# WiFi_Pi.net
KiCad netlist of a schematic drawn in EAGLE
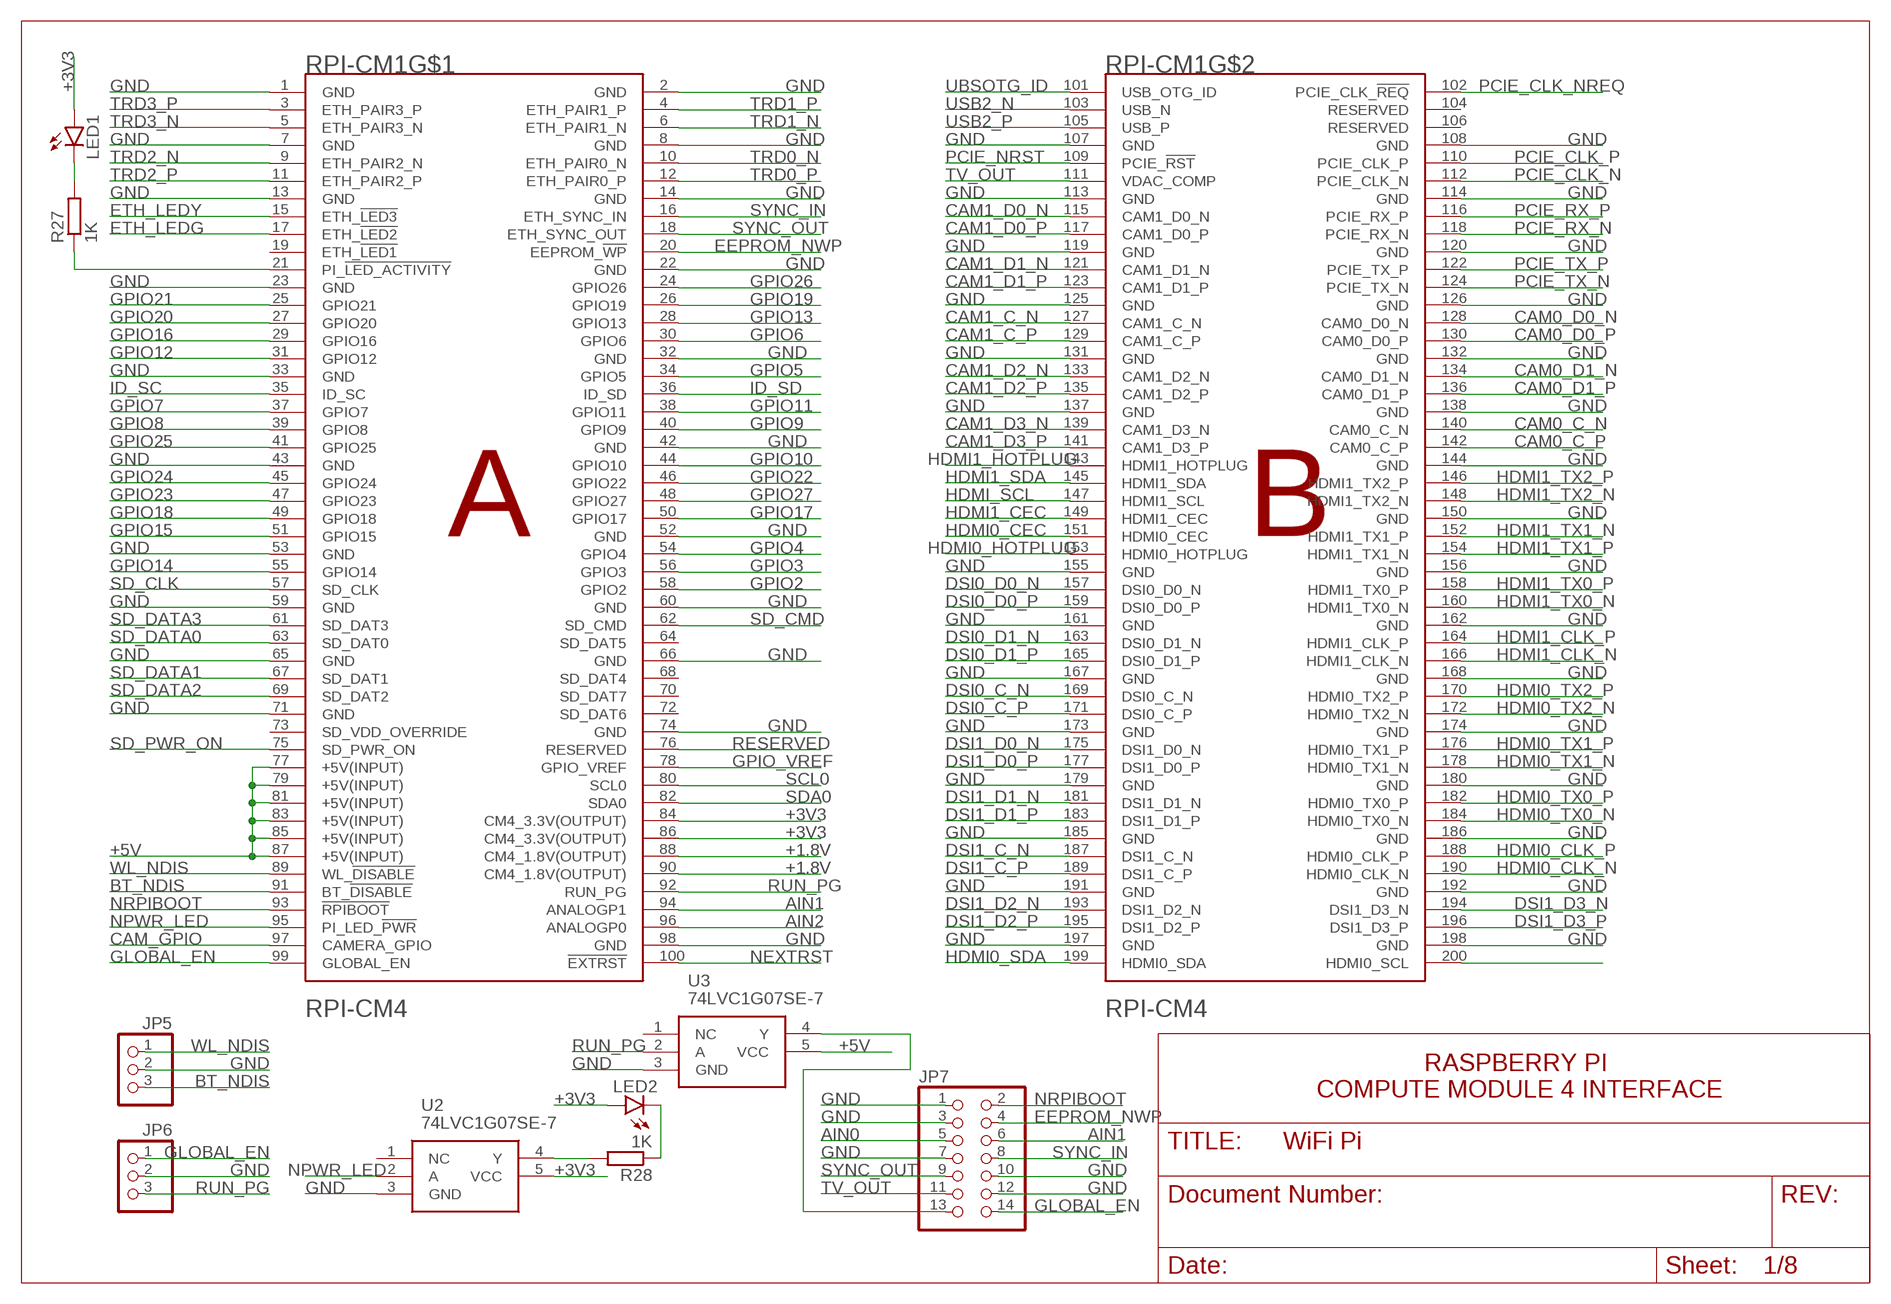
[diagram p0: schematic, sheet 1]
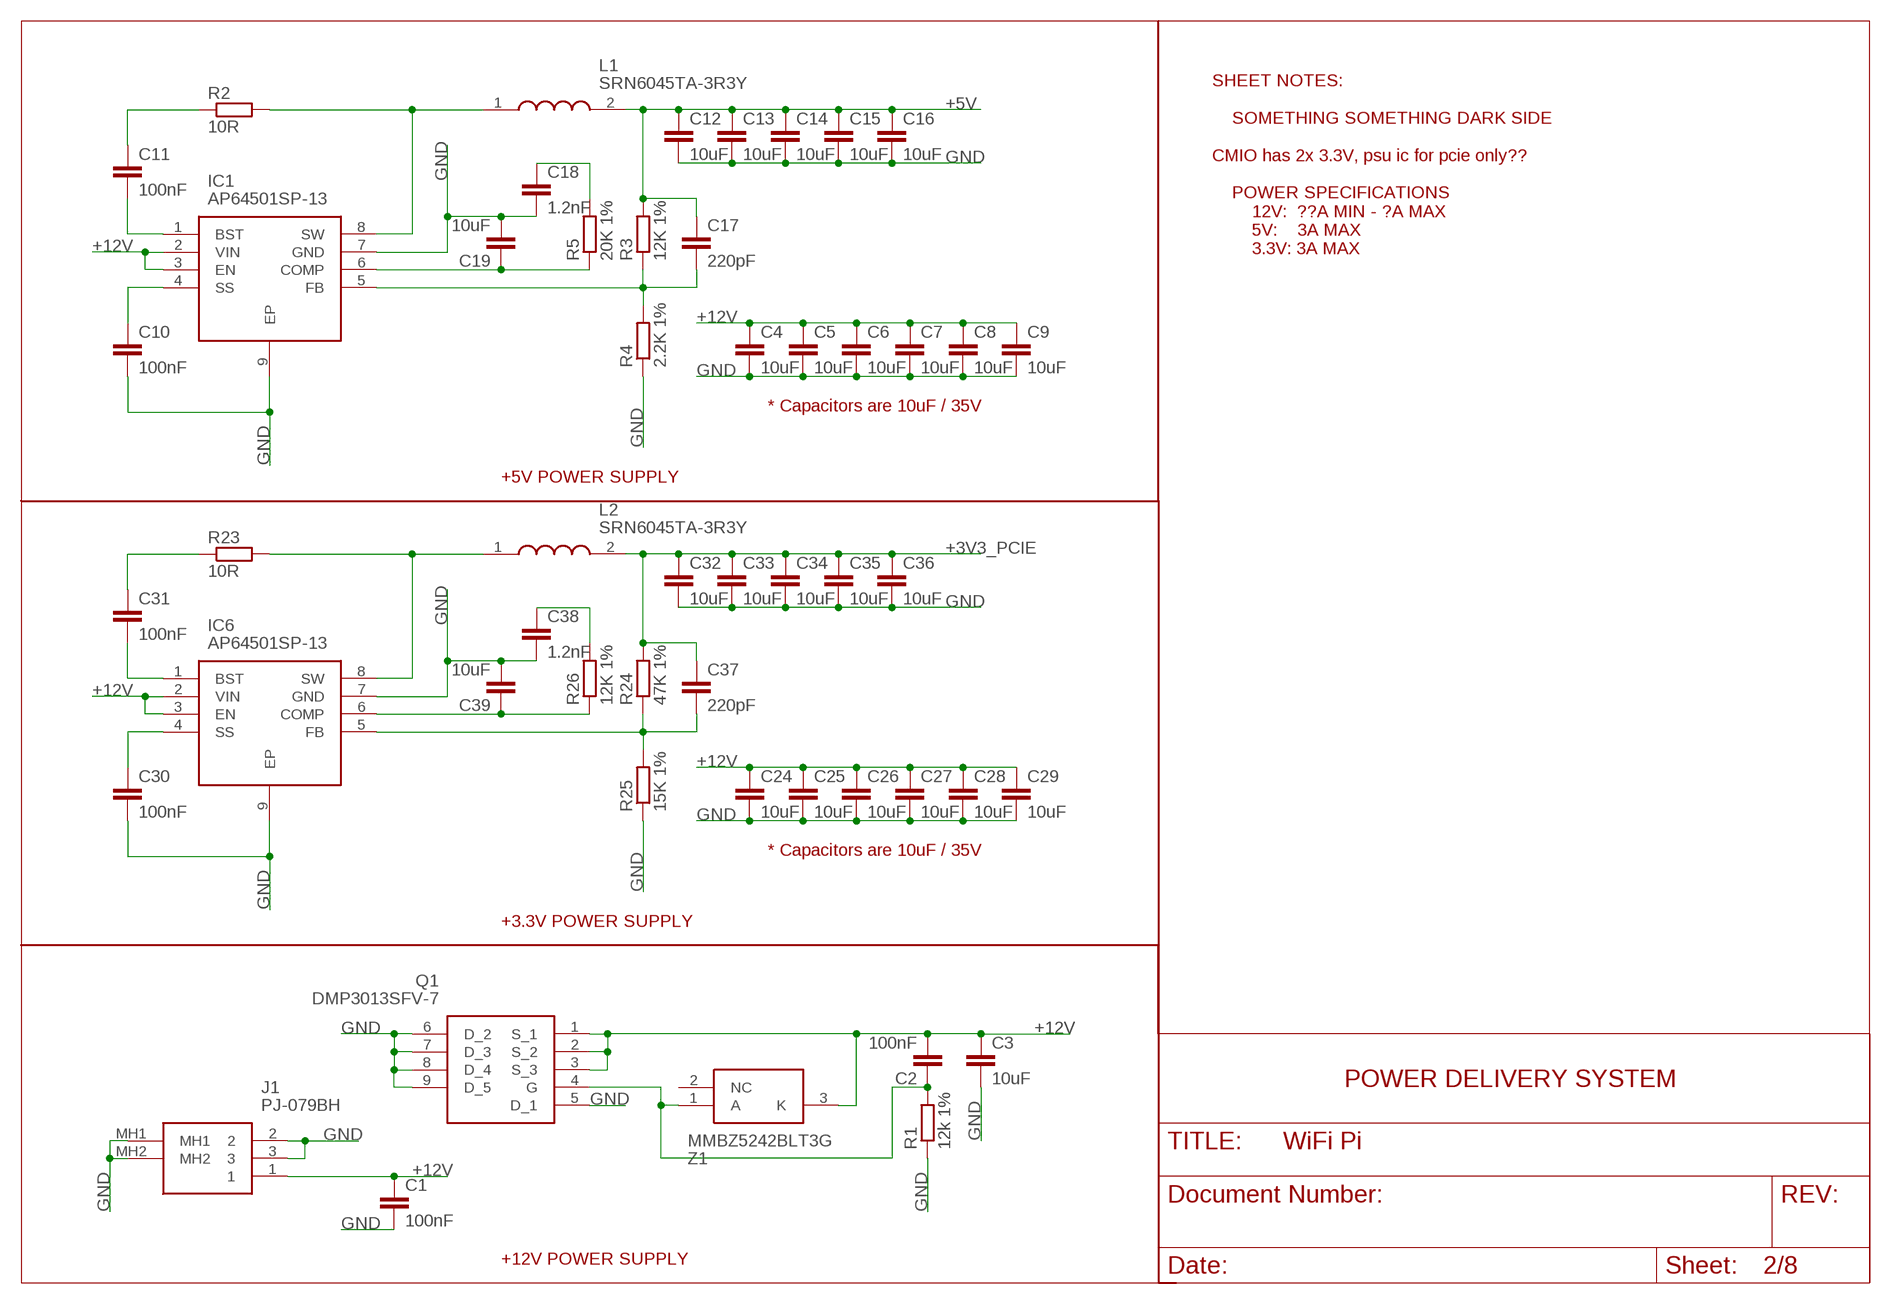
[diagram p1: schematic, sheet 2]
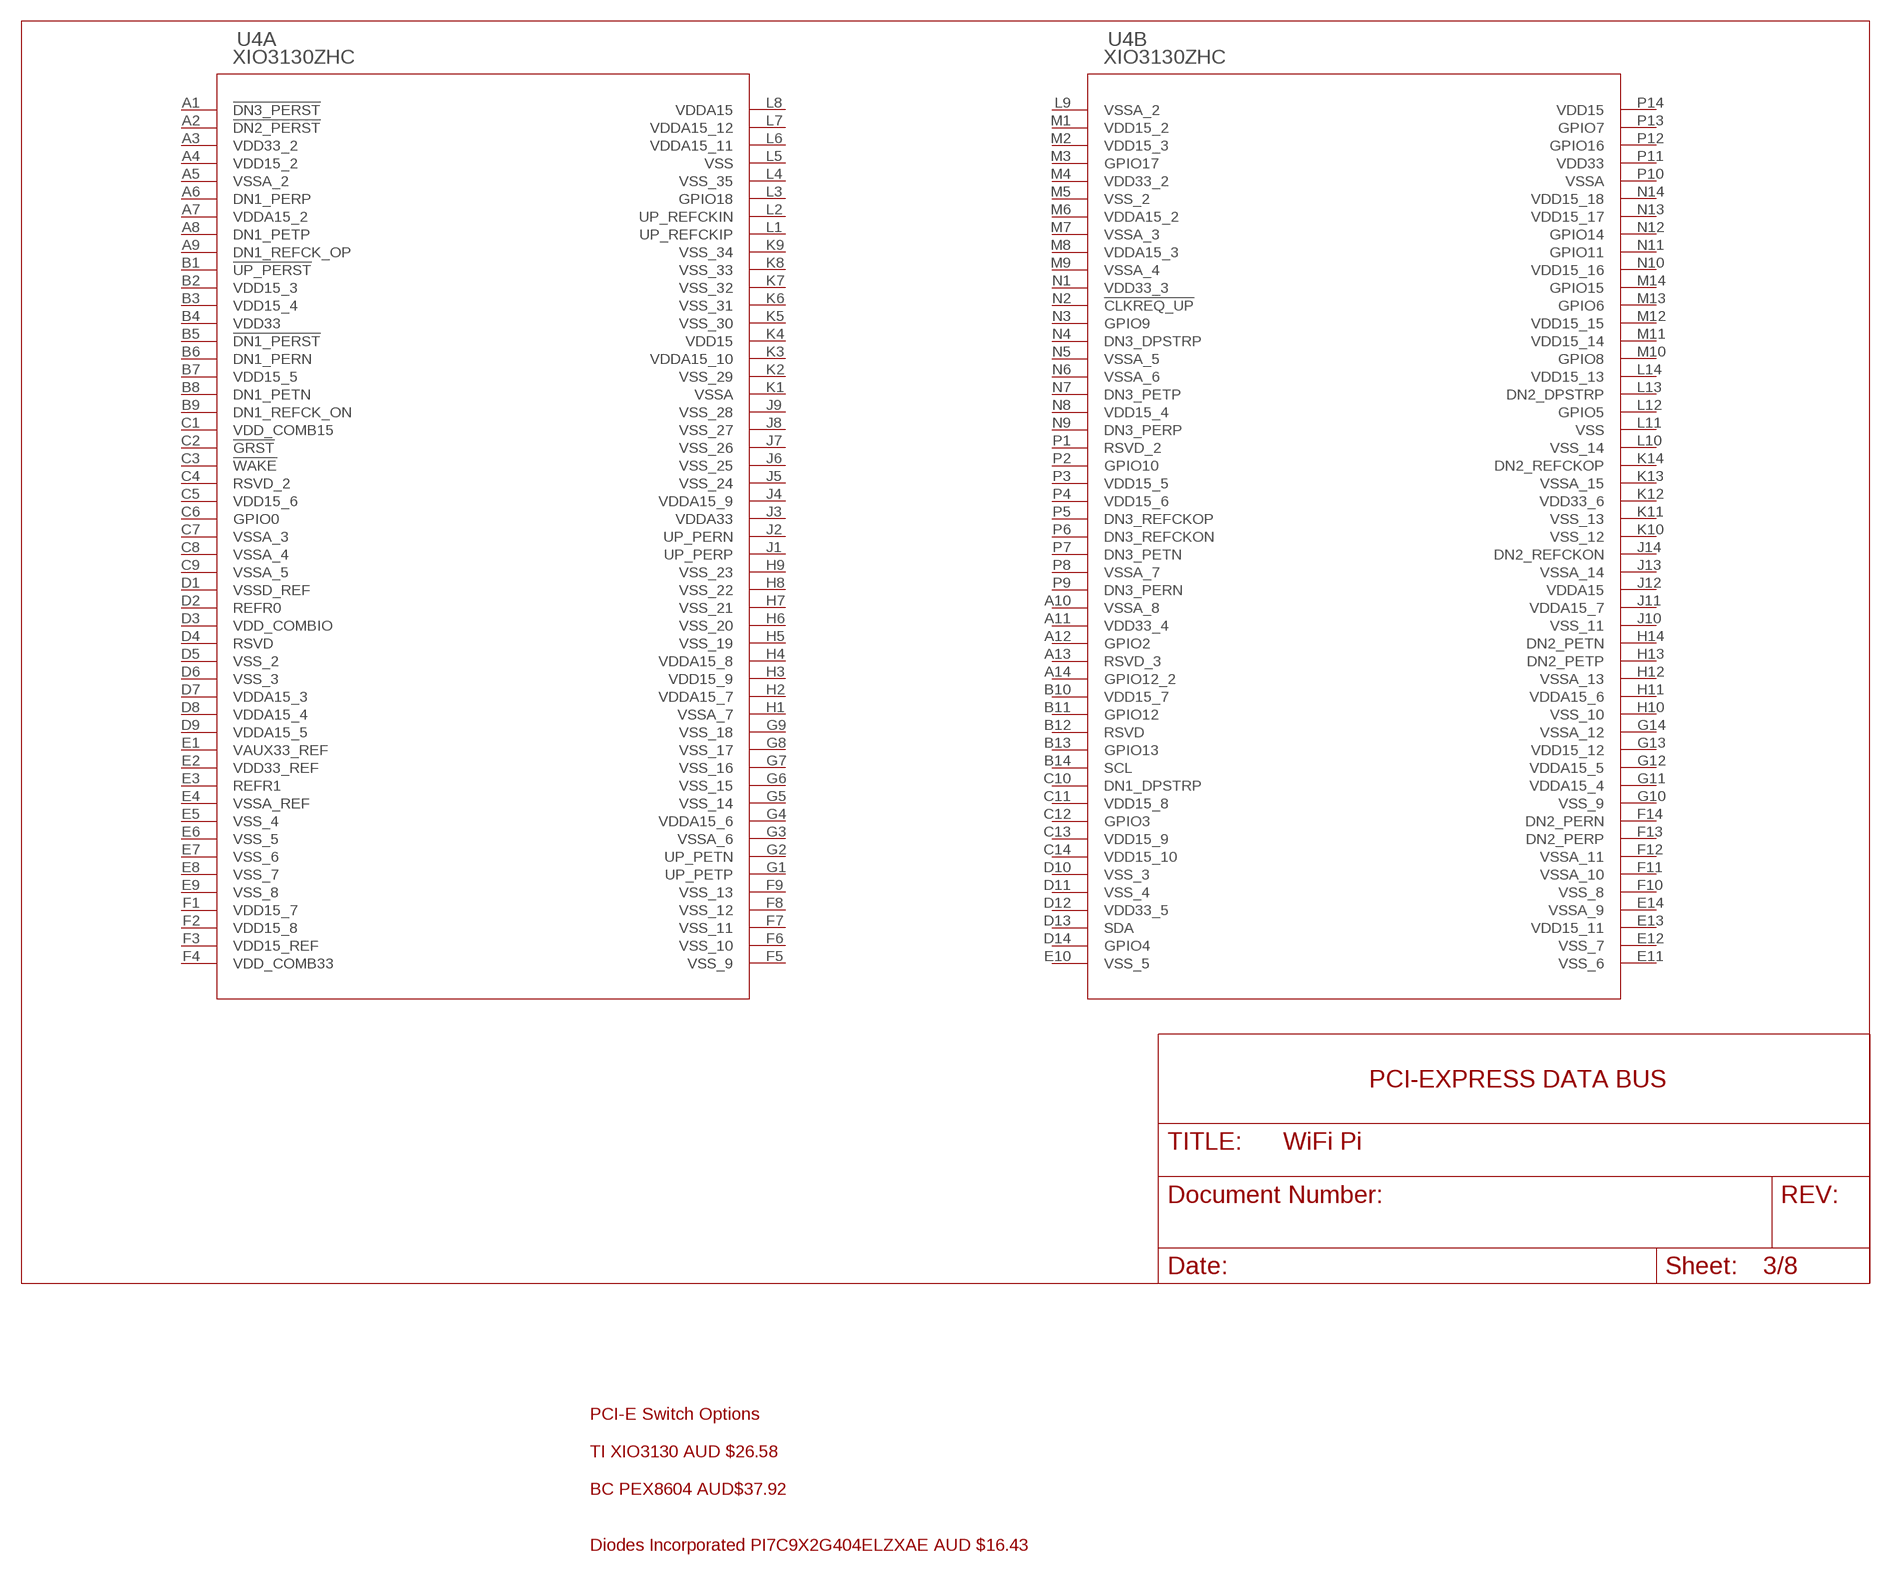
[diagram p2: schematic, sheet 3]
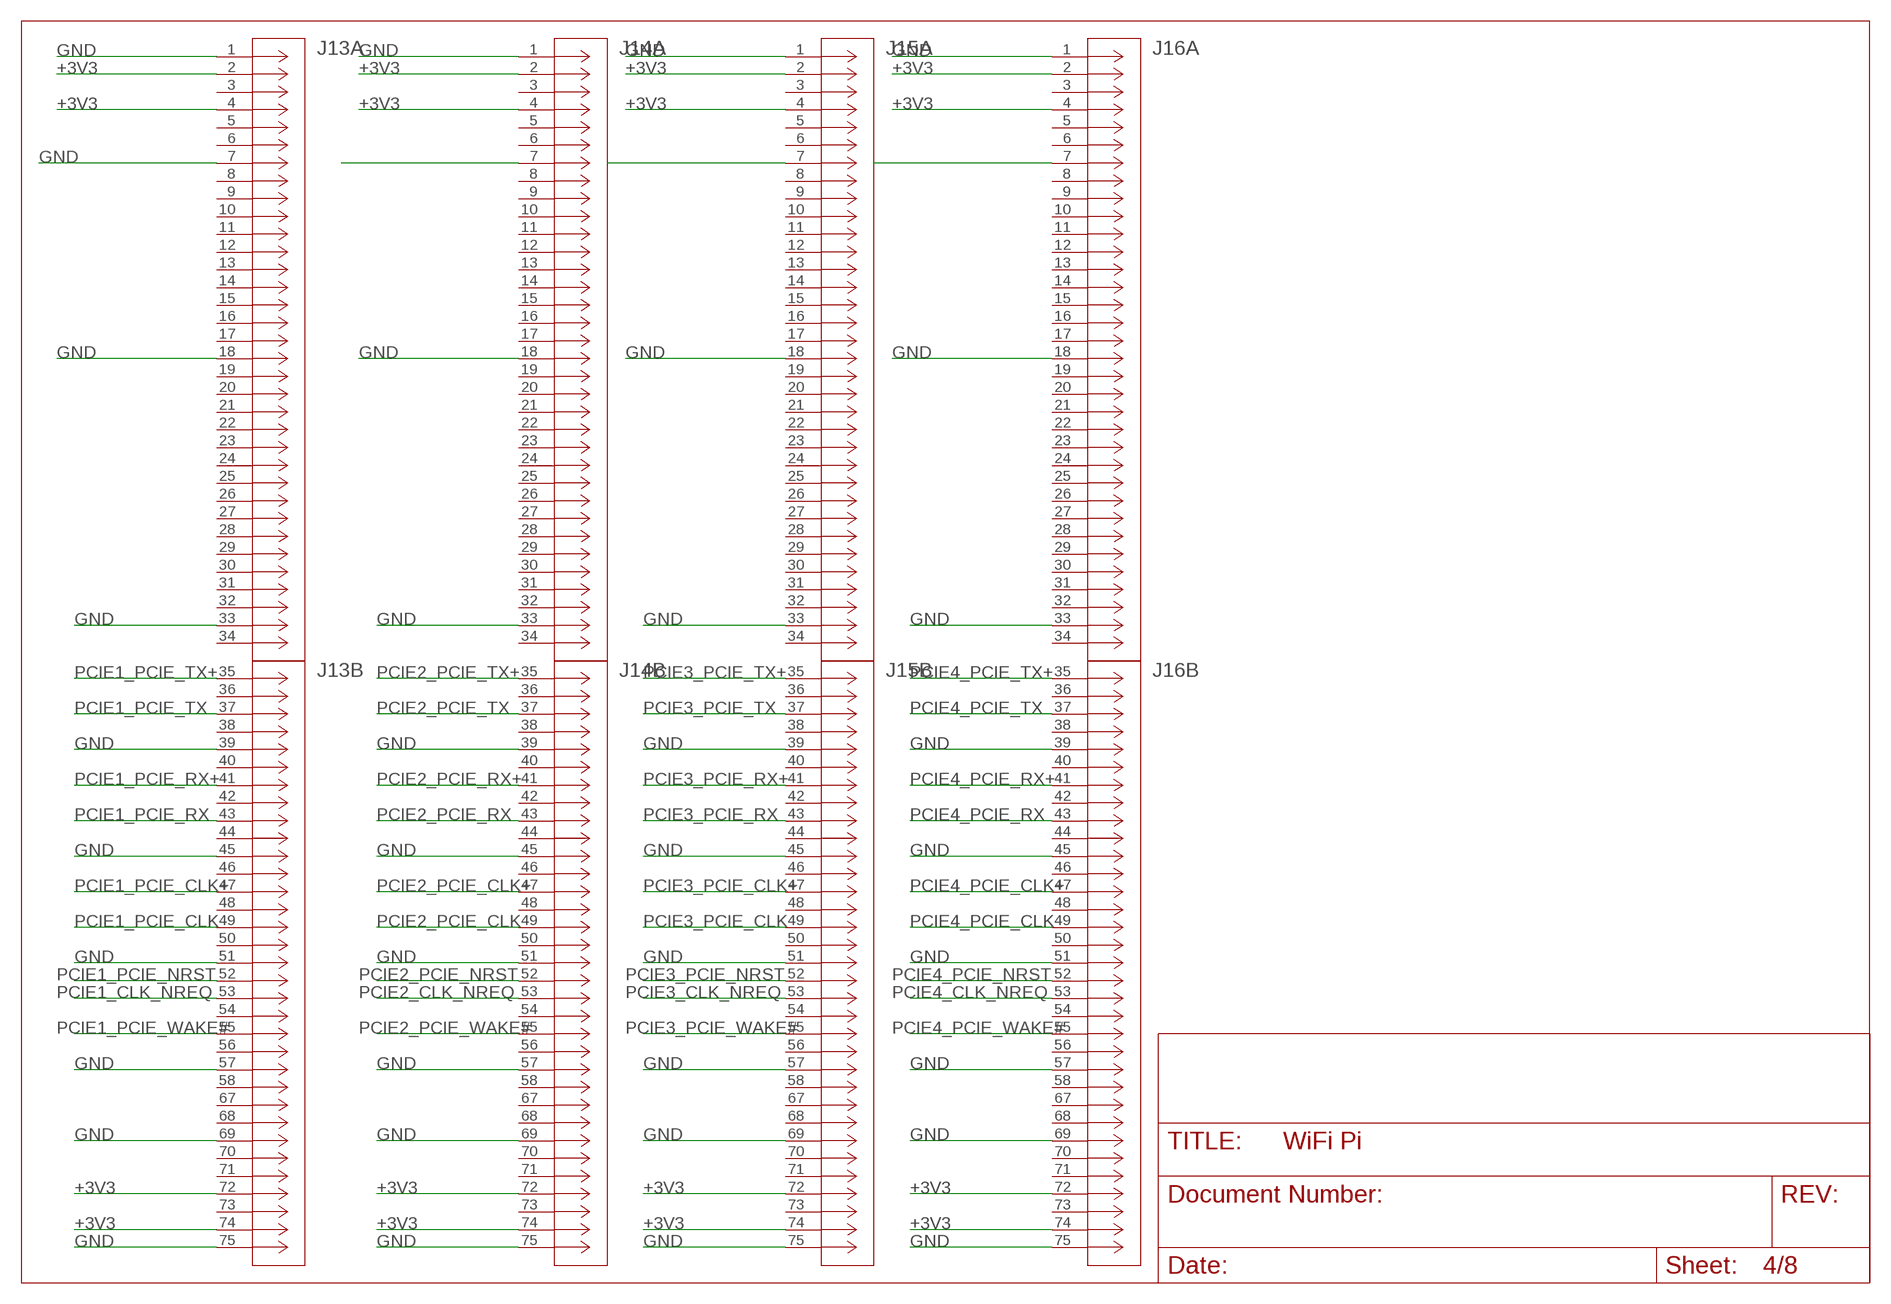
[diagram p3: schematic, sheet 4]
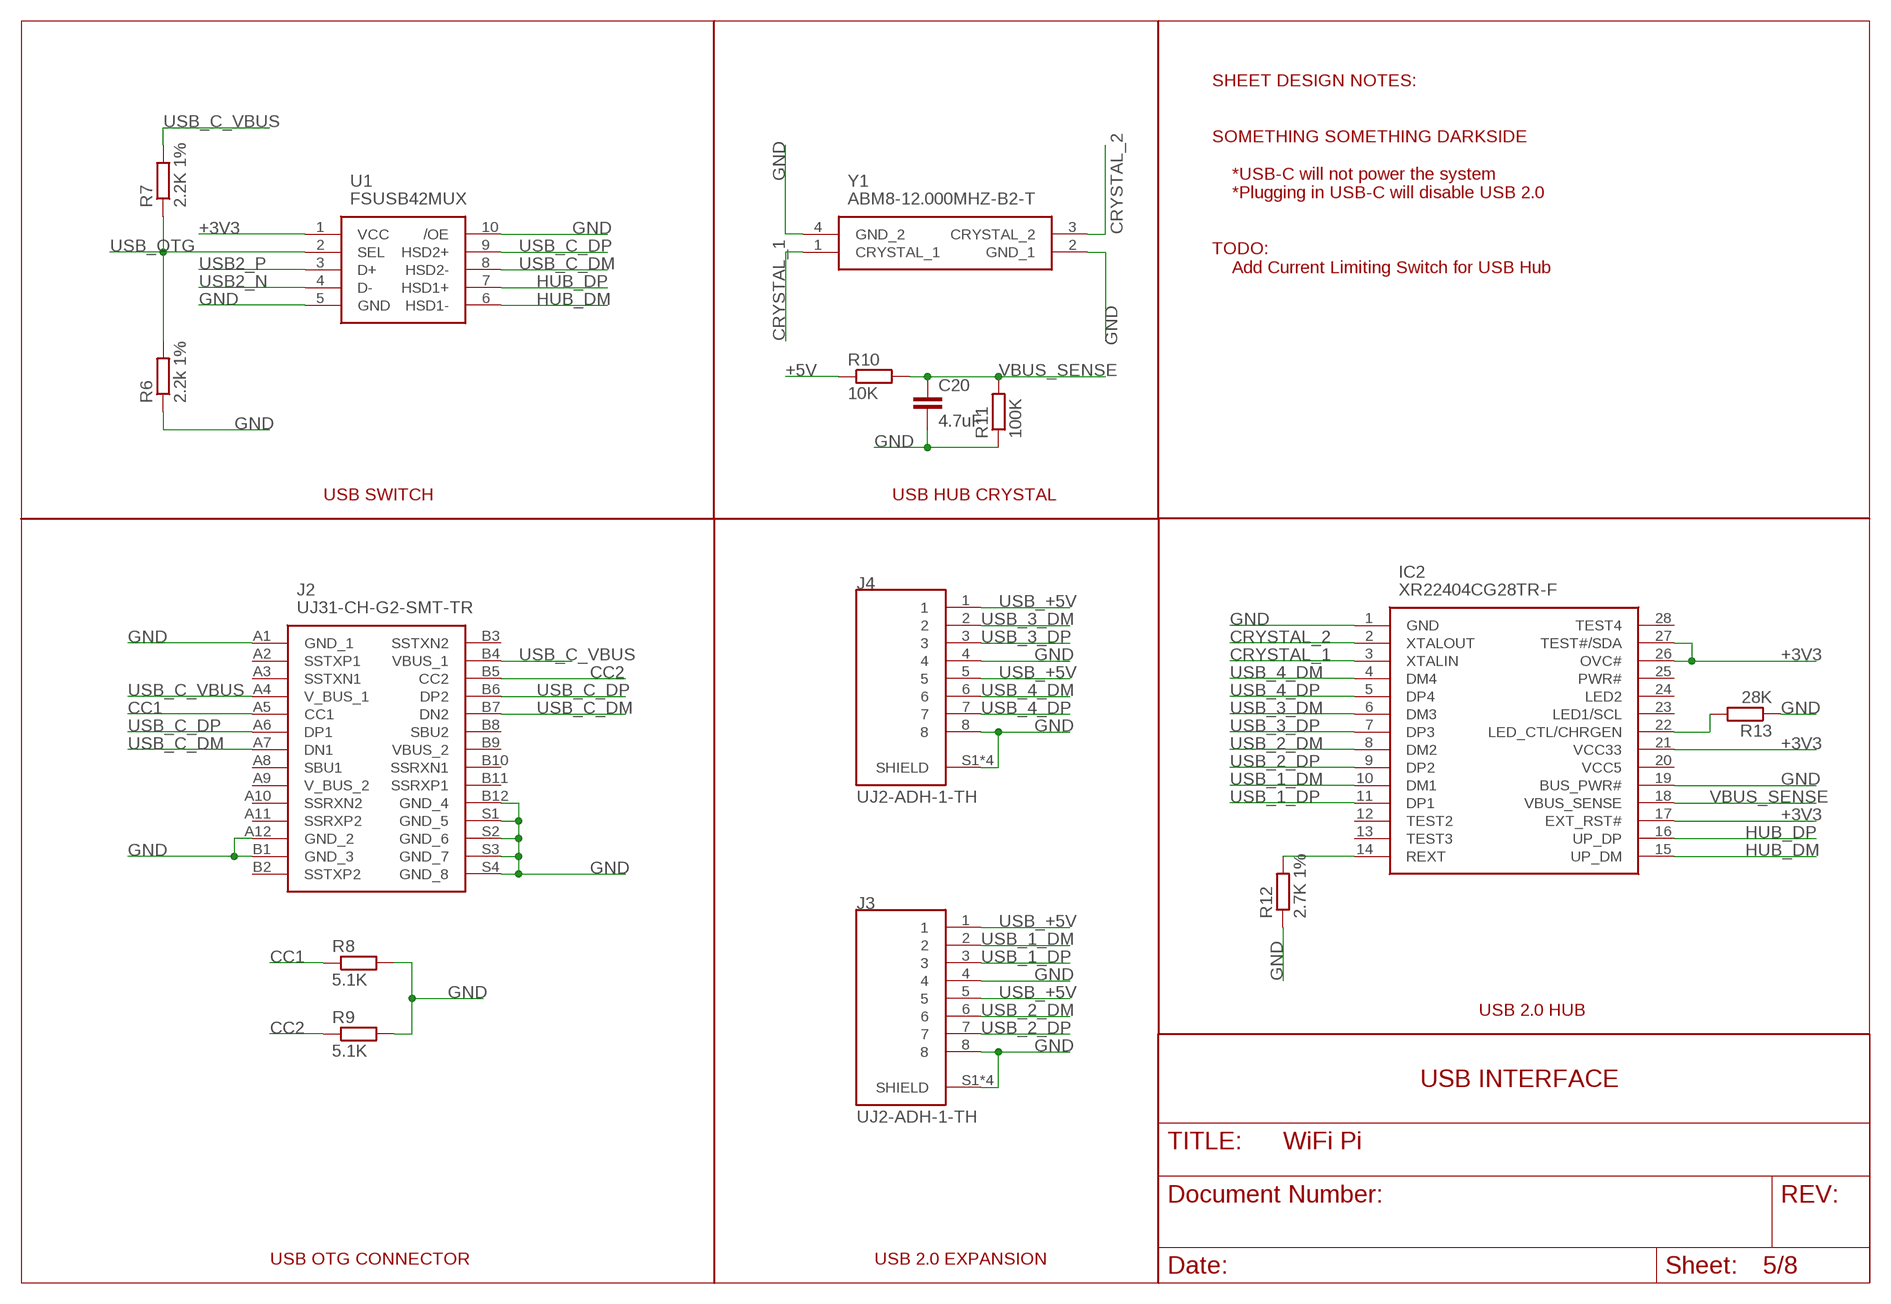
[diagram p4: schematic, sheet 5]
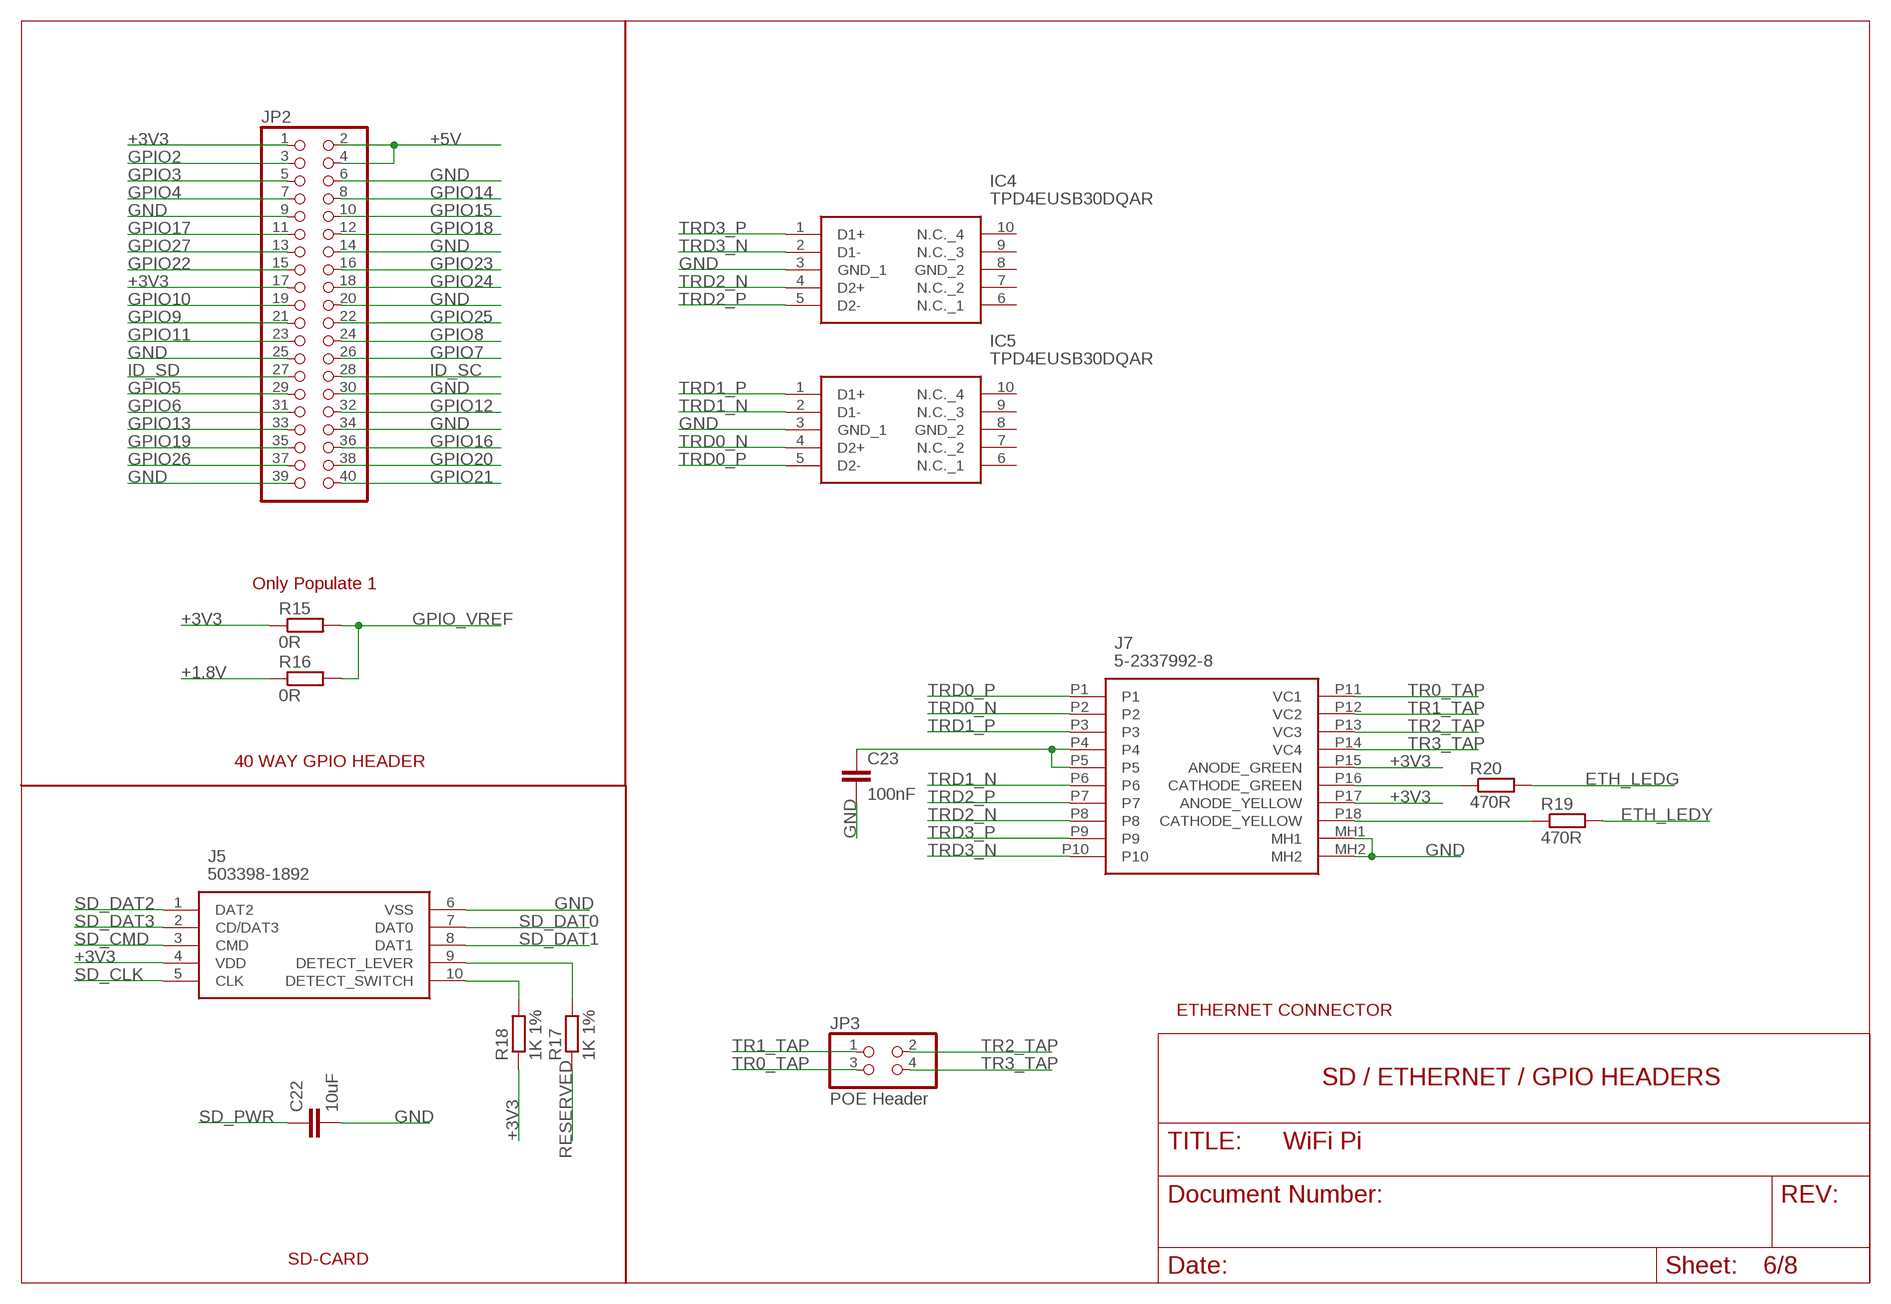
[diagram p5: schematic, sheet 6]
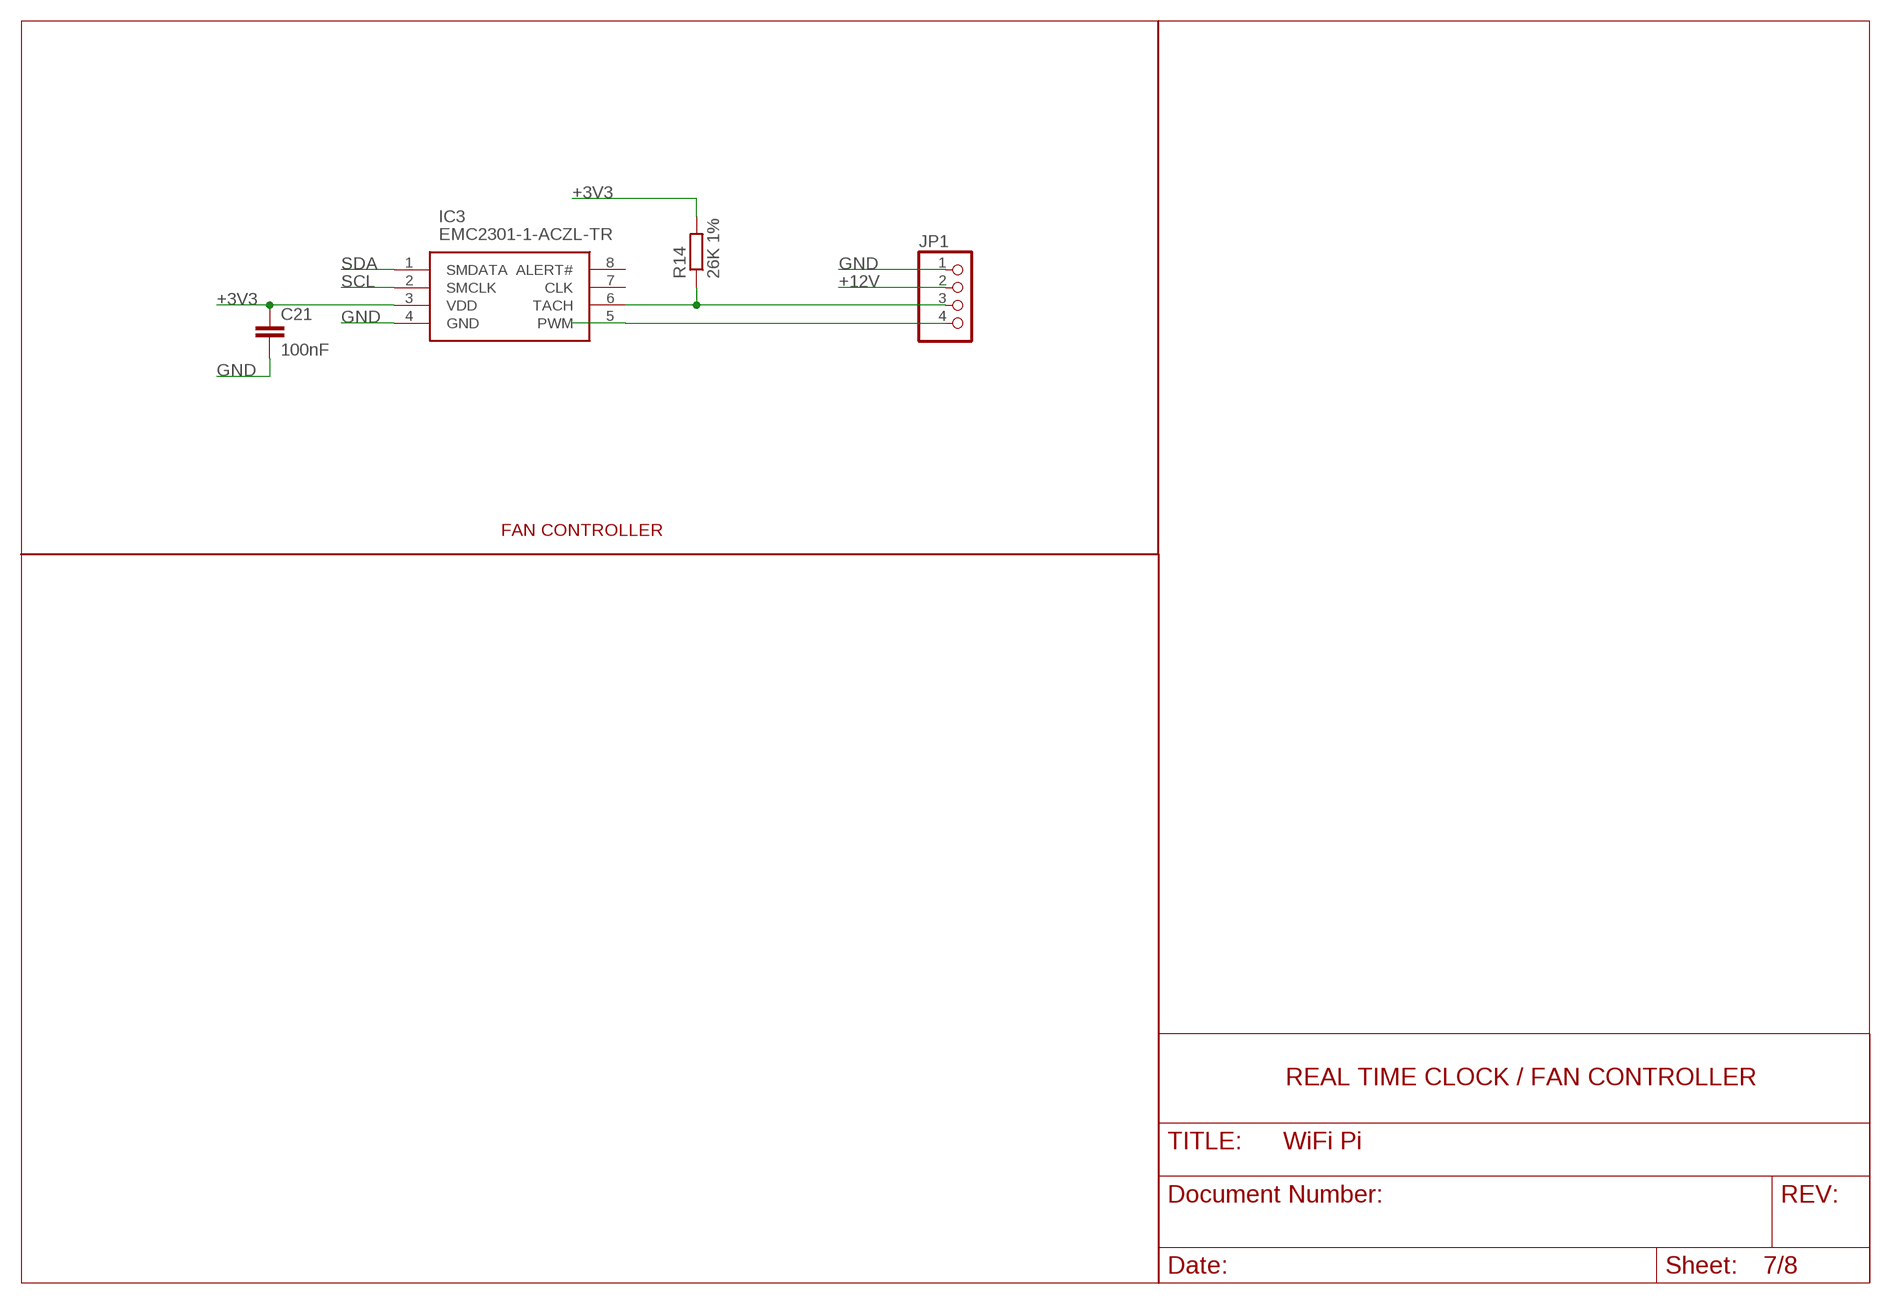
[diagram p6: schematic, sheet 7]
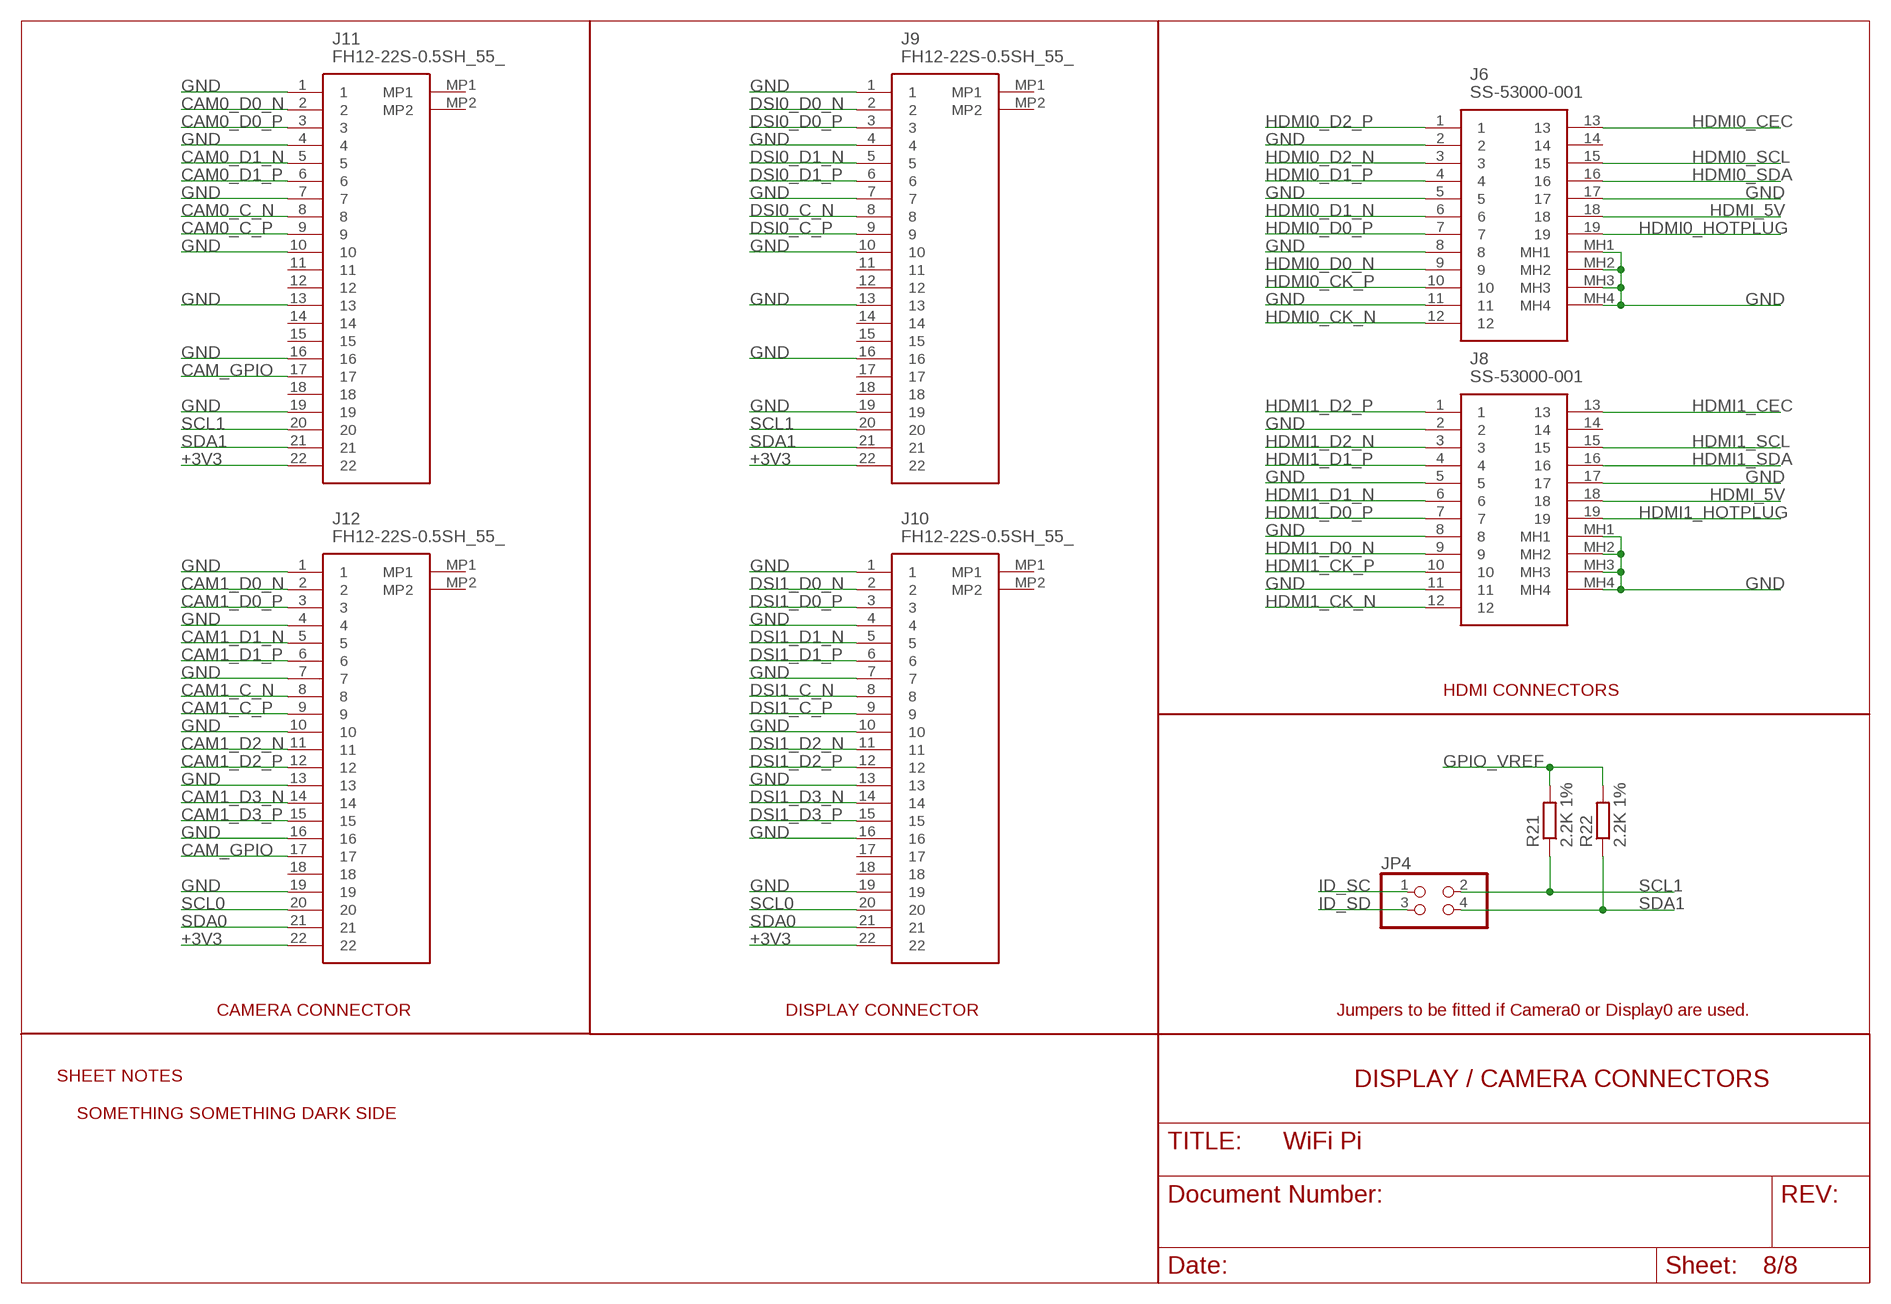
[diagram p7: schematic, sheet 8]

(export (version "E")
  (design (tool "Eeschema 10.0.6"))
  (components
    (comp (ref "JP5")
      (value "PINHD-1X3")
      (footprint "eagle-import:1X03")
      (libsource (lib "eagle-import") (part "PINHD-1X3"))
    )
    (comp (ref "JP6")
      (value "PINHD-1X3")
      (footprint "eagle-import:1X03")
      (libsource (lib "eagle-import") (part "PINHD-1X3"))
    )
    (comp (ref "JP7")
      (value "PINHD-2X7")
      (footprint "eagle-import:2X07")
      (libsource (lib "eagle-import") (part "PINHD-2X7"))
    )
    (comp (ref "LED1")
      (value "LEDCHIP-LED0805")
      (footprint "eagle-import:CHIP-LED0805")
      (libsource (lib "eagle-import") (part "LEDCHIP-LED0805"))
    )
    (comp (ref "LED2")
      (value "LEDCHIP-LED0805")
      (footprint "eagle-import:CHIP-LED0805")
      (libsource (lib "eagle-import") (part "LEDCHIP-LED0805"))
    )
    (comp (ref "R27")
      (value "1K")
      (footprint "eagle-import:M0805")
      (libsource (lib "eagle-import") (part "R-EU_M0805"))
    )
    (comp (ref "R28")
      (value "1K")
      (footprint "eagle-import:M0805")
      (libsource (lib "eagle-import") (part "R-EU_M0805"))
    )
    (comp (ref "RPI-CM1")
      (value "RPI-CM4")
      (footprint "eagle-import:RPI-CM4")
      (libsource (lib "eagle-import") (part "RPI-CM4"))
    )
    (comp (ref "U2")
      (value "74LVC1G07SE-7")
      (footprint "eagle-import:SOT65P210X110-5N")
      (fields (field (name "MOUSER_PART_NUMBER") "621-74LVC1G07SE-7"))
      (libsource (lib "eagle-import") (part "74LVC1G07SE-7"))
    )
    (comp (ref "U3")
      (value "74LVC1G07SE-7")
      (footprint "eagle-import:SOT65P210X110-5N")
      (fields (field (name "MOUSER_PART_NUMBER") "621-74LVC1G07SE-7"))
      (libsource (lib "eagle-import") (part "74LVC1G07SE-7"))
    )
    (comp (ref "C22")
      (value "10uF")
      (footprint "eagle-import:C0805K")
      (libsource (lib "eagle-import") (part "C-EUC0805K"))
    )
    (comp (ref "C23")
      (value "100nF")
      (footprint "eagle-import:C0805K")
      (libsource (lib "eagle-import") (part "C-EUC0805K"))
    )
    (comp (ref "IC4")
      (value "TPD4EUSB30DQAR")
      (footprint "eagle-import:DQA(R-PUSON-N10)")
      (fields (field (name "MOUSER_PART_NUMBER") "595-TPD4EUSB30DQAR"))
      (libsource (lib "eagle-import") (part "TPD4EUSB30DQAR"))
    )
    (comp (ref "IC5")
      (value "TPD4EUSB30DQAR")
      (footprint "eagle-import:DQA(R-PUSON-N10)")
      (fields (field (name "MOUSER_PART_NUMBER") "595-TPD4EUSB30DQAR"))
      (libsource (lib "eagle-import") (part "TPD4EUSB30DQAR"))
    )
    (comp (ref "J5")
      (value "503398-1892")
      (footprint "eagle-import:503398-1892")
      (fields (field (name "MOUSER_PART_NUMBER") "538-503398-1892"))
      (libsource (lib "eagle-import") (part "503398-1892"))
    )
    (comp (ref "J7")
      (value "5-2337992-8")
      (footprint "eagle-import:523379928")
      (fields (field (name "MOUSER_PART_NUMBER") "571-5-2337992-8"))
      (libsource (lib "eagle-import") (part "5-2337992-8"))
    )
    (comp (ref "JP2")
      (value "PINHD-2X20")
      (footprint "eagle-import:2X20")
      (libsource (lib "eagle-import") (part "PINHD-2X20"))
    )
    (comp (ref "JP3")
      (value "POE Header")
      (footprint "eagle-import:2X02")
      (libsource (lib "eagle-import") (part "PINHD-2X2"))
    )
    (comp (ref "R15")
      (value "0R")
      (footprint "eagle-import:M0805")
      (libsource (lib "eagle-import") (part "R-EU_M0805"))
    )
    (comp (ref "R16")
      (value "0R")
      (footprint "eagle-import:M0805")
      (libsource (lib "eagle-import") (part "R-EU_M0805"))
    )
    (comp (ref "R17")
      (value "1K 1%")
      (footprint "eagle-import:M0805")
      (libsource (lib "eagle-import") (part "R-EU_M0805"))
    )
    (comp (ref "R18")
      (value "1K 1%")
      (footprint "eagle-import:M0805")
      (libsource (lib "eagle-import") (part "R-EU_M0805"))
    )
    (comp (ref "R19")
      (value "470R")
      (footprint "eagle-import:M0805")
      (libsource (lib "eagle-import") (part "R-EU_M0805"))
    )
    (comp (ref "R20")
      (value "470R")
      (footprint "eagle-import:M0805")
      (libsource (lib "eagle-import") (part "R-EU_M0805"))
    )
    (comp (ref "C20")
      (value "4.7uF")
      (footprint "eagle-import:C0805K")
      (libsource (lib "eagle-import") (part "C-EUC0805K"))
    )
    (comp (ref "IC2")
      (value "XR22404CG28TR-F")
      (footprint "eagle-import:SOP64P600X173-28N")
      (fields (field (name "MOUSER_PART_NUMBER") "701-XR22404CG28TR-F"))
      (libsource (lib "eagle-import") (part "XR22404CG28TR-F"))
    )
    (comp (ref "J2")
      (value "UJ31-CH-G2-SMT-TR")
      (footprint "eagle-import:UJ31CHG2SMTTR")
      (fields (field (name "MOUSER_PART_NUMBER") "490-UJ31-CH-G2SMT-TR"))
      (libsource (lib "eagle-import") (part "UJ31-CH-G2-SMT-TR"))
    )
    (comp (ref "J3")
      (value "UJ2-ADH-1-TH")
      (footprint "eagle-import:CUI_UJ2-ADH-1-TH")
      (fields (field (name "MANUFACTURER") "CUI Devices"))
      (libsource (lib "eagle-import") (part "UJ2-ADH-1-TH"))
    )
    (comp (ref "J4")
      (value "UJ2-ADH-1-TH")
      (footprint "eagle-import:CUI_UJ2-ADH-1-TH")
      (fields (field (name "MANUFACTURER") "CUI Devices"))
      (libsource (lib "eagle-import") (part "UJ2-ADH-1-TH"))
    )
    (comp (ref "R6")
      (value "2.2k 1%")
      (footprint "eagle-import:M0805")
      (libsource (lib "eagle-import") (part "R-EU_M0805"))
    )
    (comp (ref "R7")
      (value "2.2K 1%")
      (footprint "eagle-import:M0805")
      (libsource (lib "eagle-import") (part "R-EU_M0805"))
    )
    (comp (ref "R8")
      (value "5.1K")
      (footprint "eagle-import:M0805")
      (libsource (lib "eagle-import") (part "R-EU_M0805"))
    )
    (comp (ref "R9")
      (value "5.1K")
      (footprint "eagle-import:M0805")
      (libsource (lib "eagle-import") (part "R-EU_M0805"))
    )
    (comp (ref "R10")
      (value "10K")
      (footprint "eagle-import:M0805")
      (libsource (lib "eagle-import") (part "R-EU_M0805"))
    )
    (comp (ref "R11")
      (value "100K")
      (footprint "eagle-import:M0805")
      (libsource (lib "eagle-import") (part "R-EU_M0805"))
    )
    (comp (ref "R12")
      (value "2.7K 1%")
      (footprint "eagle-import:M0805")
      (libsource (lib "eagle-import") (part "R-EU_M0805"))
    )
    (comp (ref "R13")
      (value "28K")
      (footprint "eagle-import:M0805")
      (libsource (lib "eagle-import") (part "R-EU_M0805"))
    )
    (comp (ref "U1")
      (value "FSUSB42MUX")
      (footprint "eagle-import:SOP50P490X110-10N")
      (fields (field (name "MOUSER_PART_NUMBER") "512-FSUSB42MUX"))
      (libsource (lib "eagle-import") (part "FSUSB42MUX"))
    )
    (comp (ref "Y1")
      (value "ABM8-12.000MHZ-B2-T")
      (footprint "eagle-import:ABM812000MHZB2T")
      (fields
        (field (name "MANUFACTURER_PART_NUMBER") "ABM8-12.000MHz-B2-T")
        (field (name "MOUSER_PART_NUMBER") "815-ABM8-12-B2-T")
      )
      (libsource (lib "eagle-import") (part "ABM8-12.000MHZ-B2-T"))
    )
    (comp (ref "U4")
      (value "XIO3130ZHC")
      (footprint "eagle-import:ZHC196")
      (fields
        (field (name "GENERIC_PART_NUMBER") "XIO3130")
        (field (name "MANUFACTURER") "Texas Instruments")
      )
      (libsource (lib "eagle-import") (part "XIO3130ZHC"))
    )
    (comp (ref "J6")
      (value "SS-53000-001")
      (footprint "eagle-import:SS53000001")
      (fields (field (name "MOUSER_PART_NUMBER") "530-SS-53000-001"))
      (libsource (lib "eagle-import") (part "SS-53000-001"))
    )
    (comp (ref "J8")
      (value "SS-53000-001")
      (footprint "eagle-import:SS53000001")
      (fields (field (name "MOUSER_PART_NUMBER") "530-SS-53000-001"))
      (libsource (lib "eagle-import") (part "SS-53000-001"))
    )
    (comp (ref "J9")
      (value "FH12-22S-0.5SH_55_")
      (footprint "eagle-import:FH1222S05SH55")
      (fields
        (field (name "MANUFACTURER_PART_NUMBER") "FH12-22S-0.5SH(55)")
        (field (name "MOUSER_PART_NUMBER") "798-FH12-22S-0.5SH55")
      )
      (libsource (lib "eagle-import") (part "FH12-22S-0.5SH_55_"))
    )
    (comp (ref "J10")
      (value "FH12-22S-0.5SH_55_")
      (footprint "eagle-import:FH1222S05SH55")
      (fields
        (field (name "MANUFACTURER_PART_NUMBER") "FH12-22S-0.5SH(55)")
        (field (name "MOUSER_PART_NUMBER") "798-FH12-22S-0.5SH55")
      )
      (libsource (lib "eagle-import") (part "FH12-22S-0.5SH_55_"))
    )
    (comp (ref "J11")
      (value "FH12-22S-0.5SH_55_")
      (footprint "eagle-import:FH1222S05SH55")
      (fields
        (field (name "MANUFACTURER_PART_NUMBER") "FH12-22S-0.5SH(55)")
        (field (name "MOUSER_PART_NUMBER") "798-FH12-22S-0.5SH55")
      )
      (libsource (lib "eagle-import") (part "FH12-22S-0.5SH_55_"))
    )
    (comp (ref "J12")
      (value "FH12-22S-0.5SH_55_")
      (footprint "eagle-import:FH1222S05SH55")
      (fields
        (field (name "MANUFACTURER_PART_NUMBER") "FH12-22S-0.5SH(55)")
        (field (name "MOUSER_PART_NUMBER") "798-FH12-22S-0.5SH55")
      )
      (libsource (lib "eagle-import") (part "FH12-22S-0.5SH_55_"))
    )
    (comp (ref "JP4")
      (value "PINHD-2X2")
      (footprint "eagle-import:2X02")
      (libsource (lib "eagle-import") (part "PINHD-2X2"))
    )
    (comp (ref "R21")
      (value "2.2K 1%")
      (footprint "eagle-import:M0805")
      (libsource (lib "eagle-import") (part "R-EU_M0805"))
    )
    (comp (ref "R22")
      (value "2.2K 1%")
      (footprint "eagle-import:M0805")
      (libsource (lib "eagle-import") (part "R-EU_M0805"))
    )
    (comp (ref "C1")
      (value "100nF")
      (footprint "eagle-import:C0805K")
      (libsource (lib "eagle-import") (part "C-EUC0805K"))
    )
    (comp (ref "C2")
      (value "100nF")
      (footprint "eagle-import:C0805K")
      (libsource (lib "eagle-import") (part "C-EUC0805K"))
    )
    (comp (ref "C3")
      (value "10uF")
      (footprint "eagle-import:C0805K")
      (libsource (lib "eagle-import") (part "C-EUC0805K"))
    )
    (comp (ref "C4")
      (value "10uF")
      (footprint "eagle-import:C0805K")
      (libsource (lib "eagle-import") (part "C-EUC0805K"))
    )
    (comp (ref "C5")
      (value "10uF")
      (footprint "eagle-import:C0805K")
      (libsource (lib "eagle-import") (part "C-EUC0805K"))
    )
    (comp (ref "C6")
      (value "10uF")
      (footprint "eagle-import:C0805K")
      (libsource (lib "eagle-import") (part "C-EUC0805K"))
    )
    (comp (ref "C7")
      (value "10uF")
      (footprint "eagle-import:C0805K")
      (libsource (lib "eagle-import") (part "C-EUC0805K"))
    )
    (comp (ref "C8")
      (value "10uF")
      (footprint "eagle-import:C0805K")
      (libsource (lib "eagle-import") (part "C-EUC0805K"))
    )
    (comp (ref "C9")
      (value "10uF")
      (footprint "eagle-import:C0805K")
      (libsource (lib "eagle-import") (part "C-EUC0805K"))
    )
    (comp (ref "C10")
      (value "100nF")
      (footprint "eagle-import:C0805K")
      (libsource (lib "eagle-import") (part "C-EUC0805K"))
    )
    (comp (ref "C11")
      (value "100nF")
      (footprint "eagle-import:C0805K")
      (libsource (lib "eagle-import") (part "C-EUC0805K"))
    )
    (comp (ref "C12")
      (value "10uF")
      (footprint "eagle-import:C0805K")
      (libsource (lib "eagle-import") (part "C-EUC0805K"))
    )
    (comp (ref "C13")
      (value "10uF")
      (footprint "eagle-import:C0805K")
      (libsource (lib "eagle-import") (part "C-EUC0805K"))
    )
    (comp (ref "C14")
      (value "10uF")
      (footprint "eagle-import:C0805K")
      (libsource (lib "eagle-import") (part "C-EUC0805K"))
    )
    (comp (ref "C15")
      (value "10uF")
      (footprint "eagle-import:C0805K")
      (libsource (lib "eagle-import") (part "C-EUC0805K"))
    )
    (comp (ref "C16")
      (value "10uF")
      (footprint "eagle-import:C0805K")
      (libsource (lib "eagle-import") (part "C-EUC0805K"))
    )
    (comp (ref "C17")
      (value "220pF")
      (footprint "eagle-import:C0805K")
      (libsource (lib "eagle-import") (part "C-EUC0805K"))
    )
    (comp (ref "C18")
      (value "1.2nF")
      (footprint "eagle-import:C0805K")
      (libsource (lib "eagle-import") (part "C-EUC0805K"))
    )
    (comp (ref "C19")
      (value "10uF")
      (footprint "eagle-import:C0805K")
      (libsource (lib "eagle-import") (part "C-EUC0805K"))
    )
    (comp (ref "C24")
      (value "10uF")
      (footprint "eagle-import:C0805K")
      (libsource (lib "eagle-import") (part "C-EUC0805K"))
    )
    (comp (ref "C25")
      (value "10uF")
      (footprint "eagle-import:C0805K")
      (libsource (lib "eagle-import") (part "C-EUC0805K"))
    )
    (comp (ref "C26")
      (value "10uF")
      (footprint "eagle-import:C0805K")
      (libsource (lib "eagle-import") (part "C-EUC0805K"))
    )
    (comp (ref "C27")
      (value "10uF")
      (footprint "eagle-import:C0805K")
      (libsource (lib "eagle-import") (part "C-EUC0805K"))
    )
    (comp (ref "C28")
      (value "10uF")
      (footprint "eagle-import:C0805K")
      (libsource (lib "eagle-import") (part "C-EUC0805K"))
    )
    (comp (ref "C29")
      (value "10uF")
      (footprint "eagle-import:C0805K")
      (libsource (lib "eagle-import") (part "C-EUC0805K"))
    )
    (comp (ref "C30")
      (value "100nF")
      (footprint "eagle-import:C0805K")
      (libsource (lib "eagle-import") (part "C-EUC0805K"))
    )
    (comp (ref "C31")
      (value "100nF")
      (footprint "eagle-import:C0805K")
      (libsource (lib "eagle-import") (part "C-EUC0805K"))
    )
    (comp (ref "C32")
      (value "10uF")
      (footprint "eagle-import:C0805K")
      (libsource (lib "eagle-import") (part "C-EUC0805K"))
    )
    (comp (ref "C33")
      (value "10uF")
      (footprint "eagle-import:C0805K")
      (libsource (lib "eagle-import") (part "C-EUC0805K"))
    )
    (comp (ref "C34")
      (value "10uF")
      (footprint "eagle-import:C0805K")
      (libsource (lib "eagle-import") (part "C-EUC0805K"))
    )
    (comp (ref "C35")
      (value "10uF")
      (footprint "eagle-import:C0805K")
      (libsource (lib "eagle-import") (part "C-EUC0805K"))
    )
    (comp (ref "C36")
      (value "10uF")
      (footprint "eagle-import:C0805K")
      (libsource (lib "eagle-import") (part "C-EUC0805K"))
    )
    (comp (ref "C37")
      (value "220pF")
      (footprint "eagle-import:C0805K")
      (libsource (lib "eagle-import") (part "C-EUC0805K"))
    )
    (comp (ref "C38")
      (value "1.2nF")
      (footprint "eagle-import:C0805K")
      (libsource (lib "eagle-import") (part "C-EUC0805K"))
    )
    (comp (ref "C39")
      (value "10uF")
      (footprint "eagle-import:C0805K")
      (libsource (lib "eagle-import") (part "C-EUC0805K"))
    )
    (comp (ref "IC1")
      (value "AP64501SP-13")
      (footprint "eagle-import:SOIC127P600X163-9N")
      (fields (field (name "MOUSER_PART_NUMBER") "621-AP64501SP-13"))
      (libsource (lib "eagle-import") (part "AP64501SP-13"))
    )
    (comp (ref "IC6")
      (value "AP64501SP-13")
      (footprint "eagle-import:SOIC127P600X163-9N")
      (fields (field (name "MOUSER_PART_NUMBER") "621-AP64501SP-13"))
      (libsource (lib "eagle-import") (part "AP64501SP-13"))
    )
    (comp (ref "J1")
      (value "PJ-079BH")
      (footprint "eagle-import:PJ079BH")
      (fields (field (name "MOUSER_PART_NUMBER") "490-PJ-079BH"))
      (libsource (lib "eagle-import") (part "PJ-079BH"))
    )
    (comp (ref "L1")
      (value "SRN6045TA-3R3Y")
      (footprint "eagle-import:SRN6045TA330M")
      (fields (field (name "MOUSER_PART_NUMBER") "652-SRN6045TA-3R3Y"))
      (libsource (lib "eagle-import") (part "SRN6045TA-3R3Y"))
    )
    (comp (ref "L2")
      (value "SRN6045TA-3R3Y")
      (footprint "eagle-import:SRN6045TA330M")
      (fields (field (name "MOUSER_PART_NUMBER") "652-SRN6045TA-3R3Y"))
      (libsource (lib "eagle-import") (part "SRN6045TA-3R3Y"))
    )
    (comp (ref "Q1")
      (value "DMP3013SFV-7")
      (footprint "eagle-import:DMP3013SFV7")
      (fields (field (name "MOUSER_PART_NUMBER") "621-DMP3013SFV-7"))
      (libsource (lib "eagle-import") (part "DMP3013SFV-7"))
    )
    (comp (ref "R1")
      (value "12k 1%")
      (footprint "eagle-import:M0805")
      (libsource (lib "eagle-import") (part "R-EU_M0805"))
    )
    (comp (ref "R2")
      (value "10R")
      (footprint "eagle-import:M0805")
      (libsource (lib "eagle-import") (part "R-EU_M0805"))
    )
    (comp (ref "R3")
      (value "12K 1%")
      (footprint "eagle-import:M0805")
      (libsource (lib "eagle-import") (part "R-EU_M0805"))
    )
    (comp (ref "R4")
      (value "2.2K 1%")
      (footprint "eagle-import:M0805")
      (libsource (lib "eagle-import") (part "R-EU_M0805"))
    )
    (comp (ref "R5")
      (value "20K 1%")
      (footprint "eagle-import:M0805")
      (libsource (lib "eagle-import") (part "R-EU_M0805"))
    )
    (comp (ref "R23")
      (value "10R")
      (footprint "eagle-import:M0805")
      (libsource (lib "eagle-import") (part "R-EU_M0805"))
    )
    (comp (ref "R24")
      (value "47K 1%")
      (footprint "eagle-import:M0805")
      (libsource (lib "eagle-import") (part "R-EU_M0805"))
    )
    (comp (ref "R25")
      (value "15K 1%")
      (footprint "eagle-import:M0805")
      (libsource (lib "eagle-import") (part "R-EU_M0805"))
    )
    (comp (ref "R26")
      (value "12K 1%")
      (footprint "eagle-import:M0805")
      (libsource (lib "eagle-import") (part "R-EU_M0805"))
    )
    (comp (ref "Z1")
      (value "MMBZ5242BLT3G")
      (footprint "eagle-import:SOT96P237X111-3N")
      (fields (field (name "MOUSER_PART_NUMBER") "863-MMBZ5242BLT3G"))
      (libsource (lib "eagle-import") (part "MMBZ5242BLT3G"))
    )
    (comp (ref "J13")
      (value "2199230-2")
      (footprint "eagle-import:CONN67_2199230_TEC")
      (fields (field (name "COPYRIGHT") "Copyright (C) 2018 Accelerated Designs. All rights reserved"))
      (libsource (lib "eagle-import") (part "2199230-2"))
    )
    (comp (ref "J14")
      (value "2199230-2")
      (footprint "eagle-import:CONN67_2199230_TEC")
      (fields (field (name "COPYRIGHT") "Copyright (C) 2018 Accelerated Designs. All rights reserved"))
      (libsource (lib "eagle-import") (part "2199230-2"))
    )
    (comp (ref "J15")
      (value "2199230-2")
      (footprint "eagle-import:CONN67_2199230_TEC")
      (fields (field (name "COPYRIGHT") "Copyright (C) 2018 Accelerated Designs. All rights reserved"))
      (libsource (lib "eagle-import") (part "2199230-2"))
    )
    (comp (ref "J16")
      (value "2199230-2")
      (footprint "eagle-import:CONN67_2199230_TEC")
      (fields (field (name "COPYRIGHT") "Copyright (C) 2018 Accelerated Designs. All rights reserved"))
      (libsource (lib "eagle-import") (part "2199230-2"))
    )
    (comp (ref "C21")
      (value "100nF")
      (footprint "eagle-import:C0805K")
      (libsource (lib "eagle-import") (part "C-EUC0805K"))
    )
    (comp (ref "IC3")
      (value "EMC2301-1-ACZL-TR")
      (footprint "eagle-import:SOP65P490X110-8N")
      (fields (field (name "MOUSER_PART_NUMBER") "886-EMC2301-1-ACZLTR"))
      (libsource (lib "eagle-import") (part "EMC2301-1-ACZL-TR"))
    )
    (comp (ref "JP1")
      (value "PINHD-1X4")
      (footprint "eagle-import:1X04")
      (libsource (lib "eagle-import") (part "PINHD-1X4"))
    )
    (comp (ref "R14")
      (value "26K 1%")
      (footprint "eagle-import:M0805")
      (libsource (lib "eagle-import") (part "R-EU_M0805"))
    )
  )
  (nets
    (net (code "1") (name "+1.8V") (class "Default")
      (node (ref "R16") (pin "1") (pinfunction "1_1") (pintype "passive"))
      (node (ref "RPI-CM1") (pin "88") (pinfunction "CM4_1.8V(OUTPUT)_88") (pintype "passive"))
      (node (ref "RPI-CM1") (pin "90") (pinfunction "CM4_1.8V(OUTPUT)_90") (pintype "passive"))
    )
    (net (code "2") (name "+3V3") (class "Default")
      (node (ref "C21") (pin "1") (pinfunction "1_1") (pintype "passive"))
      (node (ref "IC2") (pin "17") (pinfunction "EXT_RST#_17") (pintype "bidirectional"))
      (node (ref "IC2") (pin "21") (pinfunction "VCC33_21") (pintype "bidirectional"))
      (node (ref "IC2") (pin "26") (pinfunction "OVC#_26") (pintype "bidirectional"))
      (node (ref "IC2") (pin "27") (pinfunction "TEST#/SDA_27") (pintype "bidirectional"))
      (node (ref "IC3") (pin "3") (pinfunction "VDD_3") (pintype "bidirectional"))
      (node (ref "J10") (pin "22") (pinfunction "22_22") (pintype "bidirectional"))
      (node (ref "J11") (pin "22") (pinfunction "22_22") (pintype "bidirectional"))
      (node (ref "J12") (pin "22") (pinfunction "22_22") (pintype "bidirectional"))
      (node (ref "J13") (pin "2") (pinfunction "2_2") (pintype "passive"))
      (node (ref "J13") (pin "4") (pinfunction "4_4") (pintype "passive"))
      (node (ref "J13") (pin "72") (pinfunction "72_72") (pintype "passive"))
      (node (ref "J13") (pin "74") (pinfunction "74_74") (pintype "passive"))
      (node (ref "J14") (pin "2") (pinfunction "2_2") (pintype "passive"))
      (node (ref "J14") (pin "4") (pinfunction "4_4") (pintype "passive"))
      (node (ref "J14") (pin "72") (pinfunction "72_72") (pintype "passive"))
      (node (ref "J14") (pin "74") (pinfunction "74_74") (pintype "passive"))
      (node (ref "J15") (pin "2") (pinfunction "2_2") (pintype "passive"))
      (node (ref "J15") (pin "4") (pinfunction "4_4") (pintype "passive"))
      (node (ref "J15") (pin "72") (pinfunction "72_72") (pintype "passive"))
      (node (ref "J15") (pin "74") (pinfunction "74_74") (pintype "passive"))
      (node (ref "J16") (pin "2") (pinfunction "2_2") (pintype "passive"))
      (node (ref "J16") (pin "4") (pinfunction "4_4") (pintype "passive"))
      (node (ref "J16") (pin "72") (pinfunction "72_72") (pintype "passive"))
      (node (ref "J16") (pin "74") (pinfunction "74_74") (pintype "passive"))
      (node (ref "J5") (pin "4") (pinfunction "VDD_4") (pintype "bidirectional"))
      (node (ref "J7") (pin "P15") (pinfunction "ANODE_GREEN_P15") (pintype "bidirectional"))
      (node (ref "J7") (pin "P17") (pinfunction "ANODE_YELLOW_P17") (pintype "bidirectional"))
      (node (ref "J9") (pin "22") (pinfunction "22_22") (pintype "bidirectional"))
      (node (ref "JP2") (pin "1") (pinfunction "1_1") (pintype "passive"))
      (node (ref "JP2") (pin "17") (pinfunction "17_17") (pintype "passive"))
      (node (ref "LED1") (pin "A") (pinfunction "A_A") (pintype "passive"))
      (node (ref "LED2") (pin "A") (pinfunction "A_A") (pintype "passive"))
      (node (ref "R14") (pin "2") (pinfunction "2_2") (pintype "passive"))
      (node (ref "R15") (pin "1") (pinfunction "1_1") (pintype "passive"))
      (node (ref "R18") (pin "1") (pinfunction "1_1") (pintype "passive"))
      (node (ref "RPI-CM1") (pin "84") (pinfunction "CM4_3.3V(OUTPUT)_84") (pintype "passive"))
      (node (ref "RPI-CM1") (pin "86") (pinfunction "CM4_3.3V(OUTPUT)_86") (pintype "passive"))
      (node (ref "U1") (pin "1") (pinfunction "VCC_1") (pintype "bidirectional"))
      (node (ref "U2") (pin "5") (pinfunction "VCC_5") (pintype "bidirectional"))
    )
    (net (code "3") (name "+3V3_PCIE") (class "Default")
      (node (ref "C32") (pin "1") (pinfunction "1_1") (pintype "passive"))
      (node (ref "C33") (pin "1") (pinfunction "1_1") (pintype "passive"))
      (node (ref "C34") (pin "1") (pinfunction "1_1") (pintype "passive"))
      (node (ref "C35") (pin "1") (pinfunction "1_1") (pintype "passive"))
      (node (ref "C36") (pin "1") (pinfunction "1_1") (pintype "passive"))
      (node (ref "C37") (pin "1") (pinfunction "1_1") (pintype "passive"))
      (node (ref "L2") (pin "2") (pinfunction "2_2") (pintype "bidirectional"))
      (node (ref "R24") (pin "2") (pinfunction "2_2") (pintype "passive"))
    )
    (net (code "4") (name "+5V") (class "Default")
      (node (ref "C12") (pin "1") (pinfunction "1_1") (pintype "passive"))
      (node (ref "C13") (pin "1") (pinfunction "1_1") (pintype "passive"))
      (node (ref "C14") (pin "1") (pinfunction "1_1") (pintype "passive"))
      (node (ref "C15") (pin "1") (pinfunction "1_1") (pintype "passive"))
      (node (ref "C16") (pin "1") (pinfunction "1_1") (pintype "passive"))
      (node (ref "C17") (pin "1") (pinfunction "1_1") (pintype "passive"))
      (node (ref "JP2") (pin "2") (pinfunction "2_2") (pintype "passive"))
      (node (ref "JP2") (pin "4") (pinfunction "4_4") (pintype "passive"))
      (node (ref "L1") (pin "2") (pinfunction "2_2") (pintype "bidirectional"))
      (node (ref "R10") (pin "1") (pinfunction "1_1") (pintype "passive"))
      (node (ref "R3") (pin "2") (pinfunction "2_2") (pintype "passive"))
      (node (ref "RPI-CM1") (pin "77") (pinfunction "+5V(INPUT)_77") (pintype "passive"))
      (node (ref "RPI-CM1") (pin "79") (pinfunction "+5V(INPUT)_79") (pintype "passive"))
      (node (ref "RPI-CM1") (pin "81") (pinfunction "+5V(INPUT)_81") (pintype "passive"))
      (node (ref "RPI-CM1") (pin "83") (pinfunction "+5V(INPUT)_83") (pintype "passive"))
      (node (ref "RPI-CM1") (pin "85") (pinfunction "+5V(INPUT)_85") (pintype "passive"))
      (node (ref "RPI-CM1") (pin "87") (pinfunction "+5V(INPUT)_87") (pintype "passive"))
      (node (ref "U3") (pin "5") (pinfunction "VCC_5") (pintype "bidirectional"))
    )
    (net (code "5") (name "+12V") (class "Default")
      (node (ref "C1") (pin "1") (pinfunction "1_1") (pintype "passive"))
      (node (ref "C2") (pin "2") (pinfunction "2_2") (pintype "passive"))
      (node (ref "C24") (pin "1") (pinfunction "1_1") (pintype "passive"))
      (node (ref "C25") (pin "1") (pinfunction "1_1") (pintype "passive"))
      (node (ref "C26") (pin "1") (pinfunction "1_1") (pintype "passive"))
      (node (ref "C27") (pin "1") (pinfunction "1_1") (pintype "passive"))
      (node (ref "C28") (pin "1") (pinfunction "1_1") (pintype "passive"))
      (node (ref "C29") (pin "1") (pinfunction "1_1") (pintype "passive"))
      (node (ref "C3") (pin "1") (pinfunction "1_1") (pintype "passive"))
      (node (ref "C4") (pin "1") (pinfunction "1_1") (pintype "passive"))
      (node (ref "C5") (pin "1") (pinfunction "1_1") (pintype "passive"))
      (node (ref "C6") (pin "1") (pinfunction "1_1") (pintype "passive"))
      (node (ref "C7") (pin "1") (pinfunction "1_1") (pintype "passive"))
      (node (ref "C8") (pin "1") (pinfunction "1_1") (pintype "passive"))
      (node (ref "C9") (pin "1") (pinfunction "1_1") (pintype "passive"))
      (node (ref "IC1") (pin "2") (pinfunction "VIN_2") (pintype "bidirectional"))
      (node (ref "IC1") (pin "3") (pinfunction "EN_3") (pintype "bidirectional"))
      (node (ref "IC6") (pin "2") (pinfunction "VIN_2") (pintype "bidirectional"))
      (node (ref "IC6") (pin "3") (pinfunction "EN_3") (pintype "bidirectional"))
      (node (ref "J1") (pin "1") (pinfunction "1_1") (pintype "bidirectional"))
      (node (ref "JP1") (pin "2") (pinfunction "2_2") (pintype "passive"))
      (node (ref "Q1") (pin "1") (pinfunction "S_1_1") (pintype "bidirectional"))
      (node (ref "Q1") (pin "2") (pinfunction "S_2_2") (pintype "bidirectional"))
      (node (ref "Q1") (pin "3") (pinfunction "S_3_3") (pintype "bidirectional"))
      (node (ref "Z1") (pin "3") (pinfunction "K_3") (pintype "bidirectional"))
    )
    (net (code "6") (name "AIN0") (class "Default")
      (node (ref "JP7") (pin "5") (pinfunction "5_5") (pintype "passive"))
    )
    (net (code "7") (name "AIN1") (class "Default")
      (node (ref "JP7") (pin "6") (pinfunction "6_6") (pintype "passive"))
      (node (ref "RPI-CM1") (pin "94") (pinfunction "ANALOGP1_94") (pintype "passive"))
    )
    (net (code "8") (name "AIN2") (class "Default")
      (node (ref "RPI-CM1") (pin "96") (pinfunction "ANALOGP0_96") (pintype "passive"))
    )
    (net (code "9") (name "BT_NDIS") (class "Default")
      (node (ref "JP5") (pin "3") (pinfunction "3_3") (pintype "passive"))
      (node (ref "RPI-CM1") (pin "91") (pinfunction "BT_~{DISABLE}_91") (pintype "passive"))
    )
    (net (code "10") (name "CAM0_C_N") (class "Default")
      (node (ref "J11") (pin "8") (pinfunction "8_8") (pintype "bidirectional"))
      (node (ref "RPI-CM1") (pin "140") (pinfunction "CAM0_C_N_140") (pintype "passive"))
    )
    (net (code "11") (name "CAM0_C_P") (class "Default")
      (node (ref "J11") (pin "9") (pinfunction "9_9") (pintype "bidirectional"))
      (node (ref "RPI-CM1") (pin "142") (pinfunction "CAM0_C_P_142") (pintype "passive"))
    )
    (net (code "12") (name "CAM0_D0_N") (class "Default")
      (node (ref "J11") (pin "2") (pinfunction "2_2") (pintype "bidirectional"))
      (node (ref "RPI-CM1") (pin "128") (pinfunction "CAM0_D0_N_128") (pintype "passive"))
    )
    (net (code "13") (name "CAM0_D0_P") (class "Default")
      (node (ref "J11") (pin "3") (pinfunction "3_3") (pintype "bidirectional"))
      (node (ref "RPI-CM1") (pin "130") (pinfunction "CAM0_D0_P_130") (pintype "passive"))
    )
    (net (code "14") (name "CAM0_D1_N") (class "Default")
      (node (ref "J11") (pin "5") (pinfunction "5_5") (pintype "bidirectional"))
      (node (ref "RPI-CM1") (pin "134") (pinfunction "CAM0_D1_N_134") (pintype "passive"))
    )
    (net (code "15") (name "CAM0_D1_P") (class "Default")
      (node (ref "J11") (pin "6") (pinfunction "6_6") (pintype "bidirectional"))
      (node (ref "RPI-CM1") (pin "136") (pinfunction "CAM0_D1_P_136") (pintype "passive"))
    )
    (net (code "16") (name "CAM1_C_N") (class "Default")
      (node (ref "J12") (pin "8") (pinfunction "8_8") (pintype "bidirectional"))
      (node (ref "RPI-CM1") (pin "127") (pinfunction "CAM1_C_N_127") (pintype "passive"))
    )
    (net (code "17") (name "CAM1_C_P") (class "Default")
      (node (ref "J12") (pin "9") (pinfunction "9_9") (pintype "bidirectional"))
      (node (ref "RPI-CM1") (pin "129") (pinfunction "CAM1_C_P_129") (pintype "passive"))
    )
    (net (code "18") (name "CAM1_D0_N") (class "Default")
      (node (ref "J12") (pin "2") (pinfunction "2_2") (pintype "bidirectional"))
      (node (ref "RPI-CM1") (pin "115") (pinfunction "CAM1_D0_N_115") (pintype "passive"))
    )
    (net (code "19") (name "CAM1_D0_P") (class "Default")
      (node (ref "J12") (pin "3") (pinfunction "3_3") (pintype "bidirectional"))
      (node (ref "RPI-CM1") (pin "117") (pinfunction "CAM1_D0_P_117") (pintype "passive"))
    )
    (net (code "20") (name "CAM1_D1_N") (class "Default")
      (node (ref "J12") (pin "5") (pinfunction "5_5") (pintype "bidirectional"))
      (node (ref "RPI-CM1") (pin "121") (pinfunction "CAM1_D1_N_121") (pintype "passive"))
    )
    (net (code "21") (name "CAM1_D1_P") (class "Default")
      (node (ref "J12") (pin "6") (pinfunction "6_6") (pintype "bidirectional"))
      (node (ref "RPI-CM1") (pin "123") (pinfunction "CAM1_D1_P_123") (pintype "passive"))
    )
    (net (code "22") (name "CAM1_D2_N") (class "Default")
      (node (ref "J12") (pin "11") (pinfunction "11_11") (pintype "bidirectional"))
      (node (ref "RPI-CM1") (pin "133") (pinfunction "CAM1_D2_N_133") (pintype "passive"))
    )
    (net (code "23") (name "CAM1_D2_P") (class "Default")
      (node (ref "J12") (pin "12") (pinfunction "12_12") (pintype "bidirectional"))
      (node (ref "RPI-CM1") (pin "135") (pinfunction "CAM1_D2_P_135") (pintype "passive"))
    )
    (net (code "24") (name "CAM1_D3_N") (class "Default")
      (node (ref "J12") (pin "14") (pinfunction "14_14") (pintype "bidirectional"))
      (node (ref "RPI-CM1") (pin "139") (pinfunction "CAM1_D3_N_139") (pintype "passive"))
    )
    (net (code "25") (name "CAM1_D3_P") (class "Default")
      (node (ref "J12") (pin "15") (pinfunction "15_15") (pintype "bidirectional"))
      (node (ref "RPI-CM1") (pin "141") (pinfunction "CAM1_D3_P_141") (pintype "passive"))
    )
    (net (code "26") (name "CAM_GPIO") (class "Default")
      (node (ref "J11") (pin "17") (pinfunction "17_17") (pintype "bidirectional"))
      (node (ref "J12") (pin "17") (pinfunction "17_17") (pintype "bidirectional"))
      (node (ref "RPI-CM1") (pin "97") (pinfunction "CAMERA_GPIO_97") (pintype "passive"))
    )
    (net (code "27") (name "CC1") (class "Default")
      (node (ref "J2") (pin "A5") (pinfunction "CC1_A5") (pintype "bidirectional"))
      (node (ref "R8") (pin "1") (pinfunction "1_1") (pintype "passive"))
    )
    (net (code "28") (name "CC2") (class "Default")
      (node (ref "J2") (pin "B5") (pinfunction "CC2_B5") (pintype "bidirectional"))
      (node (ref "R9") (pin "1") (pinfunction "1_1") (pintype "passive"))
    )
    (net (code "29") (name "CRYSTAL_1") (class "Default")
      (node (ref "IC2") (pin "3") (pinfunction "XTALIN_3") (pintype "bidirectional"))
      (node (ref "Y1") (pin "1") (pinfunction "CRYSTAL_1_1") (pintype "bidirectional"))
    )
    (net (code "30") (name "CRYSTAL_2") (class "Default")
      (node (ref "IC2") (pin "2") (pinfunction "XTALOUT_2") (pintype "bidirectional"))
      (node (ref "Y1") (pin "3") (pinfunction "CRYSTAL_2_3") (pintype "bidirectional"))
    )
    (net (code "31") (name "DSI0_C_N") (class "Default")
      (node (ref "J9") (pin "8") (pinfunction "8_8") (pintype "bidirectional"))
      (node (ref "RPI-CM1") (pin "169") (pinfunction "DSI0_C_N_169") (pintype "passive"))
    )
    (net (code "32") (name "DSI0_C_P") (class "Default")
      (node (ref "J9") (pin "9") (pinfunction "9_9") (pintype "bidirectional"))
      (node (ref "RPI-CM1") (pin "171") (pinfunction "DSI0_C_P_171") (pintype "passive"))
    )
    (net (code "33") (name "DSI0_D0_N") (class "Default")
      (node (ref "J9") (pin "2") (pinfunction "2_2") (pintype "bidirectional"))
      (node (ref "RPI-CM1") (pin "157") (pinfunction "DSI0_D0_N_157") (pintype "passive"))
    )
    (net (code "34") (name "DSI0_D0_P") (class "Default")
      (node (ref "J9") (pin "3") (pinfunction "3_3") (pintype "bidirectional"))
      (node (ref "RPI-CM1") (pin "159") (pinfunction "DSI0_D0_P_159") (pintype "passive"))
    )
    (net (code "35") (name "DSI0_D1_N") (class "Default")
      (node (ref "J9") (pin "5") (pinfunction "5_5") (pintype "bidirectional"))
      (node (ref "RPI-CM1") (pin "163") (pinfunction "DSI0_D1_N_163") (pintype "passive"))
    )
    (net (code "36") (name "DSI0_D1_P") (class "Default")
      (node (ref "J9") (pin "6") (pinfunction "6_6") (pintype "bidirectional"))
      (node (ref "RPI-CM1") (pin "165") (pinfunction "DSI0_D1_P_165") (pintype "passive"))
    )
    (net (code "37") (name "DSI1_C_N") (class "Default")
      (node (ref "J10") (pin "8") (pinfunction "8_8") (pintype "bidirectional"))
      (node (ref "RPI-CM1") (pin "187") (pinfunction "DSI1_C_N_187") (pintype "passive"))
    )
    (net (code "38") (name "DSI1_C_P") (class "Default")
      (node (ref "J10") (pin "9") (pinfunction "9_9") (pintype "bidirectional"))
      (node (ref "RPI-CM1") (pin "189") (pinfunction "DSI1_C_P_189") (pintype "passive"))
    )
    (net (code "39") (name "DSI1_D0_N") (class "Default")
      (node (ref "J10") (pin "2") (pinfunction "2_2") (pintype "bidirectional"))
      (node (ref "RPI-CM1") (pin "175") (pinfunction "DSI1_D0_N_175") (pintype "passive"))
    )
    (net (code "40") (name "DSI1_D0_P") (class "Default")
      (node (ref "J10") (pin "3") (pinfunction "3_3") (pintype "bidirectional"))
      (node (ref "RPI-CM1") (pin "177") (pinfunction "DSI1_D0_P_177") (pintype "passive"))
    )
    (net (code "41") (name "DSI1_D1_N") (class "Default")
      (node (ref "J10") (pin "5") (pinfunction "5_5") (pintype "bidirectional"))
      (node (ref "RPI-CM1") (pin "181") (pinfunction "DSI1_D1_N_181") (pintype "passive"))
    )
    (net (code "42") (name "DSI1_D1_P") (class "Default")
      (node (ref "J10") (pin "6") (pinfunction "6_6") (pintype "bidirectional"))
      (node (ref "RPI-CM1") (pin "183") (pinfunction "DSI1_D1_P_183") (pintype "passive"))
    )
    (net (code "43") (name "DSI1_D2_N") (class "Default")
      (node (ref "J10") (pin "11") (pinfunction "11_11") (pintype "bidirectional"))
      (node (ref "RPI-CM1") (pin "193") (pinfunction "DSI1_D2_N_193") (pintype "passive"))
    )
    (net (code "44") (name "DSI1_D2_P") (class "Default")
      (node (ref "J10") (pin "12") (pinfunction "12_12") (pintype "bidirectional"))
      (node (ref "RPI-CM1") (pin "195") (pinfunction "DSI1_D2_P_195") (pintype "passive"))
    )
    (net (code "45") (name "DSI1_D3_N") (class "Default")
      (node (ref "J10") (pin "14") (pinfunction "14_14") (pintype "bidirectional"))
      (node (ref "RPI-CM1") (pin "194") (pinfunction "DSI1_D3_N_194") (pintype "passive"))
    )
    (net (code "46") (name "DSI1_D3_P") (class "Default")
      (node (ref "J10") (pin "15") (pinfunction "15_15") (pintype "bidirectional"))
      (node (ref "RPI-CM1") (pin "196") (pinfunction "DSI1_D3_P_196") (pintype "passive"))
    )
    (net (code "47") (name "EEPROM_NWP") (class "Default")
      (node (ref "JP7") (pin "4") (pinfunction "4_4") (pintype "passive"))
      (node (ref "RPI-CM1") (pin "20") (pinfunction "EEPROM_~{WP}_20") (pintype "passive"))
    )
    (net (code "48") (name "ETH_LEDG") (class "Default")
      (node (ref "R20") (pin "2") (pinfunction "2_2") (pintype "passive"))
      (node (ref "RPI-CM1") (pin "17") (pinfunction "ETH_~{LED2}_17") (pintype "passive"))
    )
    (net (code "49") (name "ETH_LEDY") (class "Default")
      (node (ref "R19") (pin "2") (pinfunction "2_2") (pintype "passive"))
      (node (ref "RPI-CM1") (pin "15") (pinfunction "ETH_~{LED3}_15") (pintype "passive"))
    )
    (net (code "50") (name "GLOBAL_EN") (class "Default")
      (node (ref "JP6") (pin "1") (pinfunction "1_1") (pintype "passive"))
      (node (ref "JP7") (pin "14") (pinfunction "14_14") (pintype "passive"))
      (node (ref "RPI-CM1") (pin "99") (pinfunction "GLOBAL_EN_99") (pintype "passive"))
    )
    (net (code "51") (name "GND") (class "Default")
      (node (ref "C1") (pin "2") (pinfunction "2_2") (pintype "passive"))
      (node (ref "C10") (pin "2") (pinfunction "2_2") (pintype "passive"))
      (node (ref "C12") (pin "2") (pinfunction "2_2") (pintype "passive"))
      (node (ref "C13") (pin "2") (pinfunction "2_2") (pintype "passive"))
      (node (ref "C14") (pin "2") (pinfunction "2_2") (pintype "passive"))
      (node (ref "C15") (pin "2") (pinfunction "2_2") (pintype "passive"))
      (node (ref "C16") (pin "2") (pinfunction "2_2") (pintype "passive"))
      (node (ref "C18") (pin "2") (pinfunction "2_2") (pintype "passive"))
      (node (ref "C19") (pin "2") (pinfunction "2_2") (pintype "passive"))
      (node (ref "C20") (pin "2") (pinfunction "2_2") (pintype "passive"))
      (node (ref "C21") (pin "2") (pinfunction "2_2") (pintype "passive"))
      (node (ref "C22") (pin "2") (pinfunction "2_2") (pintype "passive"))
      (node (ref "C23") (pin "2") (pinfunction "2_2") (pintype "passive"))
      (node (ref "C24") (pin "2") (pinfunction "2_2") (pintype "passive"))
      (node (ref "C25") (pin "2") (pinfunction "2_2") (pintype "passive"))
      (node (ref "C26") (pin "2") (pinfunction "2_2") (pintype "passive"))
      (node (ref "C27") (pin "2") (pinfunction "2_2") (pintype "passive"))
      (node (ref "C28") (pin "2") (pinfunction "2_2") (pintype "passive"))
      (node (ref "C29") (pin "2") (pinfunction "2_2") (pintype "passive"))
      (node (ref "C3") (pin "2") (pinfunction "2_2") (pintype "passive"))
      (node (ref "C30") (pin "2") (pinfunction "2_2") (pintype "passive"))
      (node (ref "C32") (pin "2") (pinfunction "2_2") (pintype "passive"))
      (node (ref "C33") (pin "2") (pinfunction "2_2") (pintype "passive"))
      (node (ref "C34") (pin "2") (pinfunction "2_2") (pintype "passive"))
      (node (ref "C35") (pin "2") (pinfunction "2_2") (pintype "passive"))
      (node (ref "C36") (pin "2") (pinfunction "2_2") (pintype "passive"))
      (node (ref "C38") (pin "2") (pinfunction "2_2") (pintype "passive"))
      (node (ref "C39") (pin "2") (pinfunction "2_2") (pintype "passive"))
      (node (ref "C4") (pin "2") (pinfunction "2_2") (pintype "passive"))
      (node (ref "C5") (pin "2") (pinfunction "2_2") (pintype "passive"))
      (node (ref "C6") (pin "2") (pinfunction "2_2") (pintype "passive"))
      (node (ref "C7") (pin "2") (pinfunction "2_2") (pintype "passive"))
      (node (ref "C8") (pin "2") (pinfunction "2_2") (pintype "passive"))
      (node (ref "C9") (pin "2") (pinfunction "2_2") (pintype "passive"))
      (node (ref "IC1") (pin "7") (pinfunction "GND_7") (pintype "bidirectional"))
      (node (ref "IC1") (pin "9") (pinfunction "EP_9") (pintype "bidirectional"))
      (node (ref "IC2") (pin "1") (pinfunction "GND_1") (pintype "power_in"))
      (node (ref "IC2") (pin "19") (pinfunction "BUS_PWR#_19") (pintype "bidirectional"))
      (node (ref "IC3") (pin "4") (pinfunction "GND_4") (pintype "bidirectional"))
      (node (ref "IC4") (pin "3") (pinfunction "GND_1_3") (pintype "bidirectional"))
      (node (ref "IC5") (pin "3") (pinfunction "GND_1_3") (pintype "bidirectional"))
      (node (ref "IC6") (pin "7") (pinfunction "GND_7") (pintype "bidirectional"))
      (node (ref "IC6") (pin "9") (pinfunction "EP_9") (pintype "bidirectional"))
      (node (ref "J1") (pin "2") (pinfunction "2_2") (pintype "bidirectional"))
      (node (ref "J1") (pin "3") (pinfunction "3_3") (pintype "bidirectional"))
      (node (ref "J1") (pin "MH1") (pinfunction "MH1_MH1") (pintype "bidirectional"))
      (node (ref "J1") (pin "MH2") (pinfunction "MH2_MH2") (pintype "bidirectional"))
      (node (ref "J10") (pin "1") (pinfunction "1_1") (pintype "bidirectional"))
      (node (ref "J10") (pin "10") (pinfunction "10_10") (pintype "bidirectional"))
      (node (ref "J10") (pin "13") (pinfunction "13_13") (pintype "bidirectional"))
      (node (ref "J10") (pin "16") (pinfunction "16_16") (pintype "bidirectional"))
      (node (ref "J10") (pin "19") (pinfunction "19_19") (pintype "bidirectional"))
      (node (ref "J10") (pin "4") (pinfunction "4_4") (pintype "bidirectional"))
      (node (ref "J10") (pin "7") (pinfunction "7_7") (pintype "bidirectional"))
      (node (ref "J11") (pin "1") (pinfunction "1_1") (pintype "bidirectional"))
      (node (ref "J11") (pin "10") (pinfunction "10_10") (pintype "bidirectional"))
      (node (ref "J11") (pin "13") (pinfunction "13_13") (pintype "bidirectional"))
      (node (ref "J11") (pin "16") (pinfunction "16_16") (pintype "bidirectional"))
      (node (ref "J11") (pin "19") (pinfunction "19_19") (pintype "bidirectional"))
      (node (ref "J11") (pin "4") (pinfunction "4_4") (pintype "bidirectional"))
      (node (ref "J11") (pin "7") (pinfunction "7_7") (pintype "bidirectional"))
      (node (ref "J12") (pin "1") (pinfunction "1_1") (pintype "bidirectional"))
      (node (ref "J12") (pin "10") (pinfunction "10_10") (pintype "bidirectional"))
      (node (ref "J12") (pin "13") (pinfunction "13_13") (pintype "bidirectional"))
      (node (ref "J12") (pin "16") (pinfunction "16_16") (pintype "bidirectional"))
      (node (ref "J12") (pin "19") (pinfunction "19_19") (pintype "bidirectional"))
      (node (ref "J12") (pin "4") (pinfunction "4_4") (pintype "bidirectional"))
      (node (ref "J12") (pin "7") (pinfunction "7_7") (pintype "bidirectional"))
      (node (ref "J13") (pin "1") (pinfunction "1_1") (pintype "passive"))
      (node (ref "J13") (pin "18") (pinfunction "18_18") (pintype "passive"))
      (node (ref "J13") (pin "33") (pinfunction "33_33") (pintype "passive"))
      (node (ref "J13") (pin "39") (pinfunction "39_39") (pintype "passive"))
      (node (ref "J13") (pin "45") (pinfunction "45_45") (pintype "passive"))
      (node (ref "J13") (pin "51") (pinfunction "51_51") (pintype "passive"))
      (node (ref "J13") (pin "57") (pinfunction "57_57") (pintype "passive"))
      (node (ref "J13") (pin "69") (pinfunction "69_69") (pintype "passive"))
      (node (ref "J13") (pin "7") (pinfunction "7_7") (pintype "passive"))
      (node (ref "J13") (pin "75") (pinfunction "75_75") (pintype "passive"))
      (node (ref "J14") (pin "1") (pinfunction "1_1") (pintype "passive"))
      (node (ref "J14") (pin "18") (pinfunction "18_18") (pintype "passive"))
      (node (ref "J14") (pin "33") (pinfunction "33_33") (pintype "passive"))
      (node (ref "J14") (pin "39") (pinfunction "39_39") (pintype "passive"))
      (node (ref "J14") (pin "45") (pinfunction "45_45") (pintype "passive"))
      (node (ref "J14") (pin "51") (pinfunction "51_51") (pintype "passive"))
      (node (ref "J14") (pin "57") (pinfunction "57_57") (pintype "passive"))
      (node (ref "J14") (pin "69") (pinfunction "69_69") (pintype "passive"))
      (node (ref "J14") (pin "7") (pinfunction "7_7") (pintype "passive"))
      (node (ref "J14") (pin "75") (pinfunction "75_75") (pintype "passive"))
      (node (ref "J15") (pin "1") (pinfunction "1_1") (pintype "passive"))
      (node (ref "J15") (pin "18") (pinfunction "18_18") (pintype "passive"))
      (node (ref "J15") (pin "33") (pinfunction "33_33") (pintype "passive"))
      (node (ref "J15") (pin "39") (pinfunction "39_39") (pintype "passive"))
      (node (ref "J15") (pin "45") (pinfunction "45_45") (pintype "passive"))
      (node (ref "J15") (pin "51") (pinfunction "51_51") (pintype "passive"))
      (node (ref "J15") (pin "57") (pinfunction "57_57") (pintype "passive"))
      (node (ref "J15") (pin "69") (pinfunction "69_69") (pintype "passive"))
      (node (ref "J15") (pin "7") (pinfunction "7_7") (pintype "passive"))
      (node (ref "J15") (pin "75") (pinfunction "75_75") (pintype "passive"))
      (node (ref "J16") (pin "1") (pinfunction "1_1") (pintype "passive"))
      (node (ref "J16") (pin "18") (pinfunction "18_18") (pintype "passive"))
      (node (ref "J16") (pin "33") (pinfunction "33_33") (pintype "passive"))
      (node (ref "J16") (pin "39") (pinfunction "39_39") (pintype "passive"))
      (node (ref "J16") (pin "45") (pinfunction "45_45") (pintype "passive"))
      (node (ref "J16") (pin "51") (pinfunction "51_51") (pintype "passive"))
      (node (ref "J16") (pin "57") (pinfunction "57_57") (pintype "passive"))
      (node (ref "J16") (pin "69") (pinfunction "69_69") (pintype "passive"))
      (node (ref "J16") (pin "7") (pinfunction "7_7") (pintype "passive"))
      (node (ref "J16") (pin "75") (pinfunction "75_75") (pintype "passive"))
      (node (ref "J2") (pin "A1") (pinfunction "GND_1_A1") (pintype "bidirectional"))
      (node (ref "J2") (pin "A12") (pinfunction "GND_2_A12") (pintype "bidirectional"))
      (node (ref "J2") (pin "B1") (pinfunction "GND_3_B1") (pintype "bidirectional"))
      (node (ref "J2") (pin "B12") (pinfunction "GND_4_B12") (pintype "bidirectional"))
      (node (ref "J2") (pin "S1") (pinfunction "GND_5_S1") (pintype "bidirectional"))
      (node (ref "J2") (pin "S2") (pinfunction "GND_6_S2") (pintype "bidirectional"))
      (node (ref "J2") (pin "S3") (pinfunction "GND_7_S3") (pintype "bidirectional"))
      (node (ref "J2") (pin "S4") (pinfunction "GND_8_S4") (pintype "bidirectional"))
      (node (ref "J3") (pin "4") (pinfunction "4_4") (pintype "passive"))
      (node (ref "J3") (pin "8") (pinfunction "8_8") (pintype "passive"))
      (node (ref "J3") (pin "S1") (pinfunction "SHIELD_S1") (pintype "passive"))
      (node (ref "J3") (pin "S2") (pinfunction "SHIELD_S2") (pintype "passive"))
      (node (ref "J3") (pin "S3") (pinfunction "SHIELD_S3") (pintype "passive"))
      (node (ref "J3") (pin "S4") (pinfunction "SHIELD_S4") (pintype "passive"))
      (node (ref "J4") (pin "4") (pinfunction "4_4") (pintype "passive"))
      (node (ref "J4") (pin "8") (pinfunction "8_8") (pintype "passive"))
      (node (ref "J4") (pin "S1") (pinfunction "SHIELD_S1") (pintype "passive"))
      (node (ref "J4") (pin "S2") (pinfunction "SHIELD_S2") (pintype "passive"))
      (node (ref "J4") (pin "S3") (pinfunction "SHIELD_S3") (pintype "passive"))
      (node (ref "J4") (pin "S4") (pinfunction "SHIELD_S4") (pintype "passive"))
      (node (ref "J5") (pin "6") (pinfunction "VSS_6") (pintype "bidirectional"))
      (node (ref "J6") (pin "11") (pinfunction "11_11") (pintype "bidirectional"))
      (node (ref "J6") (pin "17") (pinfunction "17_17") (pintype "bidirectional"))
      (node (ref "J6") (pin "2") (pinfunction "2_2") (pintype "bidirectional"))
      (node (ref "J6") (pin "5") (pinfunction "5_5") (pintype "bidirectional"))
      (node (ref "J6") (pin "8") (pinfunction "8_8") (pintype "bidirectional"))
      (node (ref "J6") (pin "MH1") (pinfunction "MH1_MH1") (pintype "bidirectional"))
      (node (ref "J6") (pin "MH2") (pinfunction "MH2_MH2") (pintype "bidirectional"))
      (node (ref "J6") (pin "MH3") (pinfunction "MH3_MH3") (pintype "bidirectional"))
      (node (ref "J6") (pin "MH4") (pinfunction "MH4_MH4") (pintype "bidirectional"))
      (node (ref "J7") (pin "MH1") (pinfunction "MH1_MH1") (pintype "bidirectional"))
      (node (ref "J7") (pin "MH2") (pinfunction "MH2_MH2") (pintype "bidirectional"))
      (node (ref "J8") (pin "11") (pinfunction "11_11") (pintype "bidirectional"))
      (node (ref "J8") (pin "17") (pinfunction "17_17") (pintype "bidirectional"))
      (node (ref "J8") (pin "2") (pinfunction "2_2") (pintype "bidirectional"))
      (node (ref "J8") (pin "5") (pinfunction "5_5") (pintype "bidirectional"))
      (node (ref "J8") (pin "8") (pinfunction "8_8") (pintype "bidirectional"))
      (node (ref "J8") (pin "MH1") (pinfunction "MH1_MH1") (pintype "bidirectional"))
      (node (ref "J8") (pin "MH2") (pinfunction "MH2_MH2") (pintype "bidirectional"))
      (node (ref "J8") (pin "MH3") (pinfunction "MH3_MH3") (pintype "bidirectional"))
      (node (ref "J8") (pin "MH4") (pinfunction "MH4_MH4") (pintype "bidirectional"))
      (node (ref "J9") (pin "1") (pinfunction "1_1") (pintype "bidirectional"))
      (node (ref "J9") (pin "10") (pinfunction "10_10") (pintype "bidirectional"))
      (node (ref "J9") (pin "13") (pinfunction "13_13") (pintype "bidirectional"))
      (node (ref "J9") (pin "16") (pinfunction "16_16") (pintype "bidirectional"))
      (node (ref "J9") (pin "19") (pinfunction "19_19") (pintype "bidirectional"))
      (node (ref "J9") (pin "4") (pinfunction "4_4") (pintype "bidirectional"))
      (node (ref "J9") (pin "7") (pinfunction "7_7") (pintype "bidirectional"))
      (node (ref "JP1") (pin "1") (pinfunction "1_1") (pintype "passive"))
      (node (ref "JP2") (pin "14") (pinfunction "14_14") (pintype "passive"))
      (node (ref "JP2") (pin "20") (pinfunction "20_20") (pintype "passive"))
      (node (ref "JP2") (pin "25") (pinfunction "25_25") (pintype "passive"))
      (node (ref "JP2") (pin "30") (pinfunction "30_30") (pintype "passive"))
      (node (ref "JP2") (pin "34") (pinfunction "34_34") (pintype "passive"))
      (node (ref "JP2") (pin "39") (pinfunction "39_39") (pintype "passive"))
      (node (ref "JP2") (pin "6") (pinfunction "6_6") (pintype "passive"))
      (node (ref "JP2") (pin "9") (pinfunction "9_9") (pintype "passive"))
      (node (ref "JP5") (pin "2") (pinfunction "2_2") (pintype "passive"))
      (node (ref "JP6") (pin "2") (pinfunction "2_2") (pintype "passive"))
      (node (ref "JP7") (pin "1") (pinfunction "1_1") (pintype "passive"))
      (node (ref "JP7") (pin "10") (pinfunction "10_10") (pintype "passive"))
      (node (ref "JP7") (pin "12") (pinfunction "12_12") (pintype "passive"))
      (node (ref "JP7") (pin "3") (pinfunction "3_3") (pintype "passive"))
      (node (ref "JP7") (pin "7") (pinfunction "7_7") (pintype "passive"))
      (node (ref "Q1") (pin "5") (pinfunction "D_1_5") (pintype "bidirectional"))
      (node (ref "Q1") (pin "6") (pinfunction "D_2_6") (pintype "bidirectional"))
      (node (ref "Q1") (pin "7") (pinfunction "D_3_7") (pintype "bidirectional"))
      (node (ref "Q1") (pin "8") (pinfunction "D_4_8") (pintype "bidirectional"))
      (node (ref "Q1") (pin "9") (pinfunction "D_5_9") (pintype "bidirectional"))
      (node (ref "R1") (pin "1") (pinfunction "1_1") (pintype "passive"))
      (node (ref "R11") (pin "1") (pinfunction "1_1") (pintype "passive"))
      (node (ref "R12") (pin "1") (pinfunction "1_1") (pintype "passive"))
      (node (ref "R13") (pin "1") (pinfunction "1_1") (pintype "passive"))
      (node (ref "R25") (pin "1") (pinfunction "1_1") (pintype "passive"))
      (node (ref "R4") (pin "1") (pinfunction "1_1") (pintype "passive"))
      (node (ref "R6") (pin "1") (pinfunction "1_1") (pintype "passive"))
      (node (ref "R8") (pin "2") (pinfunction "2_2") (pintype "passive"))
      (node (ref "R9") (pin "2") (pinfunction "2_2") (pintype "passive"))
      (node (ref "RPI-CM1") (pin "1") (pinfunction "GND_1") (pintype "passive"))
      (node (ref "RPI-CM1") (pin "107") (pinfunction "GND_107") (pintype "passive"))
      (node (ref "RPI-CM1") (pin "108") (pinfunction "GND_108") (pintype "passive"))
      (node (ref "RPI-CM1") (pin "113") (pinfunction "GND_113") (pintype "passive"))
      (node (ref "RPI-CM1") (pin "114") (pinfunction "GND_114") (pintype "passive"))
      (node (ref "RPI-CM1") (pin "119") (pinfunction "GND_119") (pintype "passive"))
      (node (ref "RPI-CM1") (pin "120") (pinfunction "GND_120") (pintype "passive"))
      (node (ref "RPI-CM1") (pin "125") (pinfunction "GND_125") (pintype "passive"))
      (node (ref "RPI-CM1") (pin "126") (pinfunction "GND_126") (pintype "passive"))
      (node (ref "RPI-CM1") (pin "13") (pinfunction "GND_13") (pintype "passive"))
      (node (ref "RPI-CM1") (pin "131") (pinfunction "GND_131") (pintype "passive"))
      (node (ref "RPI-CM1") (pin "132") (pinfunction "GND_132") (pintype "passive"))
      (node (ref "RPI-CM1") (pin "137") (pinfunction "GND_137") (pintype "passive"))
      (node (ref "RPI-CM1") (pin "138") (pinfunction "GND_138") (pintype "passive"))
      (node (ref "RPI-CM1") (pin "14") (pinfunction "GND_14") (pintype "passive"))
      (node (ref "RPI-CM1") (pin "144") (pinfunction "GND_144") (pintype "passive"))
      (node (ref "RPI-CM1") (pin "150") (pinfunction "GND_150") (pintype "passive"))
      (node (ref "RPI-CM1") (pin "155") (pinfunction "GND_155") (pintype "passive"))
      (node (ref "RPI-CM1") (pin "156") (pinfunction "GND_156") (pintype "passive"))
      (node (ref "RPI-CM1") (pin "161") (pinfunction "GND_161") (pintype "passive"))
      (node (ref "RPI-CM1") (pin "162") (pinfunction "GND_162") (pintype "passive"))
      (node (ref "RPI-CM1") (pin "167") (pinfunction "GND_167") (pintype "passive"))
      (node (ref "RPI-CM1") (pin "168") (pinfunction "GND_168") (pintype "passive"))
      (node (ref "RPI-CM1") (pin "173") (pinfunction "GND_173") (pintype "passive"))
      (node (ref "RPI-CM1") (pin "174") (pinfunction "GND_174") (pintype "passive"))
      (node (ref "RPI-CM1") (pin "179") (pinfunction "GND_179") (pintype "passive"))
      (node (ref "RPI-CM1") (pin "180") (pinfunction "GND_180") (pintype "passive"))
      (node (ref "RPI-CM1") (pin "185") (pinfunction "GND_185") (pintype "passive"))
      (node (ref "RPI-CM1") (pin "186") (pinfunction "GND_186") (pintype "passive"))
      (node (ref "RPI-CM1") (pin "191") (pinfunction "GND_191") (pintype "passive"))
      (node (ref "RPI-CM1") (pin "192") (pinfunction "GND_192") (pintype "passive"))
      (node (ref "RPI-CM1") (pin "197") (pinfunction "GND_197") (pintype "passive"))
      (node (ref "RPI-CM1") (pin "198") (pinfunction "GND_198") (pintype "passive"))
      (node (ref "RPI-CM1") (pin "2") (pinfunction "GND_2") (pintype "passive"))
      (node (ref "RPI-CM1") (pin "22") (pinfunction "GND_22") (pintype "passive"))
      (node (ref "RPI-CM1") (pin "23") (pinfunction "GND_23") (pintype "passive"))
      (node (ref "RPI-CM1") (pin "32") (pinfunction "GND_32") (pintype "passive"))
      (node (ref "RPI-CM1") (pin "33") (pinfunction "GND_33") (pintype "passive"))
      (node (ref "RPI-CM1") (pin "42") (pinfunction "GND_42") (pintype "passive"))
      (node (ref "RPI-CM1") (pin "43") (pinfunction "GND_43") (pintype "passive"))
      (node (ref "RPI-CM1") (pin "52") (pinfunction "GND_52") (pintype "passive"))
      (node (ref "RPI-CM1") (pin "53") (pinfunction "GND_53") (pintype "passive"))
      (node (ref "RPI-CM1") (pin "59") (pinfunction "GND_59") (pintype "passive"))
      (node (ref "RPI-CM1") (pin "60") (pinfunction "GND_60") (pintype "passive"))
      (node (ref "RPI-CM1") (pin "65") (pinfunction "GND_65") (pintype "passive"))
      (node (ref "RPI-CM1") (pin "66") (pinfunction "GND_66") (pintype "passive"))
      (node (ref "RPI-CM1") (pin "7") (pinfunction "GND_7") (pintype "passive"))
      (node (ref "RPI-CM1") (pin "71") (pinfunction "GND_71") (pintype "passive"))
      (node (ref "RPI-CM1") (pin "74") (pinfunction "GND_74") (pintype "passive"))
      (node (ref "RPI-CM1") (pin "8") (pinfunction "GND_8") (pintype "passive"))
      (node (ref "RPI-CM1") (pin "98") (pinfunction "GND_98") (pintype "passive"))
      (node (ref "U1") (pin "10") (pinfunction "/OE_10") (pintype "bidirectional"))
      (node (ref "U1") (pin "5") (pinfunction "GND_5") (pintype "bidirectional"))
      (node (ref "U2") (pin "3") (pinfunction "GND_3") (pintype "bidirectional"))
      (node (ref "U3") (pin "3") (pinfunction "GND_3") (pintype "bidirectional"))
      (node (ref "Y1") (pin "2") (pinfunction "GND_1_2") (pintype "bidirectional"))
      (node (ref "Y1") (pin "4") (pinfunction "GND_2_4") (pintype "bidirectional"))
    )
    (net (code "52") (name "GPIO2") (class "Default")
      (node (ref "JP2") (pin "3") (pinfunction "3_3") (pintype "passive"))
      (node (ref "RPI-CM1") (pin "58") (pinfunction "GPIO2_58") (pintype "passive"))
    )
    (net (code "53") (name "GPIO3") (class "Default")
      (node (ref "JP2") (pin "5") (pinfunction "5_5") (pintype "passive"))
      (node (ref "RPI-CM1") (pin "56") (pinfunction "GPIO3_56") (pintype "passive"))
    )
    (net (code "54") (name "GPIO4") (class "Default")
      (node (ref "JP2") (pin "7") (pinfunction "7_7") (pintype "passive"))
      (node (ref "RPI-CM1") (pin "54") (pinfunction "GPIO4_54") (pintype "passive"))
    )
    (net (code "55") (name "GPIO5") (class "Default")
      (node (ref "JP2") (pin "29") (pinfunction "29_29") (pintype "passive"))
      (node (ref "RPI-CM1") (pin "34") (pinfunction "GPIO5_34") (pintype "passive"))
    )
    (net (code "56") (name "GPIO6") (class "Default")
      (node (ref "JP2") (pin "31") (pinfunction "31_31") (pintype "passive"))
      (node (ref "RPI-CM1") (pin "30") (pinfunction "GPIO6_30") (pintype "passive"))
    )
    (net (code "57") (name "GPIO7") (class "Default")
      (node (ref "JP2") (pin "26") (pinfunction "26_26") (pintype "passive"))
      (node (ref "RPI-CM1") (pin "37") (pinfunction "GPIO7_37") (pintype "passive"))
    )
    (net (code "58") (name "GPIO8") (class "Default")
      (node (ref "JP2") (pin "24") (pinfunction "24_24") (pintype "passive"))
      (node (ref "RPI-CM1") (pin "39") (pinfunction "GPIO8_39") (pintype "passive"))
    )
    (net (code "59") (name "GPIO9") (class "Default")
      (node (ref "JP2") (pin "21") (pinfunction "21_21") (pintype "passive"))
      (node (ref "RPI-CM1") (pin "40") (pinfunction "GPIO9_40") (pintype "passive"))
    )
    (net (code "60") (name "GPIO10") (class "Default")
      (node (ref "JP2") (pin "19") (pinfunction "19_19") (pintype "passive"))
      (node (ref "RPI-CM1") (pin "44") (pinfunction "GPIO10_44") (pintype "passive"))
    )
    (net (code "61") (name "GPIO11") (class "Default")
      (node (ref "JP2") (pin "23") (pinfunction "23_23") (pintype "passive"))
      (node (ref "RPI-CM1") (pin "38") (pinfunction "GPIO11_38") (pintype "passive"))
    )
    (net (code "62") (name "GPIO12") (class "Default")
      (node (ref "JP2") (pin "32") (pinfunction "32_32") (pintype "passive"))
      (node (ref "RPI-CM1") (pin "31") (pinfunction "GPIO12_31") (pintype "passive"))
    )
    (net (code "63") (name "GPIO13") (class "Default")
      (node (ref "JP2") (pin "33") (pinfunction "33_33") (pintype "passive"))
      (node (ref "RPI-CM1") (pin "28") (pinfunction "GPIO13_28") (pintype "passive"))
    )
    (net (code "64") (name "GPIO14") (class "Default")
      (node (ref "JP2") (pin "8") (pinfunction "8_8") (pintype "passive"))
      (node (ref "RPI-CM1") (pin "55") (pinfunction "GPIO14_55") (pintype "passive"))
    )
    (net (code "65") (name "GPIO15") (class "Default")
      (node (ref "JP2") (pin "10") (pinfunction "10_10") (pintype "passive"))
      (node (ref "RPI-CM1") (pin "51") (pinfunction "GPIO15_51") (pintype "passive"))
    )
    (net (code "66") (name "GPIO16") (class "Default")
      (node (ref "JP2") (pin "36") (pinfunction "36_36") (pintype "passive"))
      (node (ref "RPI-CM1") (pin "29") (pinfunction "GPIO16_29") (pintype "passive"))
    )
    (net (code "67") (name "GPIO17") (class "Default")
      (node (ref "JP2") (pin "11") (pinfunction "11_11") (pintype "passive"))
      (node (ref "RPI-CM1") (pin "50") (pinfunction "GPIO17_50") (pintype "passive"))
    )
    (net (code "68") (name "GPIO18") (class "Default")
      (node (ref "JP2") (pin "12") (pinfunction "12_12") (pintype "passive"))
      (node (ref "RPI-CM1") (pin "49") (pinfunction "GPIO18_49") (pintype "passive"))
    )
    (net (code "69") (name "GPIO19") (class "Default")
      (node (ref "JP2") (pin "35") (pinfunction "35_35") (pintype "passive"))
      (node (ref "RPI-CM1") (pin "26") (pinfunction "GPIO19_26") (pintype "passive"))
    )
    (net (code "70") (name "GPIO20") (class "Default")
      (node (ref "JP2") (pin "38") (pinfunction "38_38") (pintype "passive"))
      (node (ref "RPI-CM1") (pin "27") (pinfunction "GPIO20_27") (pintype "passive"))
    )
    (net (code "71") (name "GPIO21") (class "Default")
      (node (ref "JP2") (pin "40") (pinfunction "40_40") (pintype "passive"))
      (node (ref "RPI-CM1") (pin "25") (pinfunction "GPIO21_25") (pintype "passive"))
    )
    (net (code "72") (name "GPIO22") (class "Default")
      (node (ref "JP2") (pin "15") (pinfunction "15_15") (pintype "passive"))
      (node (ref "RPI-CM1") (pin "46") (pinfunction "GPIO22_46") (pintype "passive"))
    )
    (net (code "73") (name "GPIO23") (class "Default")
      (node (ref "JP2") (pin "16") (pinfunction "16_16") (pintype "passive"))
      (node (ref "RPI-CM1") (pin "47") (pinfunction "GPIO23_47") (pintype "passive"))
    )
    (net (code "74") (name "GPIO24") (class "Default")
      (node (ref "JP2") (pin "18") (pinfunction "18_18") (pintype "passive"))
      (node (ref "RPI-CM1") (pin "45") (pinfunction "GPIO24_45") (pintype "passive"))
    )
    (net (code "75") (name "GPIO25") (class "Default")
      (node (ref "JP2") (pin "22") (pinfunction "22_22") (pintype "passive"))
      (node (ref "RPI-CM1") (pin "41") (pinfunction "GPIO25_41") (pintype "passive"))
    )
    (net (code "76") (name "GPIO26") (class "Default")
      (node (ref "JP2") (pin "37") (pinfunction "37_37") (pintype "passive"))
      (node (ref "RPI-CM1") (pin "24") (pinfunction "GPIO26_24") (pintype "passive"))
    )
    (net (code "77") (name "GPIO27") (class "Default")
      (node (ref "JP2") (pin "13") (pinfunction "13_13") (pintype "passive"))
      (node (ref "RPI-CM1") (pin "48") (pinfunction "GPIO27_48") (pintype "passive"))
    )
    (net (code "78") (name "GPIO_VREF") (class "Default")
      (node (ref "R15") (pin "2") (pinfunction "2_2") (pintype "passive"))
      (node (ref "R16") (pin "2") (pinfunction "2_2") (pintype "passive"))
      (node (ref "R21") (pin "2") (pinfunction "2_2") (pintype "passive"))
      (node (ref "R22") (pin "2") (pinfunction "2_2") (pintype "passive"))
      (node (ref "RPI-CM1") (pin "78") (pinfunction "GPIO_VREF_78") (pintype "passive"))
    )
    (net (code "79") (name "HDMI0_CEC") (class "Default")
      (node (ref "J6") (pin "13") (pinfunction "13_13") (pintype "bidirectional"))
      (node (ref "RPI-CM1") (pin "151") (pinfunction "HDMI0_CEC_151") (pintype "passive"))
    )
    (net (code "80") (name "HDMI0_CK_N") (class "Default")
      (node (ref "J6") (pin "12") (pinfunction "12_12") (pintype "bidirectional"))
    )
    (net (code "81") (name "HDMI0_CK_P") (class "Default")
      (node (ref "J6") (pin "10") (pinfunction "10_10") (pintype "bidirectional"))
    )
    (net (code "82") (name "HDMI0_CLK_N") (class "Default")
      (node (ref "RPI-CM1") (pin "190") (pinfunction "HDMI0_CLK_N_190") (pintype "passive"))
    )
    (net (code "83") (name "HDMI0_CLK_P") (class "Default")
      (node (ref "RPI-CM1") (pin "188") (pinfunction "HDMI0_CLK_P_188") (pintype "passive"))
    )
    (net (code "84") (name "HDMI0_D0_N") (class "Default")
      (node (ref "J6") (pin "9") (pinfunction "9_9") (pintype "bidirectional"))
    )
    (net (code "85") (name "HDMI0_D0_P") (class "Default")
      (node (ref "J6") (pin "7") (pinfunction "7_7") (pintype "bidirectional"))
    )
    (net (code "86") (name "HDMI0_D1_N") (class "Default")
      (node (ref "J6") (pin "6") (pinfunction "6_6") (pintype "bidirectional"))
    )
    (net (code "87") (name "HDMI0_D1_P") (class "Default")
      (node (ref "J6") (pin "4") (pinfunction "4_4") (pintype "bidirectional"))
    )
    (net (code "88") (name "HDMI0_D2_N") (class "Default")
      (node (ref "J6") (pin "3") (pinfunction "3_3") (pintype "bidirectional"))
    )
    (net (code "89") (name "HDMI0_D2_P") (class "Default")
      (node (ref "J6") (pin "1") (pinfunction "1_1") (pintype "bidirectional"))
    )
    (net (code "90") (name "HDMI0_HOTPLUG") (class "Default")
      (node (ref "J6") (pin "19") (pinfunction "19_19") (pintype "bidirectional"))
      (node (ref "RPI-CM1") (pin "153") (pinfunction "HDMI0_HOTPLUG_153") (pintype "passive"))
    )
    (net (code "91") (name "HDMI0_SCL") (class "Default")
      (node (ref "J6") (pin "15") (pinfunction "15_15") (pintype "bidirectional"))
    )
    (net (code "92") (name "HDMI0_SDA") (class "Default")
      (node (ref "J6") (pin "16") (pinfunction "16_16") (pintype "bidirectional"))
      (node (ref "RPI-CM1") (pin "199") (pinfunction "HDMI0_SDA_199") (pintype "passive"))
    )
    (net (code "93") (name "HDMI0_TX0_N") (class "Default")
      (node (ref "RPI-CM1") (pin "184") (pinfunction "HDMI0_TX0_N_184") (pintype "passive"))
    )
    (net (code "94") (name "HDMI0_TX0_P") (class "Default")
      (node (ref "RPI-CM1") (pin "182") (pinfunction "HDMI0_TX0_P_182") (pintype "passive"))
    )
    (net (code "95") (name "HDMI0_TX1_N") (class "Default")
      (node (ref "RPI-CM1") (pin "178") (pinfunction "HDMI0_TX1_N_178") (pintype "passive"))
    )
    (net (code "96") (name "HDMI0_TX1_P") (class "Default")
      (node (ref "RPI-CM1") (pin "176") (pinfunction "HDMI0_TX1_P_176") (pintype "passive"))
    )
    (net (code "97") (name "HDMI0_TX2_N") (class "Default")
      (node (ref "RPI-CM1") (pin "172") (pinfunction "HDMI0_TX2_N_172") (pintype "passive"))
    )
    (net (code "98") (name "HDMI0_TX2_P") (class "Default")
      (node (ref "RPI-CM1") (pin "170") (pinfunction "HDMI0_TX2_P_170") (pintype "passive"))
    )
    (net (code "99") (name "HDMI1_CEC") (class "Default")
      (node (ref "J8") (pin "13") (pinfunction "13_13") (pintype "bidirectional"))
      (node (ref "RPI-CM1") (pin "149") (pinfunction "HDMI1_CEC_149") (pintype "passive"))
    )
    (net (code "100") (name "HDMI1_CK_N") (class "Default")
      (node (ref "J8") (pin "12") (pinfunction "12_12") (pintype "bidirectional"))
    )
    (net (code "101") (name "HDMI1_CK_P") (class "Default")
      (node (ref "J8") (pin "10") (pinfunction "10_10") (pintype "bidirectional"))
    )
    (net (code "102") (name "HDMI1_CLK_N") (class "Default")
      (node (ref "RPI-CM1") (pin "166") (pinfunction "HDMI1_CLK_N_166") (pintype "passive"))
    )
    (net (code "103") (name "HDMI1_CLK_P") (class "Default")
      (node (ref "RPI-CM1") (pin "164") (pinfunction "HDMI1_CLK_P_164") (pintype "passive"))
    )
    (net (code "104") (name "HDMI1_D0_N") (class "Default")
      (node (ref "J8") (pin "9") (pinfunction "9_9") (pintype "bidirectional"))
    )
    (net (code "105") (name "HDMI1_D0_P") (class "Default")
      (node (ref "J8") (pin "7") (pinfunction "7_7") (pintype "bidirectional"))
    )
    (net (code "106") (name "HDMI1_D1_N") (class "Default")
      (node (ref "J8") (pin "6") (pinfunction "6_6") (pintype "bidirectional"))
    )
    (net (code "107") (name "HDMI1_D1_P") (class "Default")
      (node (ref "J8") (pin "4") (pinfunction "4_4") (pintype "bidirectional"))
    )
    (net (code "108") (name "HDMI1_D2_N") (class "Default")
      (node (ref "J8") (pin "3") (pinfunction "3_3") (pintype "bidirectional"))
    )
    (net (code "109") (name "HDMI1_D2_P") (class "Default")
      (node (ref "J8") (pin "1") (pinfunction "1_1") (pintype "bidirectional"))
    )
    (net (code "110") (name "HDMI1_HOTPLUG") (class "Default")
      (node (ref "J8") (pin "19") (pinfunction "19_19") (pintype "bidirectional"))
      (node (ref "RPI-CM1") (pin "143") (pinfunction "HDMI1_HOTPLUG_143") (pintype "passive"))
    )
    (net (code "111") (name "HDMI1_SCL") (class "Default")
      (node (ref "J8") (pin "15") (pinfunction "15_15") (pintype "bidirectional"))
    )
    (net (code "112") (name "HDMI1_SDA") (class "Default")
      (node (ref "J8") (pin "16") (pinfunction "16_16") (pintype "bidirectional"))
      (node (ref "RPI-CM1") (pin "145") (pinfunction "HDMI1_SDA_145") (pintype "passive"))
    )
    (net (code "113") (name "HDMI1_TX0_N") (class "Default")
      (node (ref "RPI-CM1") (pin "160") (pinfunction "HDMI1_TX0_N_160") (pintype "passive"))
    )
    (net (code "114") (name "HDMI1_TX0_P") (class "Default")
      (node (ref "RPI-CM1") (pin "158") (pinfunction "HDMI1_TX0_P_158") (pintype "passive"))
    )
    (net (code "115") (name "HDMI1_TX1_N") (class "Default")
      (node (ref "RPI-CM1") (pin "152") (pinfunction "HDMI1_TX1_P_152") (pintype "passive"))
    )
    (net (code "116") (name "HDMI1_TX1_P") (class "Default")
      (node (ref "RPI-CM1") (pin "154") (pinfunction "HDMI1_TX1_N_154") (pintype "passive"))
    )
    (net (code "117") (name "HDMI1_TX2_N") (class "Default")
      (node (ref "RPI-CM1") (pin "148") (pinfunction "HDMI1_TX2_N_148") (pintype "passive"))
    )
    (net (code "118") (name "HDMI1_TX2_P") (class "Default")
      (node (ref "RPI-CM1") (pin "146") (pinfunction "HDMI1_TX2_P_146") (pintype "passive"))
    )
    (net (code "119") (name "HDMI_5V") (class "Default")
      (node (ref "J6") (pin "18") (pinfunction "18_18") (pintype "bidirectional"))
      (node (ref "J8") (pin "18") (pinfunction "18_18") (pintype "bidirectional"))
    )
    (net (code "120") (name "HDMI_SCL") (class "Default")
      (node (ref "RPI-CM1") (pin "147") (pinfunction "HDMI1_SCL_147") (pintype "passive"))
    )
    (net (code "121") (name "HUB_DM") (class "Default")
      (node (ref "IC2") (pin "15") (pinfunction "UP_DM_15") (pintype "bidirectional"))
      (node (ref "U1") (pin "6") (pinfunction "HSD1-_6") (pintype "bidirectional"))
    )
    (net (code "122") (name "HUB_DP") (class "Default")
      (node (ref "IC2") (pin "16") (pinfunction "UP_DP_16") (pintype "bidirectional"))
      (node (ref "U1") (pin "7") (pinfunction "HSD1+_7") (pintype "power_in"))
    )
    (net (code "123") (name "ID_SC") (class "Default")
      (node (ref "JP2") (pin "28") (pinfunction "28_28") (pintype "passive"))
      (node (ref "JP4") (pin "1") (pinfunction "1_1") (pintype "passive"))
      (node (ref "RPI-CM1") (pin "35") (pinfunction "ID_SC_35") (pintype "passive"))
    )
    (net (code "124") (name "ID_SD") (class "Default")
      (node (ref "JP2") (pin "27") (pinfunction "27_27") (pintype "passive"))
      (node (ref "JP4") (pin "3") (pinfunction "3_3") (pintype "passive"))
      (node (ref "RPI-CM1") (pin "36") (pinfunction "ID_SD_36") (pintype "passive"))
    )
    (net (code "125") (name "NEXTRST") (class "Default")
      (node (ref "RPI-CM1") (pin "100") (pinfunction "~{EXTRST}_100") (pintype "passive"))
    )
    (net (code "126") (name "NPWR_LED") (class "Default")
      (node (ref "RPI-CM1") (pin "95") (pinfunction "PI_LED_~{PWR}_95") (pintype "passive"))
      (node (ref "U2") (pin "2") (pinfunction "A_2") (pintype "bidirectional"))
    )
    (net (code "127") (name "NRPIBOOT") (class "Default")
      (node (ref "JP7") (pin "2") (pinfunction "2_2") (pintype "passive"))
      (node (ref "RPI-CM1") (pin "93") (pinfunction "~{RPIBOOT}_93") (pintype "passive"))
    )
    (net (code "128") (name "Net-(C11-Pad1)") (class "Default")
      (node (ref "C11") (pin "1") (pinfunction "1_1") (pintype "passive"))
      (node (ref "R2") (pin "1") (pinfunction "1_1") (pintype "passive"))
    )
    (net (code "129") (name "Net-(C18-Pad1)") (class "Default")
      (node (ref "C18") (pin "1") (pinfunction "1_1") (pintype "passive"))
      (node (ref "R5") (pin "2") (pinfunction "2_2") (pintype "passive"))
    )
    (net (code "130") (name "Net-(C23-Pad1)") (class "Default")
      (node (ref "C23") (pin "1") (pinfunction "1_1") (pintype "passive"))
      (node (ref "J7") (pin "P4") (pinfunction "P4_P4") (pintype "bidirectional"))
      (node (ref "J7") (pin "P5") (pinfunction "P5_P5") (pintype "bidirectional"))
    )
    (net (code "131") (name "Net-(C31-Pad1)") (class "Default")
      (node (ref "C31") (pin "1") (pinfunction "1_1") (pintype "passive"))
      (node (ref "R23") (pin "1") (pinfunction "1_1") (pintype "passive"))
    )
    (net (code "132") (name "Net-(C38-Pad1)") (class "Default")
      (node (ref "C38") (pin "1") (pinfunction "1_1") (pintype "passive"))
      (node (ref "R26") (pin "2") (pinfunction "2_2") (pintype "passive"))
    )
    (net (code "133") (name "Net-(IC1-BST)") (class "Default")
      (node (ref "C11") (pin "2") (pinfunction "2_2") (pintype "passive"))
      (node (ref "IC1") (pin "1") (pinfunction "BST_1") (pintype "bidirectional"))
    )
    (net (code "134") (name "Net-(IC1-COMP)") (class "Default")
      (node (ref "C19") (pin "1") (pinfunction "1_1") (pintype "passive"))
      (node (ref "IC1") (pin "6") (pinfunction "COMP_6") (pintype "bidirectional"))
      (node (ref "R5") (pin "1") (pinfunction "1_1") (pintype "passive"))
    )
    (net (code "135") (name "Net-(IC1-FB)") (class "Default")
      (node (ref "C17") (pin "2") (pinfunction "2_2") (pintype "passive"))
      (node (ref "IC1") (pin "5") (pinfunction "FB_5") (pintype "bidirectional"))
      (node (ref "R3") (pin "1") (pinfunction "1_1") (pintype "passive"))
      (node (ref "R4") (pin "2") (pinfunction "2_2") (pintype "passive"))
    )
    (net (code "136") (name "Net-(IC1-SS)") (class "Default")
      (node (ref "C10") (pin "1") (pinfunction "1_1") (pintype "passive"))
      (node (ref "IC1") (pin "4") (pinfunction "SS_4") (pintype "bidirectional"))
    )
    (net (code "137") (name "Net-(IC1-SW)") (class "Default")
      (node (ref "IC1") (pin "8") (pinfunction "SW_8") (pintype "bidirectional"))
      (node (ref "L1") (pin "1") (pinfunction "1_1") (pintype "bidirectional"))
      (node (ref "R2") (pin "2") (pinfunction "2_2") (pintype "passive"))
    )
    (net (code "138") (name "Net-(IC2-LED_CTL{slash}CHRGEN)") (class "Default")
      (node (ref "IC2") (pin "22") (pinfunction "LED_CTL/CHRGEN_22") (pintype "bidirectional"))
      (node (ref "R13") (pin "2") (pinfunction "2_2") (pintype "passive"))
    )
    (net (code "139") (name "Net-(IC2-REXT)") (class "Default")
      (node (ref "IC2") (pin "14") (pinfunction "REXT_14") (pintype "bidirectional"))
      (node (ref "R12") (pin "2") (pinfunction "2_2") (pintype "passive"))
    )
    (net (code "140") (name "Net-(IC3-PWM)") (class "Default")
      (node (ref "IC3") (pin "5") (pinfunction "PWM_5") (pintype "bidirectional"))
      (node (ref "JP1") (pin "4") (pinfunction "4_4") (pintype "passive"))
    )
    (net (code "141") (name "Net-(IC3-TACH)") (class "Default")
      (node (ref "IC3") (pin "6") (pinfunction "TACH_6") (pintype "bidirectional"))
      (node (ref "JP1") (pin "3") (pinfunction "3_3") (pintype "passive"))
      (node (ref "R14") (pin "1") (pinfunction "1_1") (pintype "passive"))
    )
    (net (code "142") (name "Net-(IC6-BST)") (class "Default")
      (node (ref "C31") (pin "2") (pinfunction "2_2") (pintype "passive"))
      (node (ref "IC6") (pin "1") (pinfunction "BST_1") (pintype "bidirectional"))
    )
    (net (code "143") (name "Net-(IC6-COMP)") (class "Default")
      (node (ref "C39") (pin "1") (pinfunction "1_1") (pintype "passive"))
      (node (ref "IC6") (pin "6") (pinfunction "COMP_6") (pintype "bidirectional"))
      (node (ref "R26") (pin "1") (pinfunction "1_1") (pintype "passive"))
    )
    (net (code "144") (name "Net-(IC6-FB)") (class "Default")
      (node (ref "C37") (pin "2") (pinfunction "2_2") (pintype "passive"))
      (node (ref "IC6") (pin "5") (pinfunction "FB_5") (pintype "bidirectional"))
      (node (ref "R24") (pin "1") (pinfunction "1_1") (pintype "passive"))
      (node (ref "R25") (pin "2") (pinfunction "2_2") (pintype "passive"))
    )
    (net (code "145") (name "Net-(IC6-SS)") (class "Default")
      (node (ref "C30") (pin "1") (pinfunction "1_1") (pintype "passive"))
      (node (ref "IC6") (pin "4") (pinfunction "SS_4") (pintype "bidirectional"))
    )
    (net (code "146") (name "Net-(IC6-SW)") (class "Default")
      (node (ref "IC6") (pin "8") (pinfunction "SW_8") (pintype "bidirectional"))
      (node (ref "L2") (pin "1") (pinfunction "1_1") (pintype "bidirectional"))
      (node (ref "R23") (pin "2") (pinfunction "2_2") (pintype "passive"))
    )
    (net (code "147") (name "Net-(J5-DETECT_LEVER)") (class "Default")
      (node (ref "J5") (pin "9") (pinfunction "DETECT_LEVER_9") (pintype "bidirectional"))
      (node (ref "R17") (pin "2") (pinfunction "2_2") (pintype "passive"))
    )
    (net (code "148") (name "Net-(J5-DETECT_SWITCH)") (class "Default")
      (node (ref "J5") (pin "10") (pinfunction "DETECT_SWITCH_10") (pintype "bidirectional"))
      (node (ref "R18") (pin "2") (pinfunction "2_2") (pintype "passive"))
    )
    (net (code "149") (name "Net-(J7-CATHODE_GREEN)") (class "Default")
      (node (ref "J7") (pin "P16") (pinfunction "CATHODE_GREEN_P16") (pintype "bidirectional"))
      (node (ref "R20") (pin "1") (pinfunction "1_1") (pintype "passive"))
    )
    (net (code "150") (name "Net-(J7-CATHODE_YELLOW)") (class "Default")
      (node (ref "J7") (pin "P18") (pinfunction "CATHODE_YELLOW_P18") (pintype "bidirectional"))
      (node (ref "R19") (pin "1") (pinfunction "1_1") (pintype "passive"))
    )
    (net (code "151") (name "Net-(LED1-PadC)") (class "Default")
      (node (ref "LED1") (pin "C") (pinfunction "C_C") (pintype "passive"))
      (node (ref "R27") (pin "2") (pinfunction "2_2") (pintype "passive"))
    )
    (net (code "152") (name "Net-(LED2-PadC)") (class "Default")
      (node (ref "LED2") (pin "C") (pinfunction "C_C") (pintype "passive"))
      (node (ref "R28") (pin "1") (pinfunction "1_1") (pintype "passive"))
    )
    (net (code "153") (name "Net-(Q1-G)") (class "Default")
      (node (ref "C2") (pin "1") (pinfunction "1_1") (pintype "passive"))
      (node (ref "Q1") (pin "4") (pinfunction "G_4") (pintype "bidirectional"))
      (node (ref "R1") (pin "2") (pinfunction "2_2") (pintype "passive"))
      (node (ref "Z1") (pin "1") (pinfunction "A_1") (pintype "bidirectional"))
    )
    (net (code "154") (name "Net-(RPI-CM1A-PI_~{LED_ACTIVITY})") (class "Default")
      (node (ref "R27") (pin "1") (pinfunction "1_1") (pintype "passive"))
      (node (ref "RPI-CM1") (pin "21") (pinfunction "PI_~{LED_ACTIVITY}_21") (pintype "passive"))
    )
    (net (code "155") (name "Net-(U2-Y)") (class "Default")
      (node (ref "R28") (pin "2") (pinfunction "2_2") (pintype "passive"))
      (node (ref "U2") (pin "4") (pinfunction "Y_4") (pintype "bidirectional"))
    )
    (net (code "156") (name "Net-(U3-Y)") (class "Default")
      (node (ref "JP7") (pin "13") (pinfunction "13_13") (pintype "passive"))
      (node (ref "U3") (pin "4") (pinfunction "Y_4") (pintype "bidirectional"))
    )
    (net (code "157") (name "PCIE1_CLK_NREQ") (class "Default")
      (node (ref "J13") (pin "53") (pinfunction "53_53") (pintype "passive"))
    )
    (net (code "158") (name "PCIE1_PCIE_CLK") (class "Default")
      (node (ref "J13") (pin "49") (pinfunction "49_49") (pintype "passive"))
    )
    (net (code "159") (name "PCIE1_PCIE_CLK+") (class "Default")
      (node (ref "J13") (pin "47") (pinfunction "47_47") (pintype "passive"))
    )
    (net (code "160") (name "PCIE1_PCIE_NRST") (class "Default")
      (node (ref "J13") (pin "52") (pinfunction "52_52") (pintype "passive"))
    )
    (net (code "161") (name "PCIE1_PCIE_RX") (class "Default")
      (node (ref "J13") (pin "43") (pinfunction "43_43") (pintype "passive"))
    )
    (net (code "162") (name "PCIE1_PCIE_RX+") (class "Default")
      (node (ref "J13") (pin "41") (pinfunction "41_41") (pintype "passive"))
    )
    (net (code "163") (name "PCIE1_PCIE_TX") (class "Default")
      (node (ref "J13") (pin "37") (pinfunction "37_37") (pintype "passive"))
    )
    (net (code "164") (name "PCIE1_PCIE_TX+") (class "Default")
      (node (ref "J13") (pin "35") (pinfunction "35_35") (pintype "passive"))
    )
    (net (code "165") (name "PCIE1_PCIE_WAKE#") (class "Default")
      (node (ref "J13") (pin "55") (pinfunction "55_55") (pintype "passive"))
    )
    (net (code "166") (name "PCIE2_CLK_NREQ") (class "Default")
      (node (ref "J14") (pin "53") (pinfunction "53_53") (pintype "passive"))
    )
    (net (code "167") (name "PCIE2_PCIE_CLK") (class "Default")
      (node (ref "J14") (pin "49") (pinfunction "49_49") (pintype "passive"))
    )
    (net (code "168") (name "PCIE2_PCIE_CLK+") (class "Default")
      (node (ref "J14") (pin "47") (pinfunction "47_47") (pintype "passive"))
    )
    (net (code "169") (name "PCIE2_PCIE_NRST") (class "Default")
      (node (ref "J14") (pin "52") (pinfunction "52_52") (pintype "passive"))
    )
    (net (code "170") (name "PCIE2_PCIE_RX") (class "Default")
      (node (ref "J14") (pin "43") (pinfunction "43_43") (pintype "passive"))
    )
    (net (code "171") (name "PCIE2_PCIE_RX+") (class "Default")
      (node (ref "J14") (pin "41") (pinfunction "41_41") (pintype "passive"))
    )
    (net (code "172") (name "PCIE2_PCIE_TX") (class "Default")
      (node (ref "J14") (pin "37") (pinfunction "37_37") (pintype "passive"))
    )
    (net (code "173") (name "PCIE2_PCIE_TX+") (class "Default")
      (node (ref "J14") (pin "35") (pinfunction "35_35") (pintype "passive"))
    )
    (net (code "174") (name "PCIE2_PCIE_WAKE#") (class "Default")
      (node (ref "J14") (pin "55") (pinfunction "55_55") (pintype "passive"))
    )
    (net (code "175") (name "PCIE3_CLK_NREQ") (class "Default")
      (node (ref "J15") (pin "53") (pinfunction "53_53") (pintype "passive"))
    )
    (net (code "176") (name "PCIE3_PCIE_CLK") (class "Default")
      (node (ref "J15") (pin "49") (pinfunction "49_49") (pintype "passive"))
    )
    (net (code "177") (name "PCIE3_PCIE_CLK+") (class "Default")
      (node (ref "J15") (pin "47") (pinfunction "47_47") (pintype "passive"))
    )
    (net (code "178") (name "PCIE3_PCIE_NRST") (class "Default")
      (node (ref "J15") (pin "52") (pinfunction "52_52") (pintype "passive"))
    )
    (net (code "179") (name "PCIE3_PCIE_RX") (class "Default")
      (node (ref "J15") (pin "43") (pinfunction "43_43") (pintype "passive"))
    )
    (net (code "180") (name "PCIE3_PCIE_RX+") (class "Default")
      (node (ref "J15") (pin "41") (pinfunction "41_41") (pintype "passive"))
    )
    (net (code "181") (name "PCIE3_PCIE_TX") (class "Default")
      (node (ref "J15") (pin "37") (pinfunction "37_37") (pintype "passive"))
    )
    (net (code "182") (name "PCIE3_PCIE_TX+") (class "Default")
      (node (ref "J15") (pin "35") (pinfunction "35_35") (pintype "passive"))
    )
    (net (code "183") (name "PCIE3_PCIE_WAKE#") (class "Default")
      (node (ref "J15") (pin "55") (pinfunction "55_55") (pintype "passive"))
    )
    (net (code "184") (name "PCIE4_CLK_NREQ") (class "Default")
      (node (ref "J16") (pin "53") (pinfunction "53_53") (pintype "passive"))
    )
    (net (code "185") (name "PCIE4_PCIE_CLK") (class "Default")
      (node (ref "J16") (pin "49") (pinfunction "49_49") (pintype "passive"))
    )
    (net (code "186") (name "PCIE4_PCIE_CLK+") (class "Default")
      (node (ref "J16") (pin "47") (pinfunction "47_47") (pintype "passive"))
    )
    (net (code "187") (name "PCIE4_PCIE_NRST") (class "Default")
      (node (ref "J16") (pin "52") (pinfunction "52_52") (pintype "passive"))
    )
    (net (code "188") (name "PCIE4_PCIE_RX") (class "Default")
      (node (ref "J16") (pin "43") (pinfunction "43_43") (pintype "passive"))
    )
    (net (code "189") (name "PCIE4_PCIE_RX+") (class "Default")
      (node (ref "J16") (pin "41") (pinfunction "41_41") (pintype "passive"))
    )
    (net (code "190") (name "PCIE4_PCIE_TX") (class "Default")
      (node (ref "J16") (pin "37") (pinfunction "37_37") (pintype "passive"))
    )
    (net (code "191") (name "PCIE4_PCIE_TX+") (class "Default")
      (node (ref "J16") (pin "35") (pinfunction "35_35") (pintype "passive"))
    )
    (net (code "192") (name "PCIE4_PCIE_WAKE#") (class "Default")
      (node (ref "J16") (pin "55") (pinfunction "55_55") (pintype "passive"))
    )
    (net (code "193") (name "PCIE_CLK_N") (class "Default")
      (node (ref "RPI-CM1") (pin "112") (pinfunction "PCIE_CLK_N_112") (pintype "passive"))
    )
    (net (code "194") (name "PCIE_CLK_NREQ") (class "Default")
      (node (ref "RPI-CM1") (pin "102") (pinfunction "PCIE_CLK_~{REQ}_102") (pintype "passive"))
    )
    (net (code "195") (name "PCIE_CLK_P") (class "Default")
      (node (ref "RPI-CM1") (pin "110") (pinfunction "PCIE_CLK_P_110") (pintype "passive"))
    )
    (net (code "196") (name "PCIE_NRST") (class "Default")
      (node (ref "RPI-CM1") (pin "109") (pinfunction "PCIE_~{RST}_109") (pintype "passive"))
    )
    (net (code "197") (name "PCIE_RX_N") (class "Default")
      (node (ref "RPI-CM1") (pin "118") (pinfunction "PCIE_RX_N_118") (pintype "passive"))
    )
    (net (code "198") (name "PCIE_RX_P") (class "Default")
      (node (ref "RPI-CM1") (pin "116") (pinfunction "PCIE_RX_P_116") (pintype "passive"))
    )
    (net (code "199") (name "PCIE_TX_N") (class "Default")
      (node (ref "RPI-CM1") (pin "124") (pinfunction "PCIE_TX_N_124") (pintype "passive"))
    )
    (net (code "200") (name "PCIE_TX_P") (class "Default")
      (node (ref "RPI-CM1") (pin "122") (pinfunction "PCIE_TX_P_122") (pintype "passive"))
    )
    (net (code "201") (name "RESERVED") (class "Default")
      (node (ref "R17") (pin "1") (pinfunction "1_1") (pintype "passive"))
      (node (ref "RPI-CM1") (pin "76") (pinfunction "RESERVED_76") (pintype "passive"))
    )
    (net (code "202") (name "RUN_PG") (class "Default")
      (node (ref "JP6") (pin "3") (pinfunction "3_3") (pintype "passive"))
      (node (ref "RPI-CM1") (pin "92") (pinfunction "RUN_PG_92") (pintype "passive"))
      (node (ref "U3") (pin "2") (pinfunction "A_2") (pintype "bidirectional"))
    )
    (net (code "203") (name "SCL") (class "Default")
      (node (ref "IC3") (pin "2") (pinfunction "SMCLK_2") (pintype "bidirectional"))
    )
    (net (code "204") (name "SCL0") (class "Default")
      (node (ref "J10") (pin "20") (pinfunction "20_20") (pintype "bidirectional"))
      (node (ref "J12") (pin "20") (pinfunction "20_20") (pintype "bidirectional"))
      (node (ref "RPI-CM1") (pin "80") (pinfunction "SCL0_80") (pintype "passive"))
    )
    (net (code "205") (name "SCL1") (class "Default")
      (node (ref "J11") (pin "20") (pinfunction "20_20") (pintype "bidirectional"))
      (node (ref "J9") (pin "20") (pinfunction "20_20") (pintype "bidirectional"))
      (node (ref "JP4") (pin "2") (pinfunction "2_2") (pintype "passive"))
      (node (ref "R21") (pin "1") (pinfunction "1_1") (pintype "passive"))
    )
    (net (code "206") (name "SDA") (class "Default")
      (node (ref "IC3") (pin "1") (pinfunction "SMDATA_1") (pintype "bidirectional"))
    )
    (net (code "207") (name "SDA0") (class "Default")
      (node (ref "J10") (pin "21") (pinfunction "21_21") (pintype "bidirectional"))
      (node (ref "J12") (pin "21") (pinfunction "21_21") (pintype "bidirectional"))
      (node (ref "RPI-CM1") (pin "82") (pinfunction "SDA0_82") (pintype "passive"))
    )
    (net (code "208") (name "SDA1") (class "Default")
      (node (ref "J11") (pin "21") (pinfunction "21_21") (pintype "bidirectional"))
      (node (ref "J9") (pin "21") (pinfunction "21_21") (pintype "bidirectional"))
      (node (ref "JP4") (pin "4") (pinfunction "4_4") (pintype "passive"))
      (node (ref "R22") (pin "1") (pinfunction "1_1") (pintype "passive"))
    )
    (net (code "209") (name "SD_CLK") (class "Default")
      (node (ref "J5") (pin "5") (pinfunction "CLK_5") (pintype "bidirectional"))
      (node (ref "RPI-CM1") (pin "57") (pinfunction "SD_CLK_57") (pintype "passive"))
    )
    (net (code "210") (name "SD_CMD") (class "Default")
      (node (ref "J5") (pin "3") (pinfunction "CMD_3") (pintype "bidirectional"))
      (node (ref "RPI-CM1") (pin "62") (pinfunction "SD_CMD_62") (pintype "passive"))
    )
    (net (code "211") (name "SD_DAT0") (class "Default")
      (node (ref "J5") (pin "7") (pinfunction "DAT0_7") (pintype "bidirectional"))
    )
    (net (code "212") (name "SD_DAT1") (class "Default")
      (node (ref "J5") (pin "8") (pinfunction "DAT1_8") (pintype "bidirectional"))
    )
    (net (code "213") (name "SD_DAT2") (class "Default")
      (node (ref "J5") (pin "1") (pinfunction "DAT2_1") (pintype "bidirectional"))
    )
    (net (code "214") (name "SD_DAT3") (class "Default")
      (node (ref "J5") (pin "2") (pinfunction "CD/DAT3_2") (pintype "bidirectional"))
    )
    (net (code "215") (name "SD_DATA0") (class "Default")
      (node (ref "RPI-CM1") (pin "63") (pinfunction "SD_DAT0_63") (pintype "passive"))
    )
    (net (code "216") (name "SD_DATA1") (class "Default")
      (node (ref "RPI-CM1") (pin "67") (pinfunction "SD_DAT1_67") (pintype "passive"))
    )
    (net (code "217") (name "SD_DATA2") (class "Default")
      (node (ref "RPI-CM1") (pin "69") (pinfunction "SD_DAT2_69") (pintype "passive"))
    )
    (net (code "218") (name "SD_DATA3") (class "Default")
      (node (ref "RPI-CM1") (pin "61") (pinfunction "SD_DAT3_61") (pintype "passive"))
    )
    (net (code "219") (name "SD_PWR") (class "Default")
      (node (ref "C22") (pin "1") (pinfunction "1_1") (pintype "passive"))
    )
    (net (code "220") (name "SD_PWR_ON") (class "Default")
      (node (ref "RPI-CM1") (pin "75") (pinfunction "SD_PWR_ON_75") (pintype "passive"))
    )
    (net (code "221") (name "SYNC_IN") (class "Default")
      (node (ref "JP7") (pin "8") (pinfunction "8_8") (pintype "passive"))
      (node (ref "RPI-CM1") (pin "16") (pinfunction "ETH_SYNC_IN_16") (pintype "passive"))
    )
    (net (code "222") (name "SYNC_OUT") (class "Default")
      (node (ref "JP7") (pin "9") (pinfunction "9_9") (pintype "passive"))
      (node (ref "RPI-CM1") (pin "18") (pinfunction "ETH_SYNC_OUT_18") (pintype "passive"))
    )
    (net (code "223") (name "TR0_TAP") (class "Default")
      (node (ref "J7") (pin "P11") (pinfunction "VC1_P11") (pintype "bidirectional"))
      (node (ref "JP3") (pin "3") (pinfunction "3_3") (pintype "passive"))
    )
    (net (code "224") (name "TR1_TAP") (class "Default")
      (node (ref "J7") (pin "P12") (pinfunction "VC2_P12") (pintype "bidirectional"))
      (node (ref "JP3") (pin "1") (pinfunction "1_1") (pintype "passive"))
    )
    (net (code "225") (name "TR2_TAP") (class "Default")
      (node (ref "J7") (pin "P13") (pinfunction "VC3_P13") (pintype "bidirectional"))
      (node (ref "JP3") (pin "2") (pinfunction "2_2") (pintype "passive"))
    )
    (net (code "226") (name "TR3_TAP") (class "Default")
      (node (ref "J7") (pin "P14") (pinfunction "VC4_P14") (pintype "bidirectional"))
      (node (ref "JP3") (pin "4") (pinfunction "4_4") (pintype "passive"))
    )
    (net (code "227") (name "TRD0_N") (class "Default")
      (node (ref "IC5") (pin "4") (pinfunction "D2+_4") (pintype "bidirectional"))
      (node (ref "J7") (pin "P2") (pinfunction "P2_P2") (pintype "bidirectional"))
      (node (ref "RPI-CM1") (pin "10") (pinfunction "ETH_PAIR0_N_10") (pintype "passive"))
    )
    (net (code "228") (name "TRD0_P") (class "Default")
      (node (ref "IC5") (pin "5") (pinfunction "D2-_5") (pintype "bidirectional"))
      (node (ref "J7") (pin "P1") (pinfunction "P1_P1") (pintype "bidirectional"))
      (node (ref "RPI-CM1") (pin "12") (pinfunction "ETH_PAIR0_P_12") (pintype "passive"))
    )
    (net (code "229") (name "TRD1_N") (class "Default")
      (node (ref "IC5") (pin "2") (pinfunction "D1-_2") (pintype "bidirectional"))
      (node (ref "J7") (pin "P6") (pinfunction "P6_P6") (pintype "bidirectional"))
      (node (ref "RPI-CM1") (pin "6") (pinfunction "ETH_PAIR1_N_6") (pintype "passive"))
    )
    (net (code "230") (name "TRD1_P") (class "Default")
      (node (ref "IC5") (pin "1") (pinfunction "D1+_1") (pintype "bidirectional"))
      (node (ref "J7") (pin "P3") (pinfunction "P3_P3") (pintype "bidirectional"))
      (node (ref "RPI-CM1") (pin "4") (pinfunction "ETH_PAIR1_P_4") (pintype "passive"))
    )
    (net (code "231") (name "TRD2_N") (class "Default")
      (node (ref "IC4") (pin "4") (pinfunction "D2+_4") (pintype "bidirectional"))
      (node (ref "J7") (pin "P8") (pinfunction "P8_P8") (pintype "bidirectional"))
      (node (ref "RPI-CM1") (pin "9") (pinfunction "ETH_PAIR2_N_9") (pintype "passive"))
    )
    (net (code "232") (name "TRD2_P") (class "Default")
      (node (ref "IC4") (pin "5") (pinfunction "D2-_5") (pintype "bidirectional"))
      (node (ref "J7") (pin "P7") (pinfunction "P7_P7") (pintype "bidirectional"))
      (node (ref "RPI-CM1") (pin "11") (pinfunction "ETH_PAIR2_P_11") (pintype "passive"))
    )
    (net (code "233") (name "TRD3_N") (class "Default")
      (node (ref "IC4") (pin "2") (pinfunction "D1-_2") (pintype "bidirectional"))
      (node (ref "J7") (pin "P10") (pinfunction "P10_P10") (pintype "bidirectional"))
      (node (ref "RPI-CM1") (pin "5") (pinfunction "ETH_PAIR3_N_5") (pintype "passive"))
    )
    (net (code "234") (name "TRD3_P") (class "Default")
      (node (ref "IC4") (pin "1") (pinfunction "D1+_1") (pintype "bidirectional"))
      (node (ref "J7") (pin "P9") (pinfunction "P9_P9") (pintype "bidirectional"))
      (node (ref "RPI-CM1") (pin "3") (pinfunction "ETH_PAIR3_P_3") (pintype "passive"))
    )
    (net (code "235") (name "TV_OUT") (class "Default")
      (node (ref "JP7") (pin "11") (pinfunction "11_11") (pintype "passive"))
      (node (ref "RPI-CM1") (pin "111") (pinfunction "VDAC_COMP_111") (pintype "passive"))
    )
    (net (code "236") (name "UBSOTG_ID") (class "Default")
      (node (ref "RPI-CM1") (pin "101") (pinfunction "USB_OTG_ID_101") (pintype "passive"))
    )
    (net (code "237") (name "USB2_N") (class "Default")
      (node (ref "RPI-CM1") (pin "103") (pinfunction "USB_N_103") (pintype "passive"))
      (node (ref "U1") (pin "4") (pinfunction "D-_4") (pintype "bidirectional"))
    )
    (net (code "238") (name "USB2_P") (class "Default")
      (node (ref "RPI-CM1") (pin "105") (pinfunction "USB_P_105") (pintype "passive"))
      (node (ref "U1") (pin "3") (pinfunction "D+_3") (pintype "bidirectional"))
    )
    (net (code "239") (name "USB_+5V") (class "Default")
      (node (ref "J3") (pin "1") (pinfunction "1_1") (pintype "passive"))
      (node (ref "J3") (pin "5") (pinfunction "5_5") (pintype "passive"))
      (node (ref "J4") (pin "1") (pinfunction "1_1") (pintype "passive"))
      (node (ref "J4") (pin "5") (pinfunction "5_5") (pintype "passive"))
    )
    (net (code "240") (name "USB_1_DM") (class "Default")
      (node (ref "IC2") (pin "10") (pinfunction "DM1_10") (pintype "bidirectional"))
      (node (ref "J3") (pin "2") (pinfunction "2_2") (pintype "passive"))
    )
    (net (code "241") (name "USB_1_DP") (class "Default")
      (node (ref "IC2") (pin "11") (pinfunction "DP1_11") (pintype "bidirectional"))
      (node (ref "J3") (pin "3") (pinfunction "3_3") (pintype "passive"))
    )
    (net (code "242") (name "USB_2_DM") (class "Default")
      (node (ref "IC2") (pin "8") (pinfunction "DM2_8") (pintype "bidirectional"))
      (node (ref "J3") (pin "6") (pinfunction "6_6") (pintype "passive"))
    )
    (net (code "243") (name "USB_2_DP") (class "Default")
      (node (ref "IC2") (pin "9") (pinfunction "DP2_9") (pintype "bidirectional"))
      (node (ref "J3") (pin "7") (pinfunction "7_7") (pintype "passive"))
    )
    (net (code "244") (name "USB_3_DM") (class "Default")
      (node (ref "IC2") (pin "6") (pinfunction "DM3_6") (pintype "bidirectional"))
      (node (ref "J4") (pin "2") (pinfunction "2_2") (pintype "passive"))
    )
    (net (code "245") (name "USB_3_DP") (class "Default")
      (node (ref "IC2") (pin "7") (pinfunction "DP3_7") (pintype "bidirectional"))
      (node (ref "J4") (pin "3") (pinfunction "3_3") (pintype "passive"))
    )
    (net (code "246") (name "USB_4_DM") (class "Default")
      (node (ref "IC2") (pin "4") (pinfunction "DM4_4") (pintype "bidirectional"))
      (node (ref "J4") (pin "6") (pinfunction "6_6") (pintype "passive"))
    )
    (net (code "247") (name "USB_4_DP") (class "Default")
      (node (ref "IC2") (pin "5") (pinfunction "DP4_5") (pintype "bidirectional"))
      (node (ref "J4") (pin "7") (pinfunction "7_7") (pintype "passive"))
    )
    (net (code "248") (name "USB_C_DM") (class "Default")
      (node (ref "J2") (pin "A7") (pinfunction "DN1_A7") (pintype "bidirectional"))
      (node (ref "J2") (pin "B7") (pinfunction "DN2_B7") (pintype "bidirectional"))
      (node (ref "U1") (pin "8") (pinfunction "HSD2-_8") (pintype "bidirectional"))
    )
    (net (code "249") (name "USB_C_DP") (class "Default")
      (node (ref "J2") (pin "A6") (pinfunction "DP1_A6") (pintype "bidirectional"))
      (node (ref "J2") (pin "B6") (pinfunction "DP2_B6") (pintype "bidirectional"))
      (node (ref "U1") (pin "9") (pinfunction "HSD2+_9") (pintype "bidirectional"))
    )
    (net (code "250") (name "USB_C_VBUS") (class "Default")
      (node (ref "J2") (pin "A4") (pinfunction "V_BUS_1_A4") (pintype "bidirectional"))
      (node (ref "J2") (pin "B4") (pinfunction "VBUS_1_B4") (pintype "bidirectional"))
      (node (ref "R7") (pin "2") (pinfunction "2_2") (pintype "passive"))
    )
    (net (code "251") (name "USB_OTG") (class "Default")
      (node (ref "R6") (pin "2") (pinfunction "2_2") (pintype "passive"))
      (node (ref "R7") (pin "1") (pinfunction "1_1") (pintype "passive"))
      (node (ref "U1") (pin "2") (pinfunction "SEL_2") (pintype "bidirectional"))
    )
    (net (code "252") (name "VAUX33_REF") (class "Default")
      (node (ref "U4") (pin "E1") (pinfunction "VAUX33_REF_E1") (pintype "power_in"))
    )
    (net (code "253") (name "VBUS_SENSE") (class "Default")
      (node (ref "C20") (pin "1") (pinfunction "1_1") (pintype "passive"))
      (node (ref "IC2") (pin "18") (pinfunction "VBUS_SENSE_18") (pintype "bidirectional"))
      (node (ref "R10") (pin "2") (pinfunction "2_2") (pintype "passive"))
      (node (ref "R11") (pin "2") (pinfunction "2_2") (pintype "passive"))
    )
    (net (code "254") (name "VDD15") (class "Default")
      (node (ref "U4") (pin "K4") (pinfunction "VDD15_K4") (pintype "power_in"))
    )
    (net (code "255") (name "VDD15_2") (class "Default")
      (node (ref "U4") (pin "A4") (pinfunction "VDD15_2_A4") (pintype "power_in"))
    )
    (net (code "256") (name "VDD15_3") (class "Default")
      (node (ref "U4") (pin "B2") (pinfunction "VDD15_3_B2") (pintype "power_in"))
    )
    (net (code "257") (name "VDD15_4") (class "Default")
      (node (ref "U4") (pin "B3") (pinfunction "VDD15_4_B3") (pintype "power_in"))
    )
    (net (code "258") (name "VDD15_5") (class "Default")
      (node (ref "U4") (pin "B7") (pinfunction "VDD15_5_B7") (pintype "power_in"))
    )
    (net (code "259") (name "VDD15_6") (class "Default")
      (node (ref "U4") (pin "C5") (pinfunction "VDD15_6_C5") (pintype "power_in"))
    )
    (net (code "260") (name "VDD15_7") (class "Default")
      (node (ref "U4") (pin "F1") (pinfunction "VDD15_7_F1") (pintype "power_in"))
    )
    (net (code "261") (name "VDD15_8") (class "Default")
      (node (ref "U4") (pin "F2") (pinfunction "VDD15_8_F2") (pintype "power_in"))
    )
    (net (code "262") (name "VDD15_9") (class "Default")
      (node (ref "U4") (pin "H3") (pinfunction "VDD15_9_H3") (pintype "power_in"))
    )
    (net (code "263") (name "VDD15_REF") (class "Default")
      (node (ref "U4") (pin "F3") (pinfunction "VDD15_REF_F3") (pintype "power_in"))
    )
    (net (code "264") (name "VDD33") (class "Default")
      (node (ref "U4") (pin "B4") (pinfunction "VDD33_B4") (pintype "power_in"))
    )
    (net (code "265") (name "VDD33_2") (class "Default")
      (node (ref "U4") (pin "A3") (pinfunction "VDD33_2_A3") (pintype "power_in"))
    )
    (net (code "266") (name "VDD33_REF") (class "Default")
      (node (ref "U4") (pin "E2") (pinfunction "VDD33_REF_E2") (pintype "power_in"))
    )
    (net (code "267") (name "VDDA15") (class "Default")
      (node (ref "U4") (pin "L8") (pinfunction "VDDA15_L8") (pintype "power_in"))
    )
    (net (code "268") (name "VDDA15_2") (class "Default")
      (node (ref "U4") (pin "A7") (pinfunction "VDDA15_2_A7") (pintype "power_in"))
    )
    (net (code "269") (name "VDDA15_3") (class "Default")
      (node (ref "U4") (pin "D7") (pinfunction "VDDA15_3_D7") (pintype "power_in"))
    )
    (net (code "270") (name "VDDA15_4") (class "Default")
      (node (ref "U4") (pin "D8") (pinfunction "VDDA15_4_D8") (pintype "power_in"))
    )
    (net (code "271") (name "VDDA15_5") (class "Default")
      (node (ref "U4") (pin "D9") (pinfunction "VDDA15_5_D9") (pintype "power_in"))
    )
    (net (code "272") (name "VDDA15_6") (class "Default")
      (node (ref "U4") (pin "G4") (pinfunction "VDDA15_6_G4") (pintype "power_in"))
    )
    (net (code "273") (name "VDDA15_7") (class "Default")
      (node (ref "U4") (pin "H2") (pinfunction "VDDA15_7_H2") (pintype "power_in"))
    )
    (net (code "274") (name "VDDA15_8") (class "Default")
      (node (ref "U4") (pin "H4") (pinfunction "VDDA15_8_H4") (pintype "power_in"))
    )
    (net (code "275") (name "VDDA15_9") (class "Default")
      (node (ref "U4") (pin "J4") (pinfunction "VDDA15_9_J4") (pintype "power_in"))
    )
    (net (code "276") (name "VDDA15_10") (class "Default")
      (node (ref "U4") (pin "K3") (pinfunction "VDDA15_10_K3") (pintype "power_in"))
    )
    (net (code "277") (name "VDDA15_11") (class "Default")
      (node (ref "U4") (pin "L6") (pinfunction "VDDA15_11_L6") (pintype "power_in"))
    )
    (net (code "278") (name "VDDA15_12") (class "Default")
      (node (ref "U4") (pin "L7") (pinfunction "VDDA15_12_L7") (pintype "power_in"))
    )
    (net (code "279") (name "VDDA33") (class "Default")
      (node (ref "U4") (pin "J3") (pinfunction "VDDA33_J3") (pintype "power_in"))
    )
    (net (code "280") (name "VDD_COMB15") (class "Default")
      (node (ref "U4") (pin "C1") (pinfunction "VDD_COMB15_C1") (pintype "power_in"))
    )
    (net (code "281") (name "VDD_COMB33") (class "Default")
      (node (ref "U4") (pin "F4") (pinfunction "VDD_COMB33_F4") (pintype "power_in"))
    )
    (net (code "282") (name "VDD_COMBIO") (class "Default")
      (node (ref "U4") (pin "D3") (pinfunction "VDD_COMBIO_D3") (pintype "power_in"))
    )
    (net (code "283") (name "VSS") (class "Default")
      (node (ref "U4") (pin "L5") (pinfunction "VSS_L5") (pintype "power_in"))
    )
    (net (code "284") (name "VSSA") (class "Default")
      (node (ref "U4") (pin "K1") (pinfunction "VSSA_K1") (pintype "power_in"))
    )
    (net (code "285") (name "VSSA_2") (class "Default")
      (node (ref "U4") (pin "A5") (pinfunction "VSSA_2_A5") (pintype "power_in"))
    )
    (net (code "286") (name "VSSA_3") (class "Default")
      (node (ref "U4") (pin "C7") (pinfunction "VSSA_3_C7") (pintype "power_in"))
    )
    (net (code "287") (name "VSSA_4") (class "Default")
      (node (ref "U4") (pin "C8") (pinfunction "VSSA_4_C8") (pintype "power_in"))
    )
    (net (code "288") (name "VSSA_5") (class "Default")
      (node (ref "U4") (pin "C9") (pinfunction "VSSA_5_C9") (pintype "power_in"))
    )
    (net (code "289") (name "VSSA_6") (class "Default")
      (node (ref "U4") (pin "G3") (pinfunction "VSSA_6_G3") (pintype "power_in"))
    )
    (net (code "290") (name "VSSA_7") (class "Default")
      (node (ref "U4") (pin "H1") (pinfunction "VSSA_7_H1") (pintype "power_in"))
    )
    (net (code "291") (name "VSSA_REF") (class "Default")
      (node (ref "U4") (pin "E4") (pinfunction "VSSA_REF_E4") (pintype "power_in"))
    )
    (net (code "292") (name "VSSD_REF") (class "Default")
      (node (ref "U4") (pin "D1") (pinfunction "VSSD_REF_D1") (pintype "power_in"))
    )
    (net (code "293") (name "VSS_2") (class "Default")
      (node (ref "U4") (pin "D5") (pinfunction "VSS_2_D5") (pintype "power_in"))
    )
    (net (code "294") (name "VSS_3") (class "Default")
      (node (ref "U4") (pin "D6") (pinfunction "VSS_3_D6") (pintype "power_in"))
    )
    (net (code "295") (name "VSS_4") (class "Default")
      (node (ref "U4") (pin "E5") (pinfunction "VSS_4_E5") (pintype "power_in"))
    )
    (net (code "296") (name "VSS_5") (class "Default")
      (node (ref "U4") (pin "E6") (pinfunction "VSS_5_E6") (pintype "power_in"))
    )
    (net (code "297") (name "VSS_6") (class "Default")
      (node (ref "U4") (pin "E7") (pinfunction "VSS_6_E7") (pintype "power_in"))
    )
    (net (code "298") (name "VSS_7") (class "Default")
      (node (ref "U4") (pin "E8") (pinfunction "VSS_7_E8") (pintype "power_in"))
    )
    (net (code "299") (name "VSS_8") (class "Default")
      (node (ref "U4") (pin "E9") (pinfunction "VSS_8_E9") (pintype "power_in"))
    )
    (net (code "300") (name "VSS_9") (class "Default")
      (node (ref "U4") (pin "F5") (pinfunction "VSS_9_F5") (pintype "power_in"))
    )
    (net (code "301") (name "VSS_10") (class "Default")
      (node (ref "U4") (pin "F6") (pinfunction "VSS_10_F6") (pintype "power_in"))
    )
    (net (code "302") (name "VSS_11") (class "Default")
      (node (ref "U4") (pin "F7") (pinfunction "VSS_11_F7") (pintype "power_in"))
    )
    (net (code "303") (name "VSS_12") (class "Default")
      (node (ref "U4") (pin "F8") (pinfunction "VSS_12_F8") (pintype "power_in"))
    )
    (net (code "304") (name "VSS_13") (class "Default")
      (node (ref "U4") (pin "F9") (pinfunction "VSS_13_F9") (pintype "power_in"))
    )
    (net (code "305") (name "VSS_14") (class "Default")
      (node (ref "U4") (pin "G5") (pinfunction "VSS_14_G5") (pintype "power_in"))
    )
    (net (code "306") (name "VSS_15") (class "Default")
      (node (ref "U4") (pin "G6") (pinfunction "VSS_15_G6") (pintype "power_in"))
    )
    (net (code "307") (name "VSS_16") (class "Default")
      (node (ref "U4") (pin "G7") (pinfunction "VSS_16_G7") (pintype "power_in"))
    )
    (net (code "308") (name "VSS_17") (class "Default")
      (node (ref "U4") (pin "G8") (pinfunction "VSS_17_G8") (pintype "power_in"))
    )
    (net (code "309") (name "VSS_18") (class "Default")
      (node (ref "U4") (pin "G9") (pinfunction "VSS_18_G9") (pintype "power_in"))
    )
    (net (code "310") (name "VSS_19") (class "Default")
      (node (ref "U4") (pin "H5") (pinfunction "VSS_19_H5") (pintype "power_in"))
    )
    (net (code "311") (name "VSS_20") (class "Default")
      (node (ref "U4") (pin "H6") (pinfunction "VSS_20_H6") (pintype "power_in"))
    )
    (net (code "312") (name "VSS_21") (class "Default")
      (node (ref "U4") (pin "H7") (pinfunction "VSS_21_H7") (pintype "power_in"))
    )
    (net (code "313") (name "VSS_22") (class "Default")
      (node (ref "U4") (pin "H8") (pinfunction "VSS_22_H8") (pintype "power_in"))
    )
    (net (code "314") (name "VSS_23") (class "Default")
      (node (ref "U4") (pin "H9") (pinfunction "VSS_23_H9") (pintype "power_in"))
    )
    (net (code "315") (name "VSS_24") (class "Default")
      (node (ref "U4") (pin "J5") (pinfunction "VSS_24_J5") (pintype "power_in"))
    )
    (net (code "316") (name "VSS_25") (class "Default")
      (node (ref "U4") (pin "J6") (pinfunction "VSS_25_J6") (pintype "power_in"))
    )
    (net (code "317") (name "VSS_26") (class "Default")
      (node (ref "U4") (pin "J7") (pinfunction "VSS_26_J7") (pintype "power_in"))
    )
    (net (code "318") (name "VSS_27") (class "Default")
      (node (ref "U4") (pin "J8") (pinfunction "VSS_27_J8") (pintype "power_in"))
    )
    (net (code "319") (name "VSS_28") (class "Default")
      (node (ref "U4") (pin "J9") (pinfunction "VSS_28_J9") (pintype "power_in"))
    )
    (net (code "320") (name "VSS_29") (class "Default")
      (node (ref "U4") (pin "K2") (pinfunction "VSS_29_K2") (pintype "power_in"))
    )
    (net (code "321") (name "VSS_30") (class "Default")
      (node (ref "U4") (pin "K5") (pinfunction "VSS_30_K5") (pintype "power_in"))
    )
    (net (code "322") (name "VSS_31") (class "Default")
      (node (ref "U4") (pin "K6") (pinfunction "VSS_31_K6") (pintype "power_in"))
    )
    (net (code "323") (name "VSS_32") (class "Default")
      (node (ref "U4") (pin "K7") (pinfunction "VSS_32_K7") (pintype "power_in"))
    )
    (net (code "324") (name "VSS_33") (class "Default")
      (node (ref "U4") (pin "K8") (pinfunction "VSS_33_K8") (pintype "power_in"))
    )
    (net (code "325") (name "VSS_34") (class "Default")
      (node (ref "U4") (pin "K9") (pinfunction "VSS_34_K9") (pintype "power_in"))
    )
    (net (code "326") (name "VSS_35") (class "Default")
      (node (ref "U4") (pin "L4") (pinfunction "VSS_35_L4") (pintype "power_in"))
    )
    (net (code "327") (name "WL_NDIS") (class "Default")
      (node (ref "JP5") (pin "1") (pinfunction "1_1") (pintype "passive"))
      (node (ref "RPI-CM1") (pin "89") (pinfunction "WL_~{DISABLE}_89") (pintype "passive"))
    )
    (net (code "328") (name "unconnected-(IC2-LED1{slash}SCL-Pad23)") (class "Default")
      (node (ref "IC2") (pin "23") (pinfunction "LED1/SCL_23") (pintype "bidirectional"))
    )
    (net (code "329") (name "unconnected-(IC2-LED2-Pad24)") (class "Default")
      (node (ref "IC2") (pin "24") (pinfunction "LED2_24") (pintype "bidirectional"))
    )
    (net (code "330") (name "unconnected-(IC2-PWR#-Pad25)") (class "Default")
      (node (ref "IC2") (pin "25") (pinfunction "PWR#_25") (pintype "bidirectional"))
    )
    (net (code "331") (name "unconnected-(IC2-TEST2-Pad12)") (class "Default")
      (node (ref "IC2") (pin "12") (pinfunction "TEST2_12") (pintype "bidirectional"))
    )
    (net (code "332") (name "unconnected-(IC2-TEST3-Pad13)") (class "Default")
      (node (ref "IC2") (pin "13") (pinfunction "TEST3_13") (pintype "bidirectional"))
    )
    (net (code "333") (name "unconnected-(IC2-TEST4-Pad28)") (class "Default")
      (node (ref "IC2") (pin "28") (pinfunction "TEST4_28") (pintype "bidirectional"))
    )
    (net (code "334") (name "unconnected-(IC2-VCC5-Pad20)") (class "Default")
      (node (ref "IC2") (pin "20") (pinfunction "VCC5_20") (pintype "bidirectional"))
    )
    (net (code "335") (name "unconnected-(IC3-ALERT#-Pad8)") (class "Default")
      (node (ref "IC3") (pin "8") (pinfunction "ALERT#_8") (pintype "bidirectional"))
    )
    (net (code "336") (name "unconnected-(IC3-CLK-Pad7)") (class "Default")
      (node (ref "IC3") (pin "7") (pinfunction "CLK_7") (pintype "bidirectional"))
    )
    (net (code "337") (name "unconnected-(IC4-GND_2-Pad8)") (class "Default")
      (node (ref "IC4") (pin "8") (pinfunction "GND_2_8") (pintype "bidirectional"))
    )
    (net (code "338") (name "unconnected-(IC4-N.C._1-Pad6)") (class "Default")
      (node (ref "IC4") (pin "6") (pinfunction "N.C._1_6") (pintype "bidirectional"))
    )
    (net (code "339") (name "unconnected-(IC4-N.C._2-Pad7)") (class "Default")
      (node (ref "IC4") (pin "7") (pinfunction "N.C._2_7") (pintype "bidirectional"))
    )
    (net (code "340") (name "unconnected-(IC4-N.C._3-Pad9)") (class "Default")
      (node (ref "IC4") (pin "9") (pinfunction "N.C._3_9") (pintype "bidirectional"))
    )
    (net (code "341") (name "unconnected-(IC4-N.C._4-Pad10)") (class "Default")
      (node (ref "IC4") (pin "10") (pinfunction "N.C._4_10") (pintype "bidirectional"))
    )
    (net (code "342") (name "unconnected-(IC5-GND_2-Pad8)") (class "Default")
      (node (ref "IC5") (pin "8") (pinfunction "GND_2_8") (pintype "bidirectional"))
    )
    (net (code "343") (name "unconnected-(IC5-N.C._1-Pad6)") (class "Default")
      (node (ref "IC5") (pin "6") (pinfunction "N.C._1_6") (pintype "bidirectional"))
    )
    (net (code "344") (name "unconnected-(IC5-N.C._2-Pad7)") (class "Default")
      (node (ref "IC5") (pin "7") (pinfunction "N.C._2_7") (pintype "bidirectional"))
    )
    (net (code "345") (name "unconnected-(IC5-N.C._3-Pad9)") (class "Default")
      (node (ref "IC5") (pin "9") (pinfunction "N.C._3_9") (pintype "bidirectional"))
    )
    (net (code "346") (name "unconnected-(IC5-N.C._4-Pad10)") (class "Default")
      (node (ref "IC5") (pin "10") (pinfunction "N.C._4_10") (pintype "bidirectional"))
    )
    (net (code "347") (name "unconnected-(J2-SBU1-PadA8)") (class "Default")
      (node (ref "J2") (pin "A8") (pinfunction "SBU1_A8") (pintype "bidirectional"))
    )
    (net (code "348") (name "unconnected-(J2-SBU2-PadB8)") (class "Default")
      (node (ref "J2") (pin "B8") (pinfunction "SBU2_B8") (pintype "bidirectional"))
    )
    (net (code "349") (name "unconnected-(J2-SSRXN1-PadB10)") (class "Default")
      (node (ref "J2") (pin "B10") (pinfunction "SSRXN1_B10") (pintype "bidirectional"))
    )
    (net (code "350") (name "unconnected-(J2-SSRXN2-PadA10)") (class "Default")
      (node (ref "J2") (pin "A10") (pinfunction "SSRXN2_A10") (pintype "bidirectional"))
    )
    (net (code "351") (name "unconnected-(J2-SSRXP1-PadB11)") (class "Default")
      (node (ref "J2") (pin "B11") (pinfunction "SSRXP1_B11") (pintype "bidirectional"))
    )
    (net (code "352") (name "unconnected-(J2-SSRXP2-PadA11)") (class "Default")
      (node (ref "J2") (pin "A11") (pinfunction "SSRXP2_A11") (pintype "bidirectional"))
    )
    (net (code "353") (name "unconnected-(J2-SSTXN1-PadA3)") (class "Default")
      (node (ref "J2") (pin "A3") (pinfunction "SSTXN1_A3") (pintype "bidirectional"))
    )
    (net (code "354") (name "unconnected-(J2-SSTXN2-PadB3)") (class "Default")
      (node (ref "J2") (pin "B3") (pinfunction "SSTXN2_B3") (pintype "bidirectional"))
    )
    (net (code "355") (name "unconnected-(J2-SSTXP1-PadA2)") (class "Default")
      (node (ref "J2") (pin "A2") (pinfunction "SSTXP1_A2") (pintype "bidirectional"))
    )
    (net (code "356") (name "unconnected-(J2-SSTXP2-PadB2)") (class "Default")
      (node (ref "J2") (pin "B2") (pinfunction "SSTXP2_B2") (pintype "bidirectional"))
    )
    (net (code "357") (name "unconnected-(J2-VBUS_2-PadB9)") (class "Default")
      (node (ref "J2") (pin "B9") (pinfunction "VBUS_2_B9") (pintype "bidirectional"))
    )
    (net (code "358") (name "unconnected-(J2-V_BUS_2-PadA9)") (class "Default")
      (node (ref "J2") (pin "A9") (pinfunction "V_BUS_2_A9") (pintype "bidirectional"))
    )
    (net (code "359") (name "unconnected-(J6-Pad14)") (class "Default")
      (node (ref "J6") (pin "14") (pinfunction "14_14") (pintype "bidirectional"))
    )
    (net (code "360") (name "unconnected-(J8-Pad14)") (class "Default")
      (node (ref "J8") (pin "14") (pinfunction "14_14") (pintype "bidirectional"))
    )
    (net (code "361") (name "unconnected-(J9-Pad11)") (class "Default")
      (node (ref "J9") (pin "11") (pinfunction "11_11") (pintype "bidirectional"))
    )
    (net (code "362") (name "unconnected-(J9-Pad12)") (class "Default")
      (node (ref "J9") (pin "12") (pinfunction "12_12") (pintype "bidirectional"))
    )
    (net (code "363") (name "unconnected-(J9-Pad14)") (class "Default")
      (node (ref "J9") (pin "14") (pinfunction "14_14") (pintype "bidirectional"))
    )
    (net (code "364") (name "unconnected-(J9-Pad15)") (class "Default")
      (node (ref "J9") (pin "15") (pinfunction "15_15") (pintype "bidirectional"))
    )
    (net (code "365") (name "unconnected-(J9-Pad17)") (class "Default")
      (node (ref "J9") (pin "17") (pinfunction "17_17") (pintype "bidirectional"))
    )
    (net (code "366") (name "unconnected-(J9-Pad18)") (class "Default")
      (node (ref "J9") (pin "18") (pinfunction "18_18") (pintype "bidirectional"))
    )
    (net (code "367") (name "unconnected-(J9-PadMP1)") (class "Default")
      (node (ref "J9") (pin "MP1") (pinfunction "MP1_MP1") (pintype "bidirectional"))
    )
    (net (code "368") (name "unconnected-(J9-PadMP2)") (class "Default")
      (node (ref "J9") (pin "MP2") (pinfunction "MP2_MP2") (pintype "bidirectional"))
    )
    (net (code "369") (name "unconnected-(J10-Pad17)") (class "Default")
      (node (ref "J10") (pin "17") (pinfunction "17_17") (pintype "bidirectional"))
    )
    (net (code "370") (name "unconnected-(J10-Pad18)") (class "Default")
      (node (ref "J10") (pin "18") (pinfunction "18_18") (pintype "bidirectional"))
    )
    (net (code "371") (name "unconnected-(J10-PadMP1)") (class "Default")
      (node (ref "J10") (pin "MP1") (pinfunction "MP1_MP1") (pintype "bidirectional"))
    )
    (net (code "372") (name "unconnected-(J10-PadMP2)") (class "Default")
      (node (ref "J10") (pin "MP2") (pinfunction "MP2_MP2") (pintype "bidirectional"))
    )
    (net (code "373") (name "unconnected-(J11-Pad11)") (class "Default")
      (node (ref "J11") (pin "11") (pinfunction "11_11") (pintype "bidirectional"))
    )
    (net (code "374") (name "unconnected-(J11-Pad12)") (class "Default")
      (node (ref "J11") (pin "12") (pinfunction "12_12") (pintype "bidirectional"))
    )
    (net (code "375") (name "unconnected-(J11-Pad14)") (class "Default")
      (node (ref "J11") (pin "14") (pinfunction "14_14") (pintype "bidirectional"))
    )
    (net (code "376") (name "unconnected-(J11-Pad15)") (class "Default")
      (node (ref "J11") (pin "15") (pinfunction "15_15") (pintype "bidirectional"))
    )
    (net (code "377") (name "unconnected-(J11-Pad18)") (class "Default")
      (node (ref "J11") (pin "18") (pinfunction "18_18") (pintype "bidirectional"))
    )
    (net (code "378") (name "unconnected-(J11-PadMP1)") (class "Default")
      (node (ref "J11") (pin "MP1") (pinfunction "MP1_MP1") (pintype "bidirectional"))
    )
    (net (code "379") (name "unconnected-(J11-PadMP2)") (class "Default")
      (node (ref "J11") (pin "MP2") (pinfunction "MP2_MP2") (pintype "bidirectional"))
    )
    (net (code "380") (name "unconnected-(J12-Pad18)") (class "Default")
      (node (ref "J12") (pin "18") (pinfunction "18_18") (pintype "bidirectional"))
    )
    (net (code "381") (name "unconnected-(J12-PadMP1)") (class "Default")
      (node (ref "J12") (pin "MP1") (pinfunction "MP1_MP1") (pintype "bidirectional"))
    )
    (net (code "382") (name "unconnected-(J12-PadMP2)") (class "Default")
      (node (ref "J12") (pin "MP2") (pinfunction "MP2_MP2") (pintype "bidirectional"))
    )
    (net (code "383") (name "unconnected-(J13-Pad3)") (class "Default")
      (node (ref "J13") (pin "3") (pinfunction "3_3") (pintype "passive"))
    )
    (net (code "384") (name "unconnected-(J13-Pad5)") (class "Default")
      (node (ref "J13") (pin "5") (pinfunction "5_5") (pintype "passive"))
    )
    (net (code "385") (name "unconnected-(J13-Pad6)") (class "Default")
      (node (ref "J13") (pin "6") (pinfunction "6_6") (pintype "passive"))
    )
    (net (code "386") (name "unconnected-(J13-Pad8)") (class "Default")
      (node (ref "J13") (pin "8") (pinfunction "8_8") (pintype "passive"))
    )
    (net (code "387") (name "unconnected-(J13-Pad9)") (class "Default")
      (node (ref "J13") (pin "9") (pinfunction "9_9") (pintype "passive"))
    )
    (net (code "388") (name "unconnected-(J13-Pad10)") (class "Default")
      (node (ref "J13") (pin "10") (pinfunction "10_10") (pintype "passive"))
    )
    (net (code "389") (name "unconnected-(J13-Pad11)") (class "Default")
      (node (ref "J13") (pin "11") (pinfunction "11_11") (pintype "passive"))
    )
    (net (code "390") (name "unconnected-(J13-Pad12)") (class "Default")
      (node (ref "J13") (pin "12") (pinfunction "12_12") (pintype "passive"))
    )
    (net (code "391") (name "unconnected-(J13-Pad13)") (class "Default")
      (node (ref "J13") (pin "13") (pinfunction "13_13") (pintype "passive"))
    )
    (net (code "392") (name "unconnected-(J13-Pad14)") (class "Default")
      (node (ref "J13") (pin "14") (pinfunction "14_14") (pintype "passive"))
    )
    (net (code "393") (name "unconnected-(J13-Pad15)") (class "Default")
      (node (ref "J13") (pin "15") (pinfunction "15_15") (pintype "passive"))
    )
    (net (code "394") (name "unconnected-(J13-Pad16)") (class "Default")
      (node (ref "J13") (pin "16") (pinfunction "16_16") (pintype "passive"))
    )
    (net (code "395") (name "unconnected-(J13-Pad17)") (class "Default")
      (node (ref "J13") (pin "17") (pinfunction "17_17") (pintype "passive"))
    )
    (net (code "396") (name "unconnected-(J13-Pad19)") (class "Default")
      (node (ref "J13") (pin "19") (pinfunction "19_19") (pintype "passive"))
    )
    (net (code "397") (name "unconnected-(J13-Pad20)") (class "Default")
      (node (ref "J13") (pin "20") (pinfunction "20_20") (pintype "passive"))
    )
    (net (code "398") (name "unconnected-(J13-Pad21)") (class "Default")
      (node (ref "J13") (pin "21") (pinfunction "21_21") (pintype "passive"))
    )
    (net (code "399") (name "unconnected-(J13-Pad22)") (class "Default")
      (node (ref "J13") (pin "22") (pinfunction "22_22") (pintype "passive"))
    )
    (net (code "400") (name "unconnected-(J13-Pad23)") (class "Default")
      (node (ref "J13") (pin "23") (pinfunction "23_23") (pintype "passive"))
    )
    (net (code "401") (name "unconnected-(J13-Pad24)") (class "Default")
      (node (ref "J13") (pin "24") (pinfunction "24_24") (pintype "passive"))
    )
    (net (code "402") (name "unconnected-(J13-Pad25)") (class "Default")
      (node (ref "J13") (pin "25") (pinfunction "25_25") (pintype "passive"))
    )
    (net (code "403") (name "unconnected-(J13-Pad26)") (class "Default")
      (node (ref "J13") (pin "26") (pinfunction "26_26") (pintype "passive"))
    )
    (net (code "404") (name "unconnected-(J13-Pad27)") (class "Default")
      (node (ref "J13") (pin "27") (pinfunction "27_27") (pintype "passive"))
    )
    (net (code "405") (name "unconnected-(J13-Pad28)") (class "Default")
      (node (ref "J13") (pin "28") (pinfunction "28_28") (pintype "passive"))
    )
    (net (code "406") (name "unconnected-(J13-Pad29)") (class "Default")
      (node (ref "J13") (pin "29") (pinfunction "29_29") (pintype "passive"))
    )
    (net (code "407") (name "unconnected-(J13-Pad30)") (class "Default")
      (node (ref "J13") (pin "30") (pinfunction "30_30") (pintype "passive"))
    )
    (net (code "408") (name "unconnected-(J13-Pad31)") (class "Default")
      (node (ref "J13") (pin "31") (pinfunction "31_31") (pintype "passive"))
    )
    (net (code "409") (name "unconnected-(J13-Pad32)") (class "Default")
      (node (ref "J13") (pin "32") (pinfunction "32_32") (pintype "passive"))
    )
    (net (code "410") (name "unconnected-(J13-Pad34)") (class "Default")
      (node (ref "J13") (pin "34") (pinfunction "34_34") (pintype "passive"))
    )
    (net (code "411") (name "unconnected-(J13-Pad36)") (class "Default")
      (node (ref "J13") (pin "36") (pinfunction "36_36") (pintype "passive"))
    )
    (net (code "412") (name "unconnected-(J13-Pad38)") (class "Default")
      (node (ref "J13") (pin "38") (pinfunction "38_38") (pintype "passive"))
    )
    (net (code "413") (name "unconnected-(J13-Pad40)") (class "Default")
      (node (ref "J13") (pin "40") (pinfunction "40_40") (pintype "passive"))
    )
    (net (code "414") (name "unconnected-(J13-Pad42)") (class "Default")
      (node (ref "J13") (pin "42") (pinfunction "42_42") (pintype "passive"))
    )
    (net (code "415") (name "unconnected-(J13-Pad44)") (class "Default")
      (node (ref "J13") (pin "44") (pinfunction "44_44") (pintype "passive"))
    )
    (net (code "416") (name "unconnected-(J13-Pad46)") (class "Default")
      (node (ref "J13") (pin "46") (pinfunction "46_46") (pintype "passive"))
    )
    (net (code "417") (name "unconnected-(J13-Pad48)") (class "Default")
      (node (ref "J13") (pin "48") (pinfunction "48_48") (pintype "passive"))
    )
    (net (code "418") (name "unconnected-(J13-Pad50)") (class "Default")
      (node (ref "J13") (pin "50") (pinfunction "50_50") (pintype "passive"))
    )
    (net (code "419") (name "unconnected-(J13-Pad54)") (class "Default")
      (node (ref "J13") (pin "54") (pinfunction "54_54") (pintype "passive"))
    )
    (net (code "420") (name "unconnected-(J13-Pad56)") (class "Default")
      (node (ref "J13") (pin "56") (pinfunction "56_56") (pintype "passive"))
    )
    (net (code "421") (name "unconnected-(J13-Pad58)") (class "Default")
      (node (ref "J13") (pin "58") (pinfunction "58_58") (pintype "passive"))
    )
    (net (code "422") (name "unconnected-(J13-Pad67)") (class "Default")
      (node (ref "J13") (pin "67") (pinfunction "67_67") (pintype "passive"))
    )
    (net (code "423") (name "unconnected-(J13-Pad68)") (class "Default")
      (node (ref "J13") (pin "68") (pinfunction "68_68") (pintype "passive"))
    )
    (net (code "424") (name "unconnected-(J13-Pad70)") (class "Default")
      (node (ref "J13") (pin "70") (pinfunction "70_70") (pintype "passive"))
    )
    (net (code "425") (name "unconnected-(J13-Pad71)") (class "Default")
      (node (ref "J13") (pin "71") (pinfunction "71_71") (pintype "passive"))
    )
    (net (code "426") (name "unconnected-(J13-Pad73)") (class "Default")
      (node (ref "J13") (pin "73") (pinfunction "73_73") (pintype "passive"))
    )
    (net (code "427") (name "unconnected-(J14-Pad3)") (class "Default")
      (node (ref "J14") (pin "3") (pinfunction "3_3") (pintype "passive"))
    )
    (net (code "428") (name "unconnected-(J14-Pad5)") (class "Default")
      (node (ref "J14") (pin "5") (pinfunction "5_5") (pintype "passive"))
    )
    (net (code "429") (name "unconnected-(J14-Pad6)") (class "Default")
      (node (ref "J14") (pin "6") (pinfunction "6_6") (pintype "passive"))
    )
    (net (code "430") (name "unconnected-(J14-Pad8)") (class "Default")
      (node (ref "J14") (pin "8") (pinfunction "8_8") (pintype "passive"))
    )
    (net (code "431") (name "unconnected-(J14-Pad9)") (class "Default")
      (node (ref "J14") (pin "9") (pinfunction "9_9") (pintype "passive"))
    )
    (net (code "432") (name "unconnected-(J14-Pad10)") (class "Default")
      (node (ref "J14") (pin "10") (pinfunction "10_10") (pintype "passive"))
    )
    (net (code "433") (name "unconnected-(J14-Pad11)") (class "Default")
      (node (ref "J14") (pin "11") (pinfunction "11_11") (pintype "passive"))
    )
    (net (code "434") (name "unconnected-(J14-Pad12)") (class "Default")
      (node (ref "J14") (pin "12") (pinfunction "12_12") (pintype "passive"))
    )
    (net (code "435") (name "unconnected-(J14-Pad13)") (class "Default")
      (node (ref "J14") (pin "13") (pinfunction "13_13") (pintype "passive"))
    )
    (net (code "436") (name "unconnected-(J14-Pad14)") (class "Default")
      (node (ref "J14") (pin "14") (pinfunction "14_14") (pintype "passive"))
    )
    (net (code "437") (name "unconnected-(J14-Pad15)") (class "Default")
      (node (ref "J14") (pin "15") (pinfunction "15_15") (pintype "passive"))
    )
    (net (code "438") (name "unconnected-(J14-Pad16)") (class "Default")
      (node (ref "J14") (pin "16") (pinfunction "16_16") (pintype "passive"))
    )
    (net (code "439") (name "unconnected-(J14-Pad17)") (class "Default")
      (node (ref "J14") (pin "17") (pinfunction "17_17") (pintype "passive"))
    )
    (net (code "440") (name "unconnected-(J14-Pad19)") (class "Default")
      (node (ref "J14") (pin "19") (pinfunction "19_19") (pintype "passive"))
    )
    (net (code "441") (name "unconnected-(J14-Pad20)") (class "Default")
      (node (ref "J14") (pin "20") (pinfunction "20_20") (pintype "passive"))
    )
    (net (code "442") (name "unconnected-(J14-Pad21)") (class "Default")
      (node (ref "J14") (pin "21") (pinfunction "21_21") (pintype "passive"))
    )
    (net (code "443") (name "unconnected-(J14-Pad22)") (class "Default")
      (node (ref "J14") (pin "22") (pinfunction "22_22") (pintype "passive"))
    )
    (net (code "444") (name "unconnected-(J14-Pad23)") (class "Default")
      (node (ref "J14") (pin "23") (pinfunction "23_23") (pintype "passive"))
    )
    (net (code "445") (name "unconnected-(J14-Pad24)") (class "Default")
      (node (ref "J14") (pin "24") (pinfunction "24_24") (pintype "passive"))
    )
    (net (code "446") (name "unconnected-(J14-Pad25)") (class "Default")
      (node (ref "J14") (pin "25") (pinfunction "25_25") (pintype "passive"))
    )
    (net (code "447") (name "unconnected-(J14-Pad26)") (class "Default")
      (node (ref "J14") (pin "26") (pinfunction "26_26") (pintype "passive"))
    )
    (net (code "448") (name "unconnected-(J14-Pad27)") (class "Default")
      (node (ref "J14") (pin "27") (pinfunction "27_27") (pintype "passive"))
    )
    (net (code "449") (name "unconnected-(J14-Pad28)") (class "Default")
      (node (ref "J14") (pin "28") (pinfunction "28_28") (pintype "passive"))
    )
    (net (code "450") (name "unconnected-(J14-Pad29)") (class "Default")
      (node (ref "J14") (pin "29") (pinfunction "29_29") (pintype "passive"))
    )
    (net (code "451") (name "unconnected-(J14-Pad30)") (class "Default")
      (node (ref "J14") (pin "30") (pinfunction "30_30") (pintype "passive"))
    )
    (net (code "452") (name "unconnected-(J14-Pad31)") (class "Default")
      (node (ref "J14") (pin "31") (pinfunction "31_31") (pintype "passive"))
    )
    (net (code "453") (name "unconnected-(J14-Pad32)") (class "Default")
      (node (ref "J14") (pin "32") (pinfunction "32_32") (pintype "passive"))
    )
    (net (code "454") (name "unconnected-(J14-Pad34)") (class "Default")
      (node (ref "J14") (pin "34") (pinfunction "34_34") (pintype "passive"))
    )
    (net (code "455") (name "unconnected-(J14-Pad36)") (class "Default")
      (node (ref "J14") (pin "36") (pinfunction "36_36") (pintype "passive"))
    )
    (net (code "456") (name "unconnected-(J14-Pad38)") (class "Default")
      (node (ref "J14") (pin "38") (pinfunction "38_38") (pintype "passive"))
    )
    (net (code "457") (name "unconnected-(J14-Pad40)") (class "Default")
      (node (ref "J14") (pin "40") (pinfunction "40_40") (pintype "passive"))
    )
    (net (code "458") (name "unconnected-(J14-Pad42)") (class "Default")
      (node (ref "J14") (pin "42") (pinfunction "42_42") (pintype "passive"))
    )
    (net (code "459") (name "unconnected-(J14-Pad44)") (class "Default")
      (node (ref "J14") (pin "44") (pinfunction "44_44") (pintype "passive"))
    )
    (net (code "460") (name "unconnected-(J14-Pad46)") (class "Default")
      (node (ref "J14") (pin "46") (pinfunction "46_46") (pintype "passive"))
    )
    (net (code "461") (name "unconnected-(J14-Pad48)") (class "Default")
      (node (ref "J14") (pin "48") (pinfunction "48_48") (pintype "passive"))
    )
    (net (code "462") (name "unconnected-(J14-Pad50)") (class "Default")
      (node (ref "J14") (pin "50") (pinfunction "50_50") (pintype "passive"))
    )
    (net (code "463") (name "unconnected-(J14-Pad54)") (class "Default")
      (node (ref "J14") (pin "54") (pinfunction "54_54") (pintype "passive"))
    )
    (net (code "464") (name "unconnected-(J14-Pad56)") (class "Default")
      (node (ref "J14") (pin "56") (pinfunction "56_56") (pintype "passive"))
    )
    (net (code "465") (name "unconnected-(J14-Pad58)") (class "Default")
      (node (ref "J14") (pin "58") (pinfunction "58_58") (pintype "passive"))
    )
    (net (code "466") (name "unconnected-(J14-Pad67)") (class "Default")
      (node (ref "J14") (pin "67") (pinfunction "67_67") (pintype "passive"))
    )
    (net (code "467") (name "unconnected-(J14-Pad68)") (class "Default")
      (node (ref "J14") (pin "68") (pinfunction "68_68") (pintype "passive"))
    )
    (net (code "468") (name "unconnected-(J14-Pad70)") (class "Default")
      (node (ref "J14") (pin "70") (pinfunction "70_70") (pintype "passive"))
    )
    (net (code "469") (name "unconnected-(J14-Pad71)") (class "Default")
      (node (ref "J14") (pin "71") (pinfunction "71_71") (pintype "passive"))
    )
    (net (code "470") (name "unconnected-(J14-Pad73)") (class "Default")
      (node (ref "J14") (pin "73") (pinfunction "73_73") (pintype "passive"))
    )
    (net (code "471") (name "unconnected-(J15-Pad3)") (class "Default")
      (node (ref "J15") (pin "3") (pinfunction "3_3") (pintype "passive"))
    )
    (net (code "472") (name "unconnected-(J15-Pad5)") (class "Default")
      (node (ref "J15") (pin "5") (pinfunction "5_5") (pintype "passive"))
    )
    (net (code "473") (name "unconnected-(J15-Pad6)") (class "Default")
      (node (ref "J15") (pin "6") (pinfunction "6_6") (pintype "passive"))
    )
    (net (code "474") (name "unconnected-(J15-Pad8)") (class "Default")
      (node (ref "J15") (pin "8") (pinfunction "8_8") (pintype "passive"))
    )
    (net (code "475") (name "unconnected-(J15-Pad9)") (class "Default")
      (node (ref "J15") (pin "9") (pinfunction "9_9") (pintype "passive"))
    )
    (net (code "476") (name "unconnected-(J15-Pad10)") (class "Default")
      (node (ref "J15") (pin "10") (pinfunction "10_10") (pintype "passive"))
    )
    (net (code "477") (name "unconnected-(J15-Pad11)") (class "Default")
      (node (ref "J15") (pin "11") (pinfunction "11_11") (pintype "passive"))
    )
    (net (code "478") (name "unconnected-(J15-Pad12)") (class "Default")
      (node (ref "J15") (pin "12") (pinfunction "12_12") (pintype "passive"))
    )
    (net (code "479") (name "unconnected-(J15-Pad13)") (class "Default")
      (node (ref "J15") (pin "13") (pinfunction "13_13") (pintype "passive"))
    )
    (net (code "480") (name "unconnected-(J15-Pad14)") (class "Default")
      (node (ref "J15") (pin "14") (pinfunction "14_14") (pintype "passive"))
    )
    (net (code "481") (name "unconnected-(J15-Pad15)") (class "Default")
      (node (ref "J15") (pin "15") (pinfunction "15_15") (pintype "passive"))
    )
    (net (code "482") (name "unconnected-(J15-Pad16)") (class "Default")
      (node (ref "J15") (pin "16") (pinfunction "16_16") (pintype "passive"))
    )
    (net (code "483") (name "unconnected-(J15-Pad17)") (class "Default")
      (node (ref "J15") (pin "17") (pinfunction "17_17") (pintype "passive"))
    )
    (net (code "484") (name "unconnected-(J15-Pad19)") (class "Default")
      (node (ref "J15") (pin "19") (pinfunction "19_19") (pintype "passive"))
    )
    (net (code "485") (name "unconnected-(J15-Pad20)") (class "Default")
      (node (ref "J15") (pin "20") (pinfunction "20_20") (pintype "passive"))
    )
    (net (code "486") (name "unconnected-(J15-Pad21)") (class "Default")
      (node (ref "J15") (pin "21") (pinfunction "21_21") (pintype "passive"))
    )
    (net (code "487") (name "unconnected-(J15-Pad22)") (class "Default")
      (node (ref "J15") (pin "22") (pinfunction "22_22") (pintype "passive"))
    )
    (net (code "488") (name "unconnected-(J15-Pad23)") (class "Default")
      (node (ref "J15") (pin "23") (pinfunction "23_23") (pintype "passive"))
    )
    (net (code "489") (name "unconnected-(J15-Pad24)") (class "Default")
      (node (ref "J15") (pin "24") (pinfunction "24_24") (pintype "passive"))
    )
    (net (code "490") (name "unconnected-(J15-Pad25)") (class "Default")
      (node (ref "J15") (pin "25") (pinfunction "25_25") (pintype "passive"))
    )
    (net (code "491") (name "unconnected-(J15-Pad26)") (class "Default")
      (node (ref "J15") (pin "26") (pinfunction "26_26") (pintype "passive"))
    )
    (net (code "492") (name "unconnected-(J15-Pad27)") (class "Default")
      (node (ref "J15") (pin "27") (pinfunction "27_27") (pintype "passive"))
    )
    (net (code "493") (name "unconnected-(J15-Pad28)") (class "Default")
      (node (ref "J15") (pin "28") (pinfunction "28_28") (pintype "passive"))
    )
    (net (code "494") (name "unconnected-(J15-Pad29)") (class "Default")
      (node (ref "J15") (pin "29") (pinfunction "29_29") (pintype "passive"))
    )
    (net (code "495") (name "unconnected-(J15-Pad30)") (class "Default")
      (node (ref "J15") (pin "30") (pinfunction "30_30") (pintype "passive"))
    )
    (net (code "496") (name "unconnected-(J15-Pad31)") (class "Default")
      (node (ref "J15") (pin "31") (pinfunction "31_31") (pintype "passive"))
    )
    (net (code "497") (name "unconnected-(J15-Pad32)") (class "Default")
      (node (ref "J15") (pin "32") (pinfunction "32_32") (pintype "passive"))
    )
    (net (code "498") (name "unconnected-(J15-Pad34)") (class "Default")
      (node (ref "J15") (pin "34") (pinfunction "34_34") (pintype "passive"))
    )
    (net (code "499") (name "unconnected-(J15-Pad36)") (class "Default")
      (node (ref "J15") (pin "36") (pinfunction "36_36") (pintype "passive"))
    )
    (net (code "500") (name "unconnected-(J15-Pad38)") (class "Default")
      (node (ref "J15") (pin "38") (pinfunction "38_38") (pintype "passive"))
    )
    (net (code "501") (name "unconnected-(J15-Pad40)") (class "Default")
      (node (ref "J15") (pin "40") (pinfunction "40_40") (pintype "passive"))
    )
    (net (code "502") (name "unconnected-(J15-Pad42)") (class "Default")
      (node (ref "J15") (pin "42") (pinfunction "42_42") (pintype "passive"))
    )
    (net (code "503") (name "unconnected-(J15-Pad44)") (class "Default")
      (node (ref "J15") (pin "44") (pinfunction "44_44") (pintype "passive"))
    )
    (net (code "504") (name "unconnected-(J15-Pad46)") (class "Default")
      (node (ref "J15") (pin "46") (pinfunction "46_46") (pintype "passive"))
    )
    (net (code "505") (name "unconnected-(J15-Pad48)") (class "Default")
      (node (ref "J15") (pin "48") (pinfunction "48_48") (pintype "passive"))
    )
    (net (code "506") (name "unconnected-(J15-Pad50)") (class "Default")
      (node (ref "J15") (pin "50") (pinfunction "50_50") (pintype "passive"))
    )
    (net (code "507") (name "unconnected-(J15-Pad54)") (class "Default")
      (node (ref "J15") (pin "54") (pinfunction "54_54") (pintype "passive"))
    )
    (net (code "508") (name "unconnected-(J15-Pad56)") (class "Default")
      (node (ref "J15") (pin "56") (pinfunction "56_56") (pintype "passive"))
    )
    (net (code "509") (name "unconnected-(J15-Pad58)") (class "Default")
      (node (ref "J15") (pin "58") (pinfunction "58_58") (pintype "passive"))
    )
    (net (code "510") (name "unconnected-(J15-Pad67)") (class "Default")
      (node (ref "J15") (pin "67") (pinfunction "67_67") (pintype "passive"))
    )
    (net (code "511") (name "unconnected-(J15-Pad68)") (class "Default")
      (node (ref "J15") (pin "68") (pinfunction "68_68") (pintype "passive"))
    )
    (net (code "512") (name "unconnected-(J15-Pad70)") (class "Default")
      (node (ref "J15") (pin "70") (pinfunction "70_70") (pintype "passive"))
    )
    (net (code "513") (name "unconnected-(J15-Pad71)") (class "Default")
      (node (ref "J15") (pin "71") (pinfunction "71_71") (pintype "passive"))
    )
    (net (code "514") (name "unconnected-(J15-Pad73)") (class "Default")
      (node (ref "J15") (pin "73") (pinfunction "73_73") (pintype "passive"))
    )
    (net (code "515") (name "unconnected-(J16-Pad3)") (class "Default")
      (node (ref "J16") (pin "3") (pinfunction "3_3") (pintype "passive"))
    )
    (net (code "516") (name "unconnected-(J16-Pad5)") (class "Default")
      (node (ref "J16") (pin "5") (pinfunction "5_5") (pintype "passive"))
    )
    (net (code "517") (name "unconnected-(J16-Pad6)") (class "Default")
      (node (ref "J16") (pin "6") (pinfunction "6_6") (pintype "passive"))
    )
    (net (code "518") (name "unconnected-(J16-Pad8)") (class "Default")
      (node (ref "J16") (pin "8") (pinfunction "8_8") (pintype "passive"))
    )
    (net (code "519") (name "unconnected-(J16-Pad9)") (class "Default")
      (node (ref "J16") (pin "9") (pinfunction "9_9") (pintype "passive"))
    )
    (net (code "520") (name "unconnected-(J16-Pad10)") (class "Default")
      (node (ref "J16") (pin "10") (pinfunction "10_10") (pintype "passive"))
    )
    (net (code "521") (name "unconnected-(J16-Pad11)") (class "Default")
      (node (ref "J16") (pin "11") (pinfunction "11_11") (pintype "passive"))
    )
    (net (code "522") (name "unconnected-(J16-Pad12)") (class "Default")
      (node (ref "J16") (pin "12") (pinfunction "12_12") (pintype "passive"))
    )
    (net (code "523") (name "unconnected-(J16-Pad13)") (class "Default")
      (node (ref "J16") (pin "13") (pinfunction "13_13") (pintype "passive"))
    )
    (net (code "524") (name "unconnected-(J16-Pad14)") (class "Default")
      (node (ref "J16") (pin "14") (pinfunction "14_14") (pintype "passive"))
    )
    (net (code "525") (name "unconnected-(J16-Pad15)") (class "Default")
      (node (ref "J16") (pin "15") (pinfunction "15_15") (pintype "passive"))
    )
    (net (code "526") (name "unconnected-(J16-Pad16)") (class "Default")
      (node (ref "J16") (pin "16") (pinfunction "16_16") (pintype "passive"))
    )
    (net (code "527") (name "unconnected-(J16-Pad17)") (class "Default")
      (node (ref "J16") (pin "17") (pinfunction "17_17") (pintype "passive"))
    )
    (net (code "528") (name "unconnected-(J16-Pad19)") (class "Default")
      (node (ref "J16") (pin "19") (pinfunction "19_19") (pintype "passive"))
    )
    (net (code "529") (name "unconnected-(J16-Pad20)") (class "Default")
      (node (ref "J16") (pin "20") (pinfunction "20_20") (pintype "passive"))
    )
    (net (code "530") (name "unconnected-(J16-Pad21)") (class "Default")
      (node (ref "J16") (pin "21") (pinfunction "21_21") (pintype "passive"))
    )
    (net (code "531") (name "unconnected-(J16-Pad22)") (class "Default")
      (node (ref "J16") (pin "22") (pinfunction "22_22") (pintype "passive"))
    )
    (net (code "532") (name "unconnected-(J16-Pad23)") (class "Default")
      (node (ref "J16") (pin "23") (pinfunction "23_23") (pintype "passive"))
    )
    (net (code "533") (name "unconnected-(J16-Pad24)") (class "Default")
      (node (ref "J16") (pin "24") (pinfunction "24_24") (pintype "passive"))
    )
    (net (code "534") (name "unconnected-(J16-Pad25)") (class "Default")
      (node (ref "J16") (pin "25") (pinfunction "25_25") (pintype "passive"))
    )
    (net (code "535") (name "unconnected-(J16-Pad26)") (class "Default")
      (node (ref "J16") (pin "26") (pinfunction "26_26") (pintype "passive"))
    )
    (net (code "536") (name "unconnected-(J16-Pad27)") (class "Default")
      (node (ref "J16") (pin "27") (pinfunction "27_27") (pintype "passive"))
    )
    (net (code "537") (name "unconnected-(J16-Pad28)") (class "Default")
      (node (ref "J16") (pin "28") (pinfunction "28_28") (pintype "passive"))
    )
    (net (code "538") (name "unconnected-(J16-Pad29)") (class "Default")
      (node (ref "J16") (pin "29") (pinfunction "29_29") (pintype "passive"))
    )
    (net (code "539") (name "unconnected-(J16-Pad30)") (class "Default")
      (node (ref "J16") (pin "30") (pinfunction "30_30") (pintype "passive"))
    )
    (net (code "540") (name "unconnected-(J16-Pad31)") (class "Default")
      (node (ref "J16") (pin "31") (pinfunction "31_31") (pintype "passive"))
    )
    (net (code "541") (name "unconnected-(J16-Pad32)") (class "Default")
      (node (ref "J16") (pin "32") (pinfunction "32_32") (pintype "passive"))
    )
    (net (code "542") (name "unconnected-(J16-Pad34)") (class "Default")
      (node (ref "J16") (pin "34") (pinfunction "34_34") (pintype "passive"))
    )
    (net (code "543") (name "unconnected-(J16-Pad36)") (class "Default")
      (node (ref "J16") (pin "36") (pinfunction "36_36") (pintype "passive"))
    )
    (net (code "544") (name "unconnected-(J16-Pad38)") (class "Default")
      (node (ref "J16") (pin "38") (pinfunction "38_38") (pintype "passive"))
    )
    (net (code "545") (name "unconnected-(J16-Pad40)") (class "Default")
      (node (ref "J16") (pin "40") (pinfunction "40_40") (pintype "passive"))
    )
    (net (code "546") (name "unconnected-(J16-Pad42)") (class "Default")
      (node (ref "J16") (pin "42") (pinfunction "42_42") (pintype "passive"))
    )
    (net (code "547") (name "unconnected-(J16-Pad44)") (class "Default")
      (node (ref "J16") (pin "44") (pinfunction "44_44") (pintype "passive"))
    )
    (net (code "548") (name "unconnected-(J16-Pad46)") (class "Default")
      (node (ref "J16") (pin "46") (pinfunction "46_46") (pintype "passive"))
    )
    (net (code "549") (name "unconnected-(J16-Pad48)") (class "Default")
      (node (ref "J16") (pin "48") (pinfunction "48_48") (pintype "passive"))
    )
    (net (code "550") (name "unconnected-(J16-Pad50)") (class "Default")
      (node (ref "J16") (pin "50") (pinfunction "50_50") (pintype "passive"))
    )
    (net (code "551") (name "unconnected-(J16-Pad54)") (class "Default")
      (node (ref "J16") (pin "54") (pinfunction "54_54") (pintype "passive"))
    )
    (net (code "552") (name "unconnected-(J16-Pad56)") (class "Default")
      (node (ref "J16") (pin "56") (pinfunction "56_56") (pintype "passive"))
    )
    (net (code "553") (name "unconnected-(J16-Pad58)") (class "Default")
      (node (ref "J16") (pin "58") (pinfunction "58_58") (pintype "passive"))
    )
    (net (code "554") (name "unconnected-(J16-Pad67)") (class "Default")
      (node (ref "J16") (pin "67") (pinfunction "67_67") (pintype "passive"))
    )
    (net (code "555") (name "unconnected-(J16-Pad68)") (class "Default")
      (node (ref "J16") (pin "68") (pinfunction "68_68") (pintype "passive"))
    )
    (net (code "556") (name "unconnected-(J16-Pad70)") (class "Default")
      (node (ref "J16") (pin "70") (pinfunction "70_70") (pintype "passive"))
    )
    (net (code "557") (name "unconnected-(J16-Pad71)") (class "Default")
      (node (ref "J16") (pin "71") (pinfunction "71_71") (pintype "passive"))
    )
    (net (code "558") (name "unconnected-(J16-Pad73)") (class "Default")
      (node (ref "J16") (pin "73") (pinfunction "73_73") (pintype "passive"))
    )
    (net (code "559") (name "unconnected-(RPI-CM1A-ETH_~{LED1}-Pad19)") (class "Default")
      (node (ref "RPI-CM1") (pin "19") (pinfunction "ETH_~{LED1}_19") (pintype "passive"))
    )
    (net (code "560") (name "unconnected-(RPI-CM1A-SD_DAT4-Pad68)") (class "Default")
      (node (ref "RPI-CM1") (pin "68") (pinfunction "SD_DAT4_68") (pintype "passive"))
    )
    (net (code "561") (name "unconnected-(RPI-CM1A-SD_DAT5-Pad64)") (class "Default")
      (node (ref "RPI-CM1") (pin "64") (pinfunction "SD_DAT5_64") (pintype "passive"))
    )
    (net (code "562") (name "unconnected-(RPI-CM1A-SD_DAT6-Pad72)") (class "Default")
      (node (ref "RPI-CM1") (pin "72") (pinfunction "SD_DAT6_72") (pintype "passive"))
    )
    (net (code "563") (name "unconnected-(RPI-CM1A-SD_DAT7-Pad70)") (class "Default")
      (node (ref "RPI-CM1") (pin "70") (pinfunction "SD_DAT7_70") (pintype "passive"))
    )
    (net (code "564") (name "unconnected-(RPI-CM1A-SD_VDD_OVERRIDE-Pad73)") (class "Default")
      (node (ref "RPI-CM1") (pin "73") (pinfunction "SD_VDD_OVERRIDE_73") (pintype "passive"))
    )
    (net (code "565") (name "unconnected-(RPI-CM1B-HDMI0_SCL-Pad200)") (class "Default")
      (node (ref "RPI-CM1") (pin "200") (pinfunction "HDMI0_SCL_200") (pintype "passive"))
    )
    (net (code "566") (name "unconnected-(RPI-CM1B-RESERVED-Pad104)") (class "Default")
      (node (ref "RPI-CM1") (pin "104") (pinfunction "RESERVED_104") (pintype "passive"))
    )
    (net (code "567") (name "unconnected-(RPI-CM1B-RESERVED-Pad106)") (class "Default")
      (node (ref "RPI-CM1") (pin "106") (pinfunction "RESERVED_106") (pintype "passive"))
    )
    (net (code "568") (name "unconnected-(U2-NC-Pad1)") (class "Default")
      (node (ref "U2") (pin "1") (pinfunction "NC_1") (pintype "no_connect"))
    )
    (net (code "569") (name "unconnected-(U3-NC-Pad1)") (class "Default")
      (node (ref "U3") (pin "1") (pinfunction "NC_1") (pintype "no_connect"))
    )
    (net (code "570") (name "unconnected-(U4A-DN1_PERN-PadB6)") (class "Default")
      (node (ref "U4") (pin "B6") (pinfunction "DN1_PERN_B6") (pintype "passive"))
    )
    (net (code "571") (name "unconnected-(U4A-DN1_PERP-PadA6)") (class "Default")
      (node (ref "U4") (pin "A6") (pinfunction "DN1_PERP_A6") (pintype "passive"))
    )
    (net (code "572") (name "unconnected-(U4A-DN1_PETN-PadB8)") (class "Default")
      (node (ref "U4") (pin "B8") (pinfunction "DN1_PETN_B8") (pintype "passive"))
    )
    (net (code "573") (name "unconnected-(U4A-DN1_PETP-PadA8)") (class "Default")
      (node (ref "U4") (pin "A8") (pinfunction "DN1_PETP_A8") (pintype "passive"))
    )
    (net (code "574") (name "unconnected-(U4A-DN1_REFCK_ON-PadB9)") (class "Default")
      (node (ref "U4") (pin "B9") (pinfunction "DN1_REFCK_ON_B9") (pintype "output"))
    )
    (net (code "575") (name "unconnected-(U4A-DN1_REFCK_OP-PadA9)") (class "Default")
      (node (ref "U4") (pin "A9") (pinfunction "DN1_REFCK_OP_A9") (pintype "output"))
    )
    (net (code "576") (name "unconnected-(U4A-GPIO0-PadC6)") (class "Default")
      (node (ref "U4") (pin "C6") (pinfunction "GPIO0_C6") (pintype "bidirectional"))
    )
    (net (code "577") (name "unconnected-(U4A-GPIO18-PadL3)") (class "Default")
      (node (ref "U4") (pin "L3") (pinfunction "GPIO18_L3") (pintype "bidirectional"))
    )
    (net (code "578") (name "unconnected-(U4A-REFR0-PadD2)") (class "Default")
      (node (ref "U4") (pin "D2") (pinfunction "REFR0_D2") (pintype "passive"))
    )
    (net (code "579") (name "unconnected-(U4A-REFR1-PadE3)") (class "Default")
      (node (ref "U4") (pin "E3") (pinfunction "REFR1_E3") (pintype "passive"))
    )
    (net (code "580") (name "unconnected-(U4A-RSVD-PadD4)") (class "Default")
      (node (ref "U4") (pin "D4") (pinfunction "RSVD_D4") (pintype "no_connect"))
    )
    (net (code "581") (name "unconnected-(U4A-RSVD_2-PadC4)") (class "Default")
      (node (ref "U4") (pin "C4") (pinfunction "RSVD_2_C4") (pintype "no_connect"))
    )
    (net (code "582") (name "unconnected-(U4A-UP_PERN-PadJ2)") (class "Default")
      (node (ref "U4") (pin "J2") (pinfunction "UP_PERN_J2") (pintype "passive"))
    )
    (net (code "583") (name "unconnected-(U4A-UP_PERP-PadJ1)") (class "Default")
      (node (ref "U4") (pin "J1") (pinfunction "UP_PERP_J1") (pintype "passive"))
    )
    (net (code "584") (name "unconnected-(U4A-UP_PETN-PadG2)") (class "Default")
      (node (ref "U4") (pin "G2") (pinfunction "UP_PETN_G2") (pintype "passive"))
    )
    (net (code "585") (name "unconnected-(U4A-UP_PETP-PadG1)") (class "Default")
      (node (ref "U4") (pin "G1") (pinfunction "UP_PETP_G1") (pintype "passive"))
    )
    (net (code "586") (name "unconnected-(U4A-UP_REFCKIN-PadL2)") (class "Default")
      (node (ref "U4") (pin "L2") (pinfunction "UP_REFCKIN_L2") (pintype "input"))
    )
    (net (code "587") (name "unconnected-(U4A-UP_REFCKIP-PadL1)") (class "Default")
      (node (ref "U4") (pin "L1") (pinfunction "UP_REFCKIP_L1") (pintype "input"))
    )
    (net (code "588") (name "unconnected-(U4A-~{DN1_PERST}-PadB5)") (class "Default")
      (node (ref "U4") (pin "B5") (pinfunction "~{DN1_PERST}_B5") (pintype "output"))
    )
    (net (code "589") (name "unconnected-(U4A-~{DN2_PERST}-PadA2)") (class "Default")
      (node (ref "U4") (pin "A2") (pinfunction "~{DN2_PERST}_A2") (pintype "output"))
    )
    (net (code "590") (name "unconnected-(U4A-~{DN3_PERST}-PadA1)") (class "Default")
      (node (ref "U4") (pin "A1") (pinfunction "~{DN3_PERST}_A1") (pintype "output"))
    )
    (net (code "591") (name "unconnected-(U4A-~{GRST}-PadC2)") (class "Default")
      (node (ref "U4") (pin "C2") (pinfunction "~{GRST}_C2") (pintype "input"))
    )
    (net (code "592") (name "unconnected-(U4A-~{UP_PERST}-PadB1)") (class "Default")
      (node (ref "U4") (pin "B1") (pinfunction "~{UP_PERST}_B1") (pintype "input"))
    )
    (net (code "593") (name "unconnected-(U4A-~{WAKE}-PadC3)") (class "Default")
      (node (ref "U4") (pin "C3") (pinfunction "~{WAKE}_C3") (pintype "passive"))
    )
    (net (code "594") (name "unconnected-(U4B-DN1_DPSTRP-PadC10)") (class "Default")
      (node (ref "U4") (pin "C10") (pinfunction "DN1_DPSTRP_C10") (pintype "input"))
    )
    (net (code "595") (name "unconnected-(U4B-DN2_DPSTRP-PadL13)") (class "Default")
      (node (ref "U4") (pin "L13") (pinfunction "DN2_DPSTRP_L13") (pintype "input"))
    )
    (net (code "596") (name "unconnected-(U4B-DN2_PERN-PadF14)") (class "Default")
      (node (ref "U4") (pin "F14") (pinfunction "DN2_PERN_F14") (pintype "passive"))
    )
    (net (code "597") (name "unconnected-(U4B-DN2_PERP-PadF13)") (class "Default")
      (node (ref "U4") (pin "F13") (pinfunction "DN2_PERP_F13") (pintype "passive"))
    )
    (net (code "598") (name "unconnected-(U4B-DN2_PETN-PadH14)") (class "Default")
      (node (ref "U4") (pin "H14") (pinfunction "DN2_PETN_H14") (pintype "passive"))
    )
    (net (code "599") (name "unconnected-(U4B-DN2_PETP-PadH13)") (class "Default")
      (node (ref "U4") (pin "H13") (pinfunction "DN2_PETP_H13") (pintype "passive"))
    )
    (net (code "600") (name "unconnected-(U4B-DN2_REFCKON-PadJ14)") (class "Default")
      (node (ref "U4") (pin "J14") (pinfunction "DN2_REFCKON_J14") (pintype "output"))
    )
    (net (code "601") (name "unconnected-(U4B-DN2_REFCKOP-PadK14)") (class "Default")
      (node (ref "U4") (pin "K14") (pinfunction "DN2_REFCKOP_K14") (pintype "output"))
    )
    (net (code "602") (name "unconnected-(U4B-DN3_DPSTRP-PadN4)") (class "Default")
      (node (ref "U4") (pin "N4") (pinfunction "DN3_DPSTRP_N4") (pintype "input"))
    )
    (net (code "603") (name "unconnected-(U4B-DN3_PERN-PadP9)") (class "Default")
      (node (ref "U4") (pin "P9") (pinfunction "DN3_PERN_P9") (pintype "passive"))
    )
    (net (code "604") (name "unconnected-(U4B-DN3_PERP-PadN9)") (class "Default")
      (node (ref "U4") (pin "N9") (pinfunction "DN3_PERP_N9") (pintype "passive"))
    )
    (net (code "605") (name "unconnected-(U4B-DN3_PETN-PadP7)") (class "Default")
      (node (ref "U4") (pin "P7") (pinfunction "DN3_PETN_P7") (pintype "passive"))
    )
    (net (code "606") (name "unconnected-(U4B-DN3_PETP-PadN7)") (class "Default")
      (node (ref "U4") (pin "N7") (pinfunction "DN3_PETP_N7") (pintype "passive"))
    )
    (net (code "607") (name "unconnected-(U4B-DN3_REFCKON-PadP6)") (class "Default")
      (node (ref "U4") (pin "P6") (pinfunction "DN3_REFCKON_P6") (pintype "output"))
    )
    (net (code "608") (name "unconnected-(U4B-DN3_REFCKOP-PadP5)") (class "Default")
      (node (ref "U4") (pin "P5") (pinfunction "DN3_REFCKOP_P5") (pintype "output"))
    )
    (net (code "609") (name "unconnected-(U4B-GPIO2-PadA12)") (class "Default")
      (node (ref "U4") (pin "A12") (pinfunction "GPIO2_A12") (pintype "bidirectional"))
    )
    (net (code "610") (name "unconnected-(U4B-GPIO3-PadC12)") (class "Default")
      (node (ref "U4") (pin "C12") (pinfunction "GPIO3_C12") (pintype "bidirectional"))
    )
    (net (code "611") (name "unconnected-(U4B-GPIO4-PadD14)") (class "Default")
      (node (ref "U4") (pin "D14") (pinfunction "GPIO4_D14") (pintype "bidirectional"))
    )
    (net (code "612") (name "unconnected-(U4B-GPIO5-PadL12)") (class "Default")
      (node (ref "U4") (pin "L12") (pinfunction "GPIO5_L12") (pintype "bidirectional"))
    )
    (net (code "613") (name "unconnected-(U4B-GPIO6-PadM13)") (class "Default")
      (node (ref "U4") (pin "M13") (pinfunction "GPIO6_M13") (pintype "bidirectional"))
    )
    (net (code "614") (name "unconnected-(U4B-GPIO7-PadP13)") (class "Default")
      (node (ref "U4") (pin "P13") (pinfunction "GPIO7_P13") (pintype "bidirectional"))
    )
    (net (code "615") (name "unconnected-(U4B-GPIO8-PadM10)") (class "Default")
      (node (ref "U4") (pin "M10") (pinfunction "GPIO8_M10") (pintype "bidirectional"))
    )
    (net (code "616") (name "unconnected-(U4B-GPIO9-PadN3)") (class "Default")
      (node (ref "U4") (pin "N3") (pinfunction "GPIO9_N3") (pintype "bidirectional"))
    )
    (net (code "617") (name "unconnected-(U4B-GPIO10-PadP2)") (class "Default")
      (node (ref "U4") (pin "P2") (pinfunction "GPIO10_P2") (pintype "bidirectional"))
    )
    (net (code "618") (name "unconnected-(U4B-GPIO11-PadN11)") (class "Default")
      (node (ref "U4") (pin "N11") (pinfunction "GPIO11_N11") (pintype "bidirectional"))
    )
    (net (code "619") (name "unconnected-(U4B-GPIO12-PadB11)") (class "Default")
      (node (ref "U4") (pin "B11") (pinfunction "GPIO12_B11") (pintype "bidirectional"))
    )
    (net (code "620") (name "unconnected-(U4B-GPIO12_2-PadA14)") (class "Default")
      (node (ref "U4") (pin "A14") (pinfunction "GPIO12_2_A14") (pintype "bidirectional"))
    )
    (net (code "621") (name "unconnected-(U4B-GPIO13-PadB13)") (class "Default")
      (node (ref "U4") (pin "B13") (pinfunction "GPIO13_B13") (pintype "bidirectional"))
    )
    (net (code "622") (name "unconnected-(U4B-GPIO14-PadN12)") (class "Default")
      (node (ref "U4") (pin "N12") (pinfunction "GPIO14_N12") (pintype "bidirectional"))
    )
    (net (code "623") (name "unconnected-(U4B-GPIO15-PadM14)") (class "Default")
      (node (ref "U4") (pin "M14") (pinfunction "GPIO15_M14") (pintype "bidirectional"))
    )
    (net (code "624") (name "unconnected-(U4B-GPIO16-PadP12)") (class "Default")
      (node (ref "U4") (pin "P12") (pinfunction "GPIO16_P12") (pintype "bidirectional"))
    )
    (net (code "625") (name "unconnected-(U4B-GPIO17-PadM3)") (class "Default")
      (node (ref "U4") (pin "M3") (pinfunction "GPIO17_M3") (pintype "bidirectional"))
    )
    (net (code "626") (name "unconnected-(U4B-RSVD-PadB12)") (class "Default")
      (node (ref "U4") (pin "B12") (pinfunction "RSVD_B12") (pintype "no_connect"))
    )
    (net (code "627") (name "unconnected-(U4B-RSVD_2-PadP1)") (class "Default")
      (node (ref "U4") (pin "P1") (pinfunction "RSVD_2_P1") (pintype "no_connect"))
    )
    (net (code "628") (name "unconnected-(U4B-RSVD_3-PadA13)") (class "Default")
      (node (ref "U4") (pin "A13") (pinfunction "RSVD_3_A13") (pintype "no_connect"))
    )
    (net (code "629") (name "unconnected-(U4B-SCL-PadB14)") (class "Default")
      (node (ref "U4") (pin "B14") (pinfunction "SCL_B14") (pintype "output"))
    )
    (net (code "630") (name "unconnected-(U4B-SDA-PadD13)") (class "Default")
      (node (ref "U4") (pin "D13") (pinfunction "SDA_D13") (pintype "bidirectional"))
    )
    (net (code "631") (name "unconnected-(U4B-VDD15-PadP14)") (class "Default")
      (node (ref "U4") (pin "P14") (pinfunction "VDD15_P14") (pintype "power_in"))
    )
    (net (code "632") (name "unconnected-(U4B-VDD15_2-PadM1)") (class "Default")
      (node (ref "U4") (pin "M1") (pinfunction "VDD15_2_M1") (pintype "power_in"))
    )
    (net (code "633") (name "unconnected-(U4B-VDD15_3-PadM2)") (class "Default")
      (node (ref "U4") (pin "M2") (pinfunction "VDD15_3_M2") (pintype "power_in"))
    )
    (net (code "634") (name "unconnected-(U4B-VDD15_4-PadN8)") (class "Default")
      (node (ref "U4") (pin "N8") (pinfunction "VDD15_4_N8") (pintype "power_in"))
    )
    (net (code "635") (name "unconnected-(U4B-VDD15_5-PadP3)") (class "Default")
      (node (ref "U4") (pin "P3") (pinfunction "VDD15_5_P3") (pintype "power_in"))
    )
    (net (code "636") (name "unconnected-(U4B-VDD15_6-PadP4)") (class "Default")
      (node (ref "U4") (pin "P4") (pinfunction "VDD15_6_P4") (pintype "power_in"))
    )
    (net (code "637") (name "unconnected-(U4B-VDD15_7-PadB10)") (class "Default")
      (node (ref "U4") (pin "B10") (pinfunction "VDD15_7_B10") (pintype "power_in"))
    )
    (net (code "638") (name "unconnected-(U4B-VDD15_8-PadC11)") (class "Default")
      (node (ref "U4") (pin "C11") (pinfunction "VDD15_8_C11") (pintype "power_in"))
    )
    (net (code "639") (name "unconnected-(U4B-VDD15_9-PadC13)") (class "Default")
      (node (ref "U4") (pin "C13") (pinfunction "VDD15_9_C13") (pintype "power_in"))
    )
    (net (code "640") (name "unconnected-(U4B-VDD15_10-PadC14)") (class "Default")
      (node (ref "U4") (pin "C14") (pinfunction "VDD15_10_C14") (pintype "power_in"))
    )
    (net (code "641") (name "unconnected-(U4B-VDD15_11-PadE13)") (class "Default")
      (node (ref "U4") (pin "E13") (pinfunction "VDD15_11_E13") (pintype "power_in"))
    )
    (net (code "642") (name "unconnected-(U4B-VDD15_12-PadG13)") (class "Default")
      (node (ref "U4") (pin "G13") (pinfunction "VDD15_12_G13") (pintype "power_in"))
    )
    (net (code "643") (name "unconnected-(U4B-VDD15_13-PadL14)") (class "Default")
      (node (ref "U4") (pin "L14") (pinfunction "VDD15_13_L14") (pintype "power_in"))
    )
    (net (code "644") (name "unconnected-(U4B-VDD15_14-PadM11)") (class "Default")
      (node (ref "U4") (pin "M11") (pinfunction "VDD15_14_M11") (pintype "power_in"))
    )
    (net (code "645") (name "unconnected-(U4B-VDD15_15-PadM12)") (class "Default")
      (node (ref "U4") (pin "M12") (pinfunction "VDD15_15_M12") (pintype "power_in"))
    )
    (net (code "646") (name "unconnected-(U4B-VDD15_16-PadN10)") (class "Default")
      (node (ref "U4") (pin "N10") (pinfunction "VDD15_16_N10") (pintype "power_in"))
    )
    (net (code "647") (name "unconnected-(U4B-VDD15_17-PadN13)") (class "Default")
      (node (ref "U4") (pin "N13") (pinfunction "VDD15_17_N13") (pintype "power_in"))
    )
    (net (code "648") (name "unconnected-(U4B-VDD15_18-PadN14)") (class "Default")
      (node (ref "U4") (pin "N14") (pinfunction "VDD15_18_N14") (pintype "power_in"))
    )
    (net (code "649") (name "unconnected-(U4B-VDD33-PadP11)") (class "Default")
      (node (ref "U4") (pin "P11") (pinfunction "VDD33_P11") (pintype "power_in"))
    )
    (net (code "650") (name "unconnected-(U4B-VDD33_2-PadM4)") (class "Default")
      (node (ref "U4") (pin "M4") (pinfunction "VDD33_2_M4") (pintype "power_in"))
    )
    (net (code "651") (name "unconnected-(U4B-VDD33_3-PadN1)") (class "Default")
      (node (ref "U4") (pin "N1") (pinfunction "VDD33_3_N1") (pintype "power_in"))
    )
    (net (code "652") (name "unconnected-(U4B-VDD33_4-PadA11)") (class "Default")
      (node (ref "U4") (pin "A11") (pinfunction "VDD33_4_A11") (pintype "power_in"))
    )
    (net (code "653") (name "unconnected-(U4B-VDD33_5-PadD12)") (class "Default")
      (node (ref "U4") (pin "D12") (pinfunction "VDD33_5_D12") (pintype "power_in"))
    )
    (net (code "654") (name "unconnected-(U4B-VDD33_6-PadK12)") (class "Default")
      (node (ref "U4") (pin "K12") (pinfunction "VDD33_6_K12") (pintype "power_in"))
    )
    (net (code "655") (name "unconnected-(U4B-VDDA15-PadJ12)") (class "Default")
      (node (ref "U4") (pin "J12") (pinfunction "VDDA15_J12") (pintype "power_in"))
    )
    (net (code "656") (name "unconnected-(U4B-VDDA15_2-PadM6)") (class "Default")
      (node (ref "U4") (pin "M6") (pinfunction "VDDA15_2_M6") (pintype "power_in"))
    )
    (net (code "657") (name "unconnected-(U4B-VDDA15_3-PadM8)") (class "Default")
      (node (ref "U4") (pin "M8") (pinfunction "VDDA15_3_M8") (pintype "power_in"))
    )
    (net (code "658") (name "unconnected-(U4B-VDDA15_4-PadG11)") (class "Default")
      (node (ref "U4") (pin "G11") (pinfunction "VDDA15_4_G11") (pintype "power_in"))
    )
    (net (code "659") (name "unconnected-(U4B-VDDA15_5-PadG12)") (class "Default")
      (node (ref "U4") (pin "G12") (pinfunction "VDDA15_5_G12") (pintype "power_in"))
    )
    (net (code "660") (name "unconnected-(U4B-VDDA15_6-PadH11)") (class "Default")
      (node (ref "U4") (pin "H11") (pinfunction "VDDA15_6_H11") (pintype "power_in"))
    )
    (net (code "661") (name "unconnected-(U4B-VDDA15_7-PadJ11)") (class "Default")
      (node (ref "U4") (pin "J11") (pinfunction "VDDA15_7_J11") (pintype "power_in"))
    )
    (net (code "662") (name "unconnected-(U4B-VSS-PadL11)") (class "Default")
      (node (ref "U4") (pin "L11") (pinfunction "VSS_L11") (pintype "power_in"))
    )
    (net (code "663") (name "unconnected-(U4B-VSSA-PadP10)") (class "Default")
      (node (ref "U4") (pin "P10") (pinfunction "VSSA_P10") (pintype "power_in"))
    )
    (net (code "664") (name "unconnected-(U4B-VSSA_2-PadL9)") (class "Default")
      (node (ref "U4") (pin "L9") (pinfunction "VSSA_2_L9") (pintype "power_in"))
    )
    (net (code "665") (name "unconnected-(U4B-VSSA_3-PadM7)") (class "Default")
      (node (ref "U4") (pin "M7") (pinfunction "VSSA_3_M7") (pintype "power_in"))
    )
    (net (code "666") (name "unconnected-(U4B-VSSA_4-PadM9)") (class "Default")
      (node (ref "U4") (pin "M9") (pinfunction "VSSA_4_M9") (pintype "power_in"))
    )
    (net (code "667") (name "unconnected-(U4B-VSSA_5-PadN5)") (class "Default")
      (node (ref "U4") (pin "N5") (pinfunction "VSSA_5_N5") (pintype "power_in"))
    )
    (net (code "668") (name "unconnected-(U4B-VSSA_6-PadN6)") (class "Default")
      (node (ref "U4") (pin "N6") (pinfunction "VSSA_6_N6") (pintype "power_in"))
    )
    (net (code "669") (name "unconnected-(U4B-VSSA_7-PadP8)") (class "Default")
      (node (ref "U4") (pin "P8") (pinfunction "VSSA_7_P8") (pintype "power_in"))
    )
    (net (code "670") (name "unconnected-(U4B-VSSA_8-PadA10)") (class "Default")
      (node (ref "U4") (pin "A10") (pinfunction "VSSA_8_A10") (pintype "power_in"))
    )
    (net (code "671") (name "unconnected-(U4B-VSSA_9-PadE14)") (class "Default")
      (node (ref "U4") (pin "E14") (pinfunction "VSSA_9_E14") (pintype "power_in"))
    )
    (net (code "672") (name "unconnected-(U4B-VSSA_10-PadF11)") (class "Default")
      (node (ref "U4") (pin "F11") (pinfunction "VSSA_10_F11") (pintype "power_in"))
    )
    (net (code "673") (name "unconnected-(U4B-VSSA_11-PadF12)") (class "Default")
      (node (ref "U4") (pin "F12") (pinfunction "VSSA_11_F12") (pintype "power_in"))
    )
    (net (code "674") (name "unconnected-(U4B-VSSA_12-PadG14)") (class "Default")
      (node (ref "U4") (pin "G14") (pinfunction "VSSA_12_G14") (pintype "power_in"))
    )
    (net (code "675") (name "unconnected-(U4B-VSSA_13-PadH12)") (class "Default")
      (node (ref "U4") (pin "H12") (pinfunction "VSSA_13_H12") (pintype "power_in"))
    )
    (net (code "676") (name "unconnected-(U4B-VSSA_14-PadJ13)") (class "Default")
      (node (ref "U4") (pin "J13") (pinfunction "VSSA_14_J13") (pintype "power_in"))
    )
    (net (code "677") (name "unconnected-(U4B-VSSA_15-PadK13)") (class "Default")
      (node (ref "U4") (pin "K13") (pinfunction "VSSA_15_K13") (pintype "power_in"))
    )
    (net (code "678") (name "unconnected-(U4B-VSS_2-PadM5)") (class "Default")
      (node (ref "U4") (pin "M5") (pinfunction "VSS_2_M5") (pintype "power_in"))
    )
    (net (code "679") (name "unconnected-(U4B-VSS_3-PadD10)") (class "Default")
      (node (ref "U4") (pin "D10") (pinfunction "VSS_3_D10") (pintype "power_in"))
    )
    (net (code "680") (name "unconnected-(U4B-VSS_4-PadD11)") (class "Default")
      (node (ref "U4") (pin "D11") (pinfunction "VSS_4_D11") (pintype "power_in"))
    )
    (net (code "681") (name "unconnected-(U4B-VSS_5-PadE10)") (class "Default")
      (node (ref "U4") (pin "E10") (pinfunction "VSS_5_E10") (pintype "power_in"))
    )
    (net (code "682") (name "unconnected-(U4B-VSS_6-PadE11)") (class "Default")
      (node (ref "U4") (pin "E11") (pinfunction "VSS_6_E11") (pintype "power_in"))
    )
    (net (code "683") (name "unconnected-(U4B-VSS_7-PadE12)") (class "Default")
      (node (ref "U4") (pin "E12") (pinfunction "VSS_7_E12") (pintype "power_in"))
    )
    (net (code "684") (name "unconnected-(U4B-VSS_8-PadF10)") (class "Default")
      (node (ref "U4") (pin "F10") (pinfunction "VSS_8_F10") (pintype "power_in"))
    )
    (net (code "685") (name "unconnected-(U4B-VSS_9-PadG10)") (class "Default")
      (node (ref "U4") (pin "G10") (pinfunction "VSS_9_G10") (pintype "power_in"))
    )
    (net (code "686") (name "unconnected-(U4B-VSS_10-PadH10)") (class "Default")
      (node (ref "U4") (pin "H10") (pinfunction "VSS_10_H10") (pintype "power_in"))
    )
    (net (code "687") (name "unconnected-(U4B-VSS_11-PadJ10)") (class "Default")
      (node (ref "U4") (pin "J10") (pinfunction "VSS_11_J10") (pintype "power_in"))
    )
    (net (code "688") (name "unconnected-(U4B-VSS_12-PadK10)") (class "Default")
      (node (ref "U4") (pin "K10") (pinfunction "VSS_12_K10") (pintype "power_in"))
    )
    (net (code "689") (name "unconnected-(U4B-VSS_13-PadK11)") (class "Default")
      (node (ref "U4") (pin "K11") (pinfunction "VSS_13_K11") (pintype "power_in"))
    )
    (net (code "690") (name "unconnected-(U4B-VSS_14-PadL10)") (class "Default")
      (node (ref "U4") (pin "L10") (pinfunction "VSS_14_L10") (pintype "power_in"))
    )
    (net (code "691") (name "unconnected-(U4B-~{CLKREQ_UP}-PadN2)") (class "Default")
      (node (ref "U4") (pin "N2") (pinfunction "~{CLKREQ_UP}_N2") (pintype "output"))
    )
    (net (code "692") (name "unconnected-(Z1-NC-Pad2)") (class "Default")
      (node (ref "Z1") (pin "2") (pinfunction "NC_2") (pintype "no_connect"))
    )
  )
)
